# Negibus.net
KiCad netlist of a schematic drawn in EAGLE
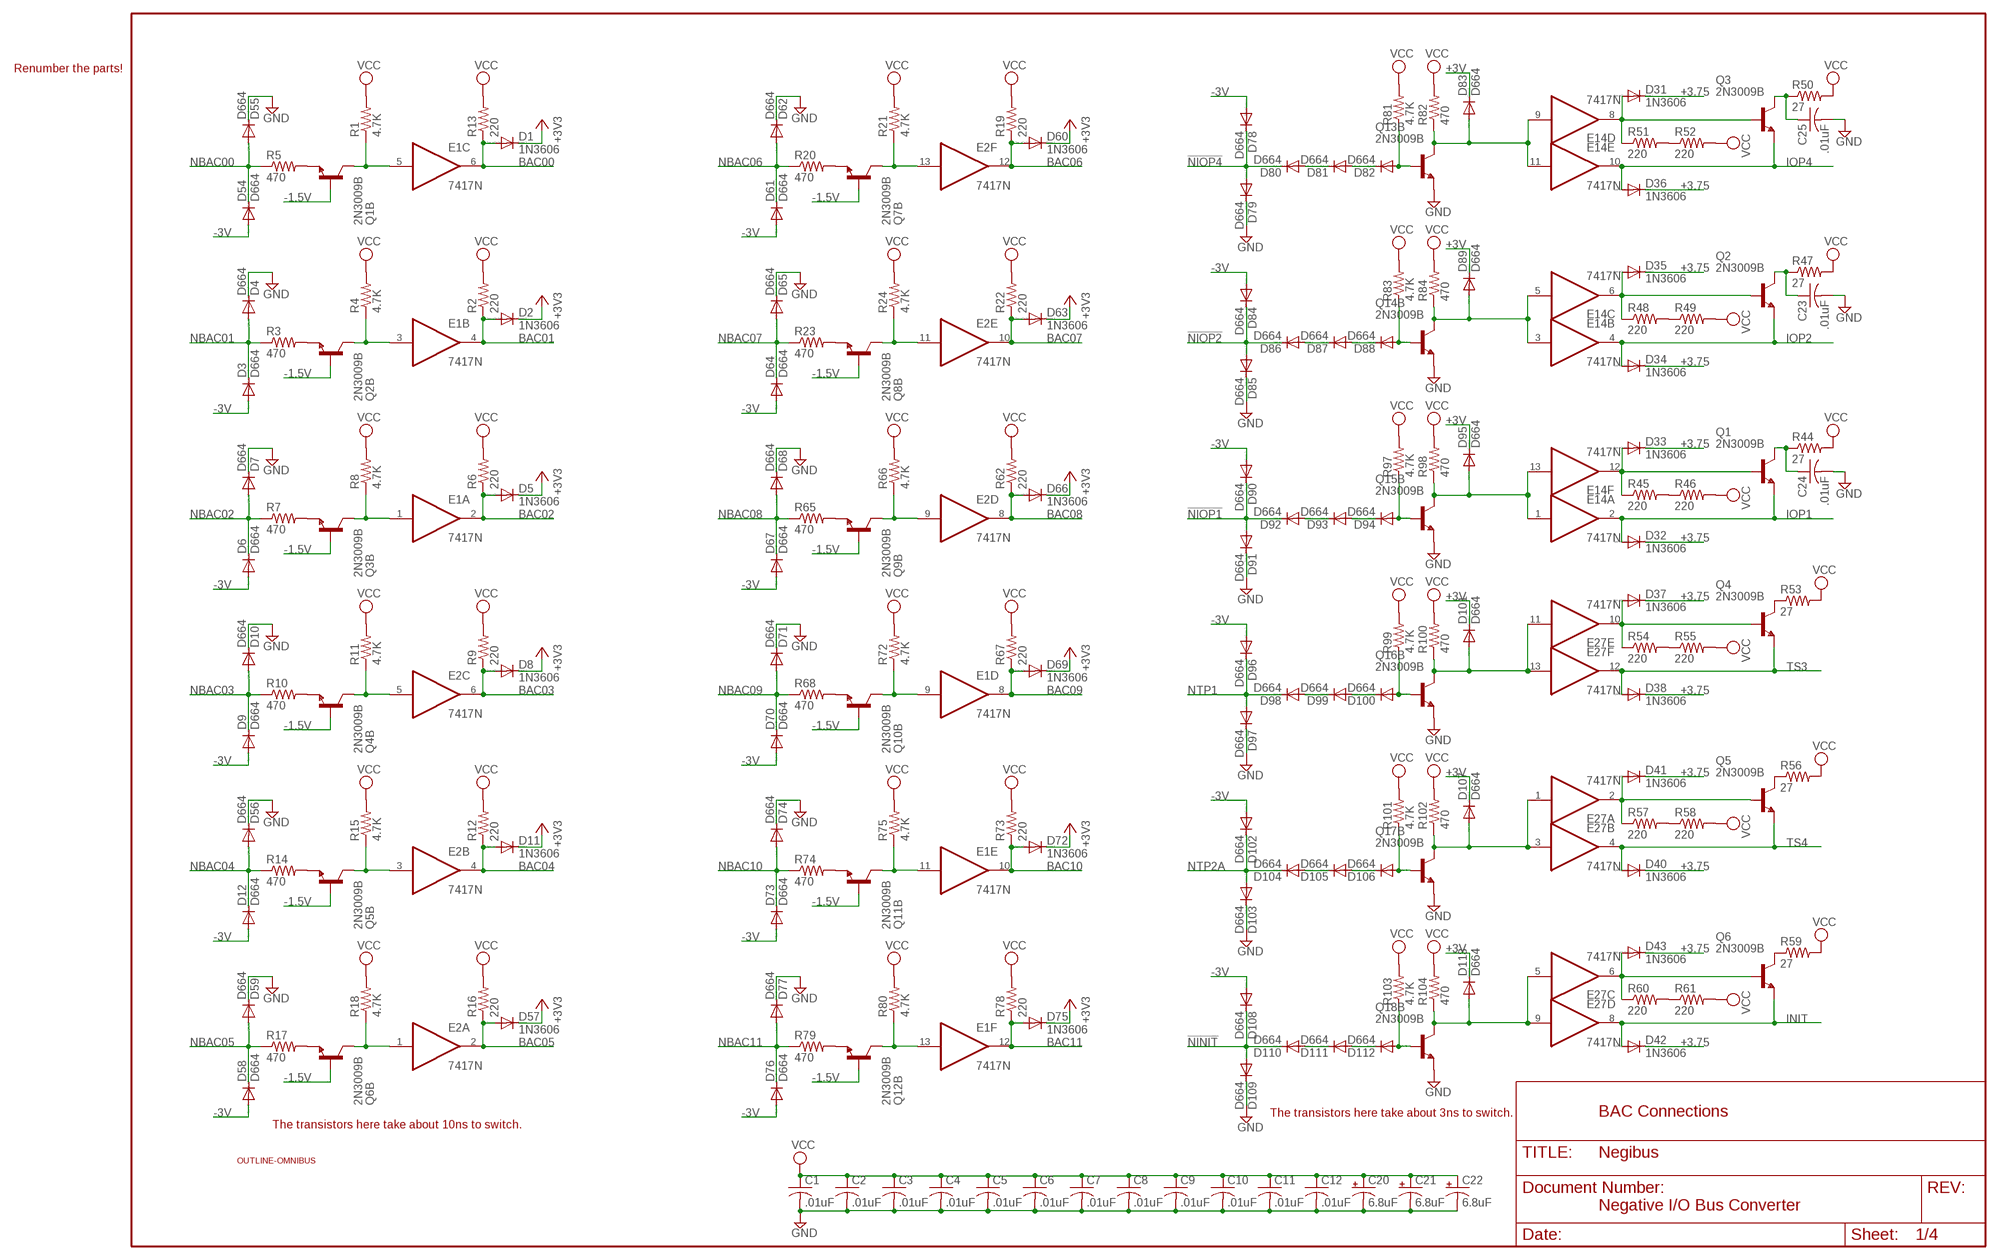
[diagram p0: schematic, sheet 1]
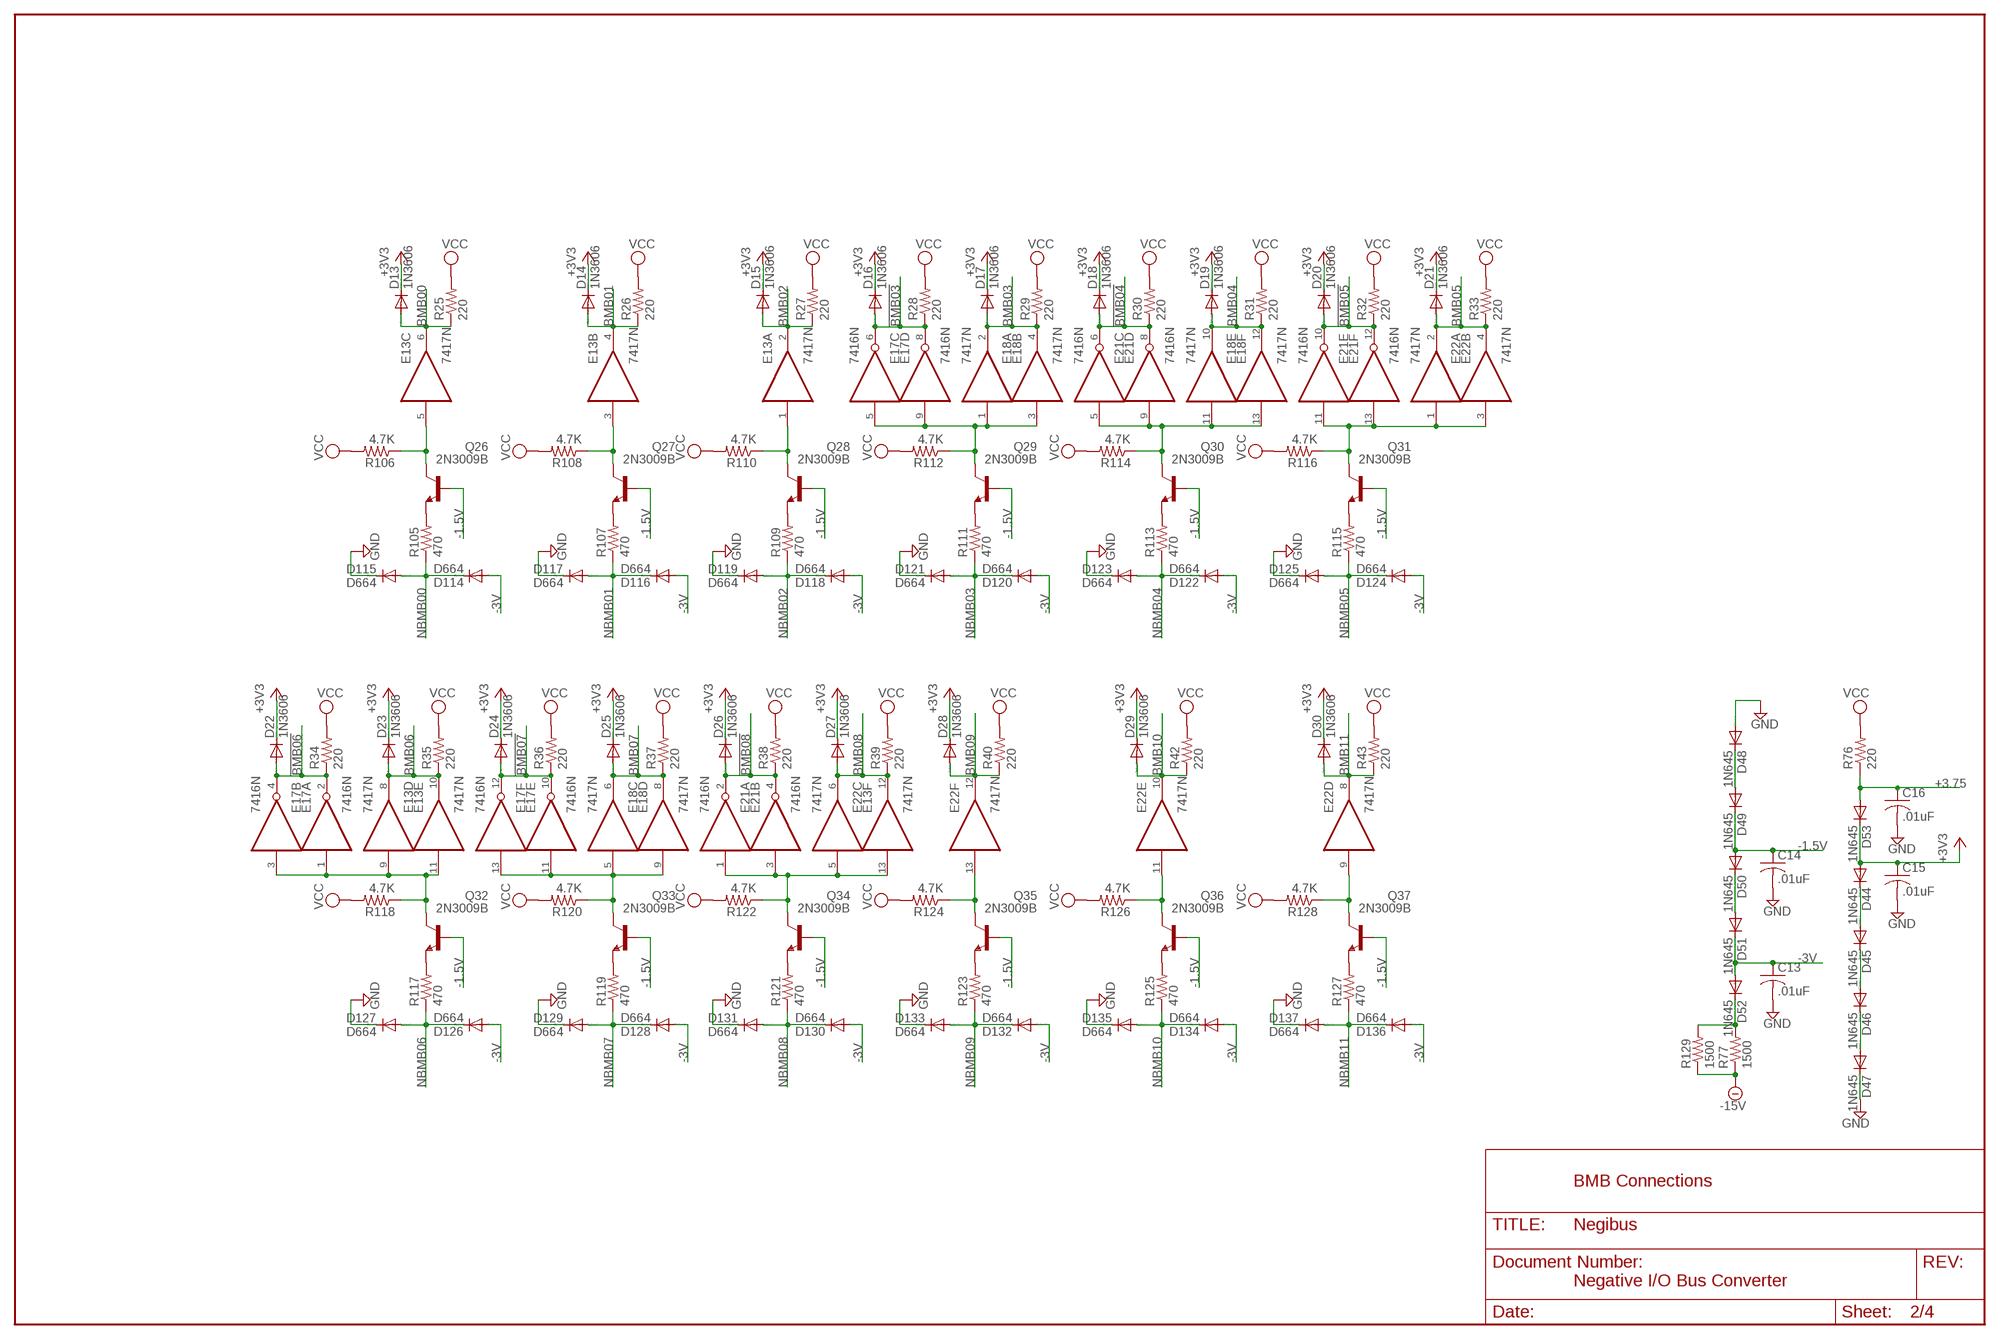
[diagram p1: schematic, sheet 2]
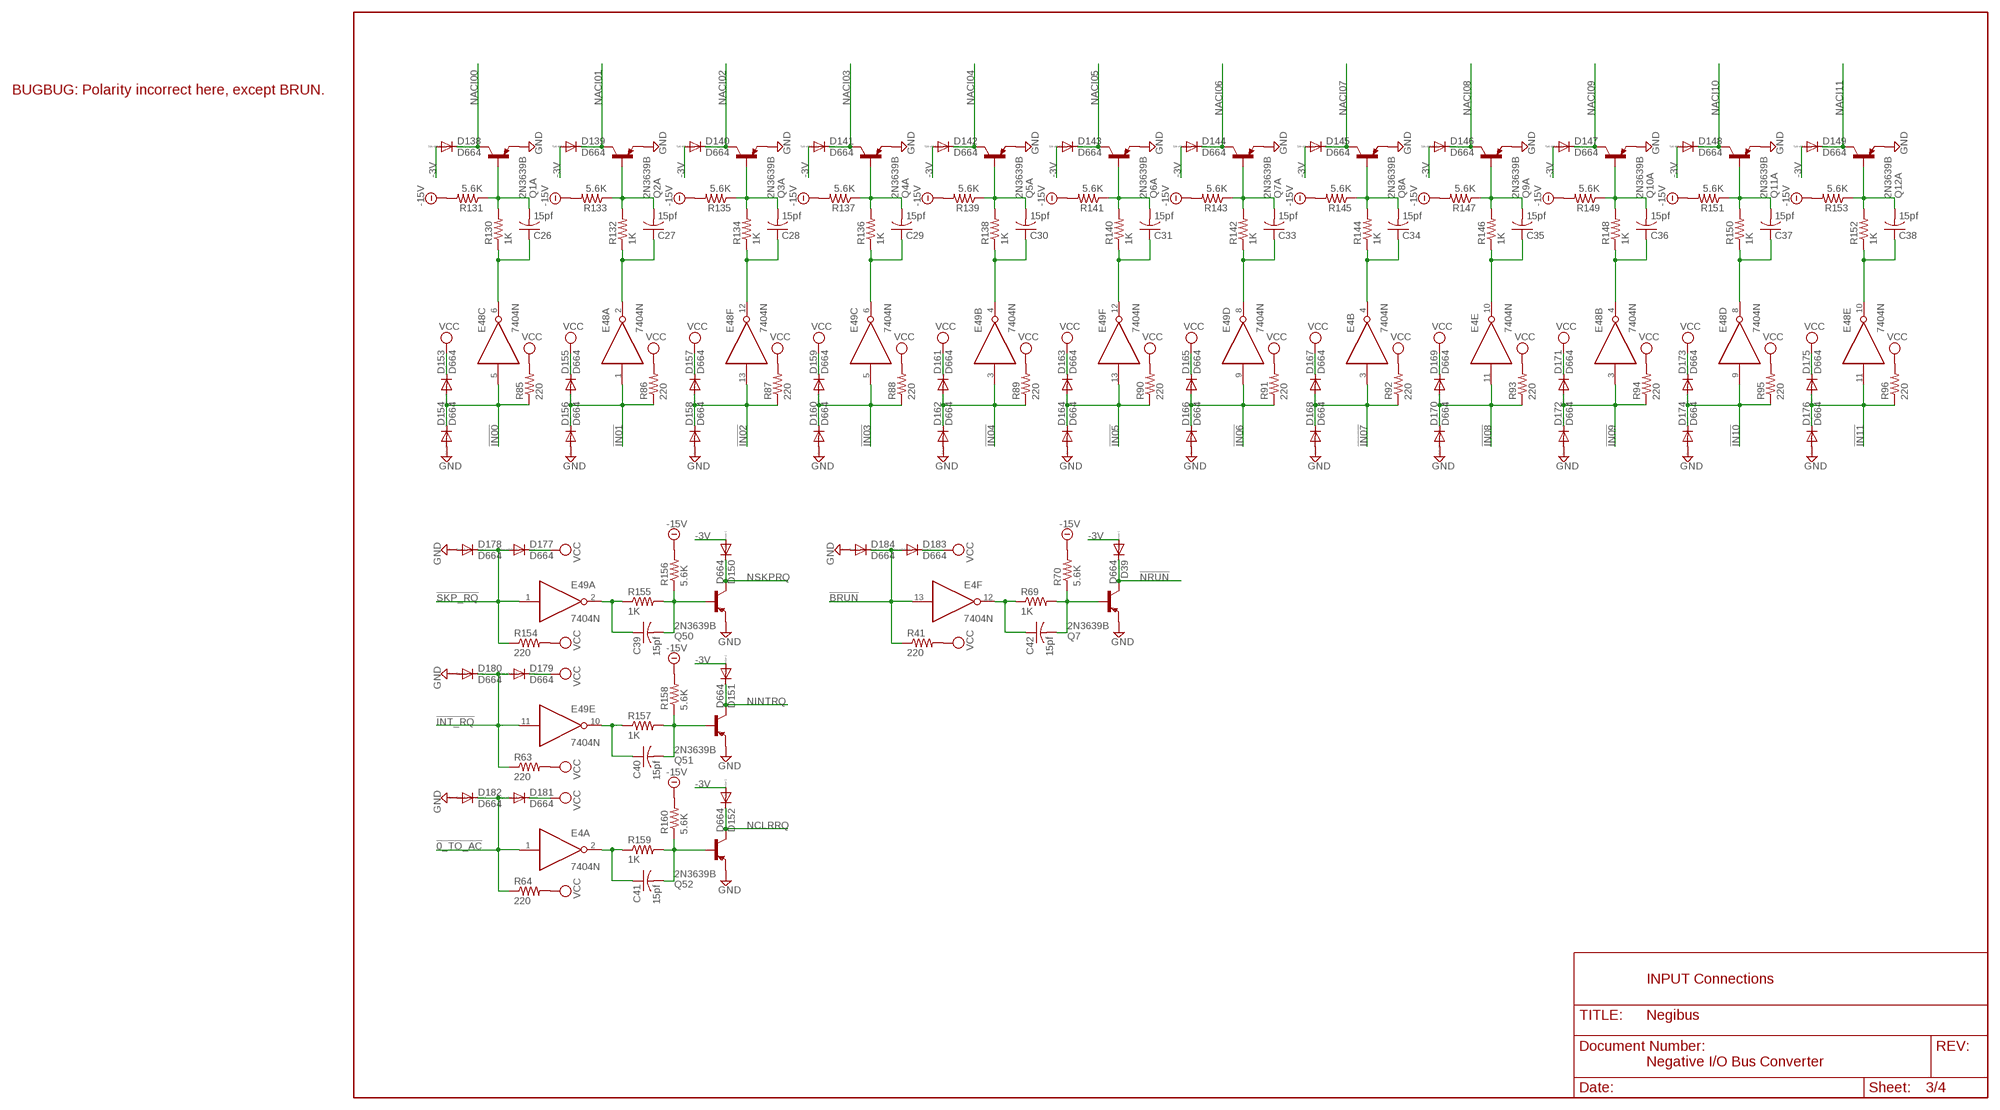
[diagram p2: schematic, sheet 3]
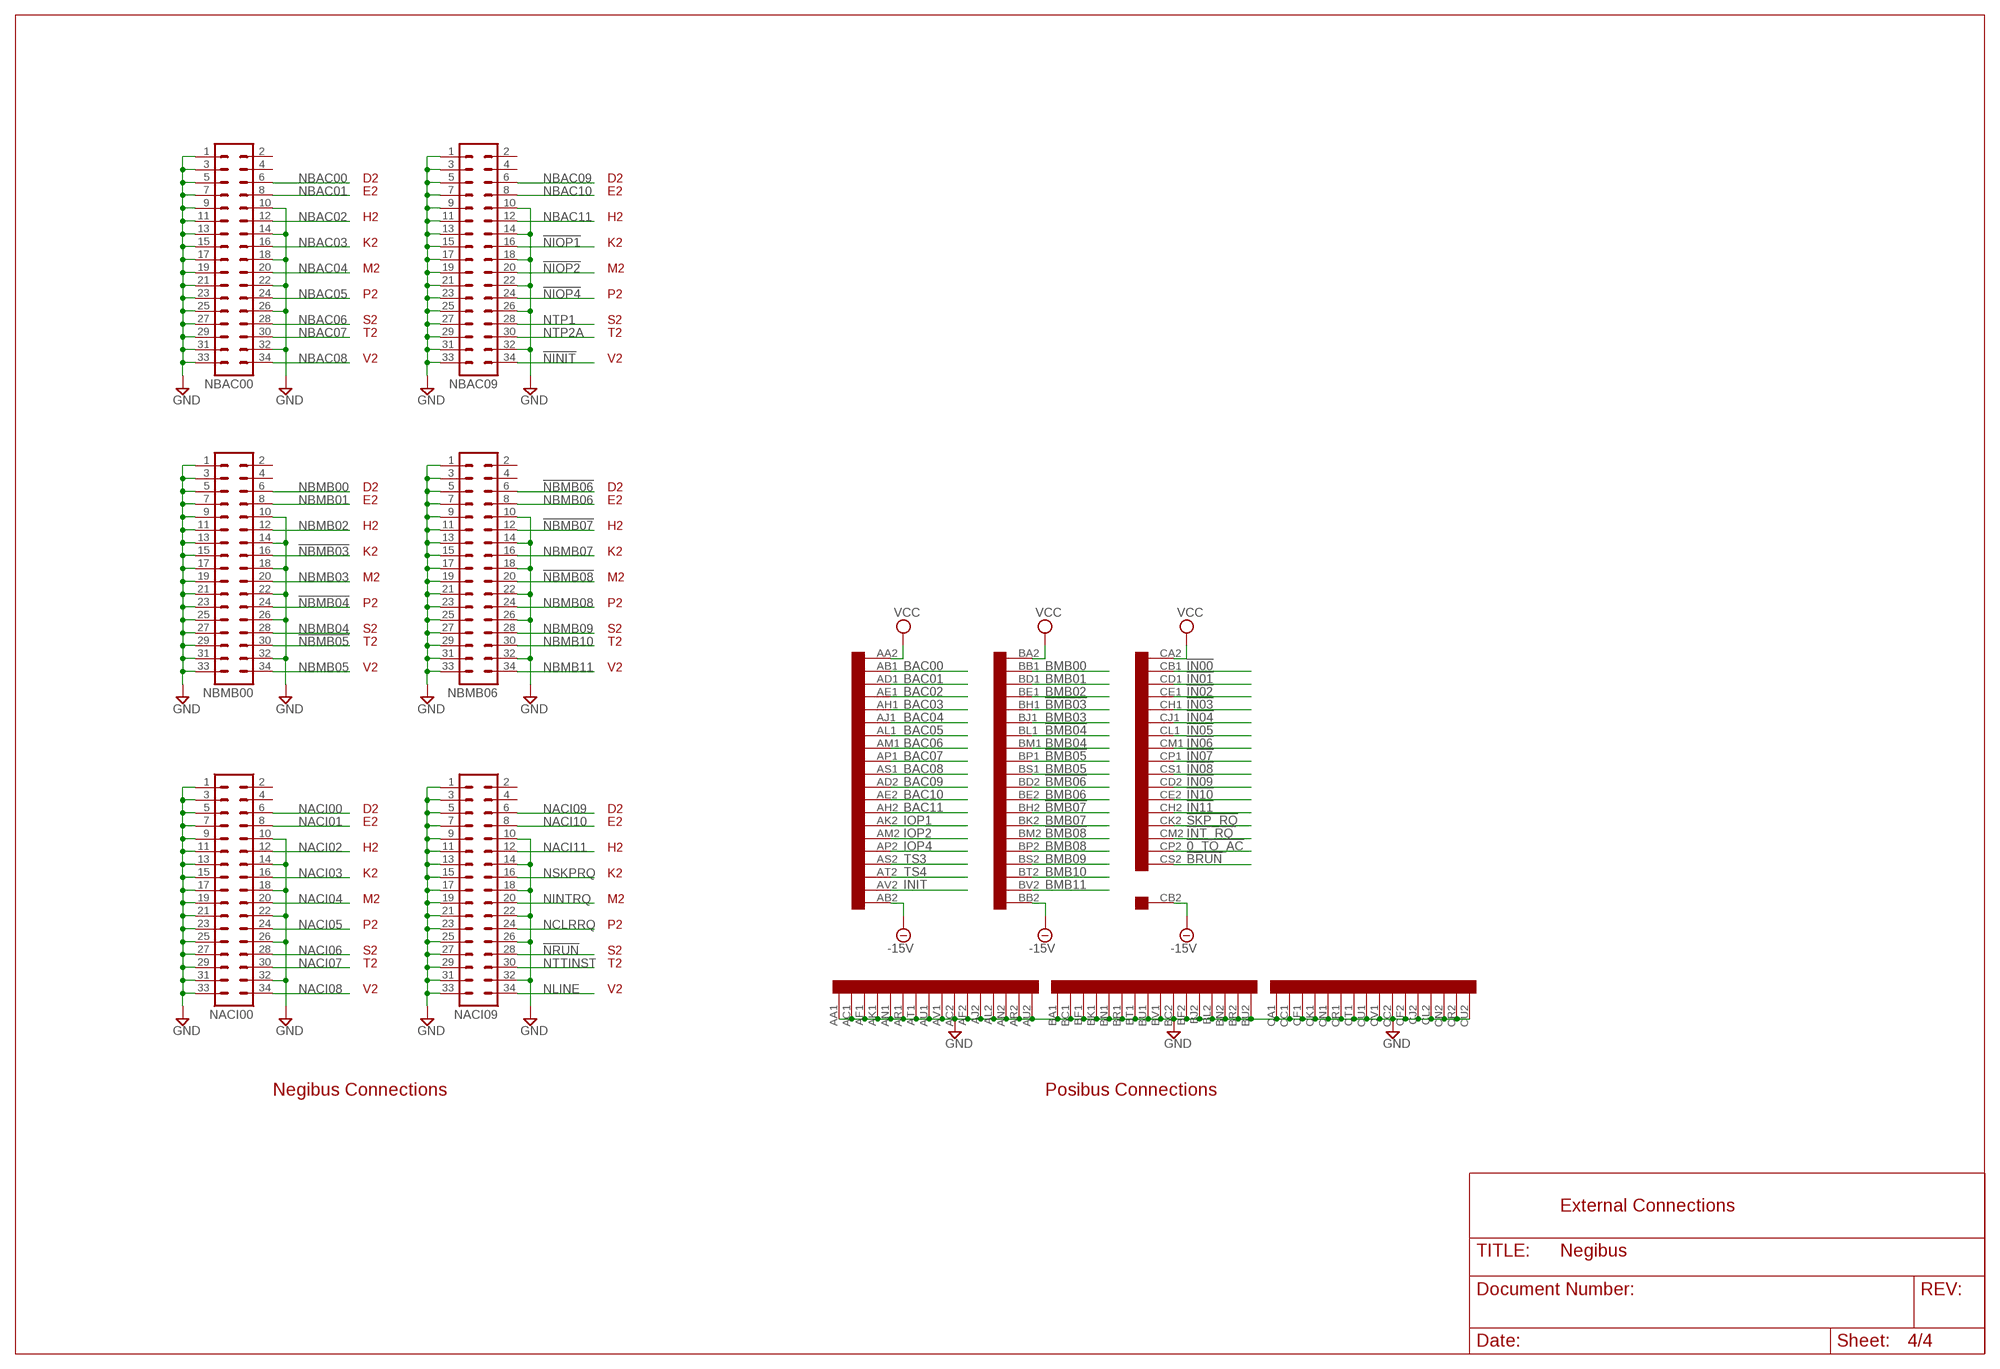
[diagram p3: schematic, sheet 4]

(export (version "E")
  (design (tool "Eeschema 10.0.6"))
  (components
    (comp (ref "C1")
      (value ".01uF")
      (footprint "eagle-import:C050-025X075")
      (libsource (lib "eagle-import") (part "C-US050-025X075"))
    )
    (comp (ref "C2")
      (value ".01uF")
      (footprint "eagle-import:C050-025X075")
      (libsource (lib "eagle-import") (part "C-US050-025X075"))
    )
    (comp (ref "C3")
      (value ".01uF")
      (footprint "eagle-import:C050-025X075")
      (libsource (lib "eagle-import") (part "C-US050-025X075"))
    )
    (comp (ref "C4")
      (value ".01uF")
      (footprint "eagle-import:C050-025X075")
      (libsource (lib "eagle-import") (part "C-US050-025X075"))
    )
    (comp (ref "C5")
      (value ".01uF")
      (footprint "eagle-import:C050-025X075")
      (libsource (lib "eagle-import") (part "C-US050-025X075"))
    )
    (comp (ref "C6")
      (value ".01uF")
      (footprint "eagle-import:C050-025X075")
      (libsource (lib "eagle-import") (part "C-US050-025X075"))
    )
    (comp (ref "C7")
      (value ".01uF")
      (footprint "eagle-import:C050-025X075")
      (libsource (lib "eagle-import") (part "C-US050-025X075"))
    )
    (comp (ref "C8")
      (value ".01uF")
      (footprint "eagle-import:C050-025X075")
      (libsource (lib "eagle-import") (part "C-US050-025X075"))
    )
    (comp (ref "C9")
      (value ".01uF")
      (footprint "eagle-import:C050-025X075")
      (libsource (lib "eagle-import") (part "C-US050-025X075"))
    )
    (comp (ref "C10")
      (value ".01uF")
      (footprint "eagle-import:C050-025X075")
      (libsource (lib "eagle-import") (part "C-US050-025X075"))
    )
    (comp (ref "C11")
      (value ".01uF")
      (footprint "eagle-import:C050-025X075")
      (libsource (lib "eagle-import") (part "C-US050-025X075"))
    )
    (comp (ref "C12")
      (value ".01uF")
      (footprint "eagle-import:C050-025X075")
      (libsource (lib "eagle-import") (part "C-US050-025X075"))
    )
    (comp (ref "C20")
      (value "6.8uF")
      (footprint "eagle-import:E12-8")
      (libsource (lib "eagle-import") (part "CPOL-USE20-8AXIAL"))
    )
    (comp (ref "C21")
      (value "6.8uF")
      (footprint "eagle-import:E12-8")
      (libsource (lib "eagle-import") (part "CPOL-USE20-8AXIAL"))
    )
    (comp (ref "C22")
      (value "6.8uF")
      (footprint "eagle-import:E12-8")
      (libsource (lib "eagle-import") (part "CPOL-USE20-8AXIAL"))
    )
    (comp (ref "C23")
      (value ".01uF")
      (footprint "eagle-import:C050-025X075")
      (libsource (lib "eagle-import") (part "C-US050-025X075"))
    )
    (comp (ref "C24")
      (value ".01uF")
      (footprint "eagle-import:C050-025X075")
      (libsource (lib "eagle-import") (part "C-US050-025X075"))
    )
    (comp (ref "C25")
      (value ".01uF")
      (footprint "eagle-import:C050-025X075")
      (libsource (lib "eagle-import") (part "C-US050-025X075"))
    )
    (comp (ref "D1")
      (value "1N3606")
      (footprint "eagle-import:DO35-10")
      (libsource (lib "eagle-import") (part "DIODE-DO35-10"))
    )
    (comp (ref "D2")
      (value "1N3606")
      (footprint "eagle-import:DO35-10")
      (libsource (lib "eagle-import") (part "DIODE-DO35-10"))
    )
    (comp (ref "D3")
      (value "D664")
      (footprint "eagle-import:DO35-10")
      (libsource (lib "eagle-import") (part "1N4148DO35-10"))
    )
    (comp (ref "D4")
      (value "D664")
      (footprint "eagle-import:DO35-10")
      (libsource (lib "eagle-import") (part "1N4148DO35-10"))
    )
    (comp (ref "D5")
      (value "1N3606")
      (footprint "eagle-import:DO35-10")
      (libsource (lib "eagle-import") (part "DIODE-DO35-10"))
    )
    (comp (ref "D6")
      (value "D664")
      (footprint "eagle-import:DO35-10")
      (libsource (lib "eagle-import") (part "1N4148DO35-10"))
    )
    (comp (ref "D7")
      (value "D664")
      (footprint "eagle-import:DO35-10")
      (libsource (lib "eagle-import") (part "1N4148DO35-10"))
    )
    (comp (ref "D8")
      (value "1N3606")
      (footprint "eagle-import:DO35-10")
      (libsource (lib "eagle-import") (part "DIODE-DO35-10"))
    )
    (comp (ref "D9")
      (value "D664")
      (footprint "eagle-import:DO35-10")
      (libsource (lib "eagle-import") (part "1N4148DO35-10"))
    )
    (comp (ref "D10")
      (value "D664")
      (footprint "eagle-import:DO35-10")
      (libsource (lib "eagle-import") (part "1N4148DO35-10"))
    )
    (comp (ref "D11")
      (value "1N3606")
      (footprint "eagle-import:DO35-10")
      (libsource (lib "eagle-import") (part "DIODE-DO35-10"))
    )
    (comp (ref "D12")
      (value "D664")
      (footprint "eagle-import:DO35-10")
      (libsource (lib "eagle-import") (part "1N4148DO35-10"))
    )
    (comp (ref "D31")
      (value "1N3606")
      (footprint "eagle-import:DO35-10")
      (libsource (lib "eagle-import") (part "DIODE-DO35-10"))
    )
    (comp (ref "D32")
      (value "1N3606")
      (footprint "eagle-import:DO35-10")
      (libsource (lib "eagle-import") (part "DIODE-DO35-10"))
    )
    (comp (ref "D33")
      (value "1N3606")
      (footprint "eagle-import:DO35-10")
      (libsource (lib "eagle-import") (part "DIODE-DO35-10"))
    )
    (comp (ref "D34")
      (value "1N3606")
      (footprint "eagle-import:DO35-10")
      (libsource (lib "eagle-import") (part "DIODE-DO35-10"))
    )
    (comp (ref "D35")
      (value "1N3606")
      (footprint "eagle-import:DO35-10")
      (libsource (lib "eagle-import") (part "DIODE-DO35-10"))
    )
    (comp (ref "D36")
      (value "1N3606")
      (footprint "eagle-import:DO35-10")
      (libsource (lib "eagle-import") (part "DIODE-DO35-10"))
    )
    (comp (ref "D37")
      (value "1N3606")
      (footprint "eagle-import:DO35-10")
      (libsource (lib "eagle-import") (part "DIODE-DO35-10"))
    )
    (comp (ref "D38")
      (value "1N3606")
      (footprint "eagle-import:DO35-10")
      (libsource (lib "eagle-import") (part "DIODE-DO35-10"))
    )
    (comp (ref "D40")
      (value "1N3606")
      (footprint "eagle-import:DO35-10")
      (libsource (lib "eagle-import") (part "DIODE-DO35-10"))
    )
    (comp (ref "D41")
      (value "1N3606")
      (footprint "eagle-import:DO35-10")
      (libsource (lib "eagle-import") (part "DIODE-DO35-10"))
    )
    (comp (ref "D42")
      (value "1N3606")
      (footprint "eagle-import:DO35-10")
      (libsource (lib "eagle-import") (part "DIODE-DO35-10"))
    )
    (comp (ref "D43")
      (value "1N3606")
      (footprint "eagle-import:DO35-10")
      (libsource (lib "eagle-import") (part "DIODE-DO35-10"))
    )
    (comp (ref "D54")
      (value "D664")
      (footprint "eagle-import:DO35-10")
      (libsource (lib "eagle-import") (part "1N4148DO35-10"))
    )
    (comp (ref "D55")
      (value "D664")
      (footprint "eagle-import:DO35-10")
      (libsource (lib "eagle-import") (part "1N4148DO35-10"))
    )
    (comp (ref "D56")
      (value "D664")
      (footprint "eagle-import:DO35-10")
      (libsource (lib "eagle-import") (part "1N4148DO35-10"))
    )
    (comp (ref "D57")
      (value "1N3606")
      (footprint "eagle-import:DO35-10")
      (libsource (lib "eagle-import") (part "DIODE-DO35-10"))
    )
    (comp (ref "D58")
      (value "D664")
      (footprint "eagle-import:DO35-10")
      (libsource (lib "eagle-import") (part "1N4148DO35-10"))
    )
    (comp (ref "D59")
      (value "D664")
      (footprint "eagle-import:DO35-10")
      (libsource (lib "eagle-import") (part "1N4148DO35-10"))
    )
    (comp (ref "D60")
      (value "1N3606")
      (footprint "eagle-import:DO35-10")
      (libsource (lib "eagle-import") (part "DIODE-DO35-10"))
    )
    (comp (ref "D61")
      (value "D664")
      (footprint "eagle-import:DO35-10")
      (libsource (lib "eagle-import") (part "1N4148DO35-10"))
    )
    (comp (ref "D62")
      (value "D664")
      (footprint "eagle-import:DO35-10")
      (libsource (lib "eagle-import") (part "1N4148DO35-10"))
    )
    (comp (ref "D63")
      (value "1N3606")
      (footprint "eagle-import:DO35-10")
      (libsource (lib "eagle-import") (part "DIODE-DO35-10"))
    )
    (comp (ref "D64")
      (value "D664")
      (footprint "eagle-import:DO35-10")
      (libsource (lib "eagle-import") (part "1N4148DO35-10"))
    )
    (comp (ref "D65")
      (value "D664")
      (footprint "eagle-import:DO35-10")
      (libsource (lib "eagle-import") (part "1N4148DO35-10"))
    )
    (comp (ref "D66")
      (value "1N3606")
      (footprint "eagle-import:DO35-10")
      (libsource (lib "eagle-import") (part "DIODE-DO35-10"))
    )
    (comp (ref "D67")
      (value "D664")
      (footprint "eagle-import:DO35-10")
      (libsource (lib "eagle-import") (part "1N4148DO35-10"))
    )
    (comp (ref "D68")
      (value "D664")
      (footprint "eagle-import:DO35-10")
      (libsource (lib "eagle-import") (part "1N4148DO35-10"))
    )
    (comp (ref "D69")
      (value "1N3606")
      (footprint "eagle-import:DO35-10")
      (libsource (lib "eagle-import") (part "DIODE-DO35-10"))
    )
    (comp (ref "D70")
      (value "D664")
      (footprint "eagle-import:DO35-10")
      (libsource (lib "eagle-import") (part "1N4148DO35-10"))
    )
    (comp (ref "D71")
      (value "D664")
      (footprint "eagle-import:DO35-10")
      (libsource (lib "eagle-import") (part "1N4148DO35-10"))
    )
    (comp (ref "D72")
      (value "1N3606")
      (footprint "eagle-import:DO35-10")
      (libsource (lib "eagle-import") (part "DIODE-DO35-10"))
    )
    (comp (ref "D73")
      (value "D664")
      (footprint "eagle-import:DO35-10")
      (libsource (lib "eagle-import") (part "1N4148DO35-10"))
    )
    (comp (ref "D74")
      (value "D664")
      (footprint "eagle-import:DO35-10")
      (libsource (lib "eagle-import") (part "1N4148DO35-10"))
    )
    (comp (ref "D75")
      (value "1N3606")
      (footprint "eagle-import:DO35-10")
      (libsource (lib "eagle-import") (part "DIODE-DO35-10"))
    )
    (comp (ref "D76")
      (value "D664")
      (footprint "eagle-import:DO35-10")
      (libsource (lib "eagle-import") (part "1N4148DO35-10"))
    )
    (comp (ref "D77")
      (value "D664")
      (footprint "eagle-import:DO35-10")
      (libsource (lib "eagle-import") (part "1N4148DO35-10"))
    )
    (comp (ref "D78")
      (value "D664")
      (footprint "eagle-import:DO35-10")
      (libsource (lib "eagle-import") (part "1N4148DO35-10"))
    )
    (comp (ref "D79")
      (value "D664")
      (footprint "eagle-import:DO35-10")
      (libsource (lib "eagle-import") (part "1N4148DO35-10"))
    )
    (comp (ref "D80")
      (value "D664")
      (footprint "eagle-import:DO35-10")
      (libsource (lib "eagle-import") (part "1N4148DO35-10"))
    )
    (comp (ref "D81")
      (value "D664")
      (footprint "eagle-import:DO35-10")
      (libsource (lib "eagle-import") (part "1N4148DO35-10"))
    )
    (comp (ref "D82")
      (value "D664")
      (footprint "eagle-import:DO35-10")
      (libsource (lib "eagle-import") (part "1N4148DO35-10"))
    )
    (comp (ref "D83")
      (value "D664")
      (footprint "eagle-import:DO35-10")
      (libsource (lib "eagle-import") (part "1N4148DO35-10"))
    )
    (comp (ref "D84")
      (value "D664")
      (footprint "eagle-import:DO35-10")
      (libsource (lib "eagle-import") (part "1N4148DO35-10"))
    )
    (comp (ref "D85")
      (value "D664")
      (footprint "eagle-import:DO35-10")
      (libsource (lib "eagle-import") (part "1N4148DO35-10"))
    )
    (comp (ref "D86")
      (value "D664")
      (footprint "eagle-import:DO35-10")
      (libsource (lib "eagle-import") (part "1N4148DO35-10"))
    )
    (comp (ref "D87")
      (value "D664")
      (footprint "eagle-import:DO35-10")
      (libsource (lib "eagle-import") (part "1N4148DO35-10"))
    )
    (comp (ref "D88")
      (value "D664")
      (footprint "eagle-import:DO35-10")
      (libsource (lib "eagle-import") (part "1N4148DO35-10"))
    )
    (comp (ref "D89")
      (value "D664")
      (footprint "eagle-import:DO35-10")
      (libsource (lib "eagle-import") (part "1N4148DO35-10"))
    )
    (comp (ref "D90")
      (value "D664")
      (footprint "eagle-import:DO35-10")
      (libsource (lib "eagle-import") (part "1N4148DO35-10"))
    )
    (comp (ref "D91")
      (value "D664")
      (footprint "eagle-import:DO35-10")
      (libsource (lib "eagle-import") (part "1N4148DO35-10"))
    )
    (comp (ref "D92")
      (value "D664")
      (footprint "eagle-import:DO35-10")
      (libsource (lib "eagle-import") (part "1N4148DO35-10"))
    )
    (comp (ref "D93")
      (value "D664")
      (footprint "eagle-import:DO35-10")
      (libsource (lib "eagle-import") (part "1N4148DO35-10"))
    )
    (comp (ref "D94")
      (value "D664")
      (footprint "eagle-import:DO35-10")
      (libsource (lib "eagle-import") (part "1N4148DO35-10"))
    )
    (comp (ref "D95")
      (value "D664")
      (footprint "eagle-import:DO35-10")
      (libsource (lib "eagle-import") (part "1N4148DO35-10"))
    )
    (comp (ref "D96")
      (value "D664")
      (footprint "eagle-import:DO35-10")
      (libsource (lib "eagle-import") (part "1N4148DO35-10"))
    )
    (comp (ref "D97")
      (value "D664")
      (footprint "eagle-import:DO35-10")
      (libsource (lib "eagle-import") (part "1N4148DO35-10"))
    )
    (comp (ref "D98")
      (value "D664")
      (footprint "eagle-import:DO35-10")
      (libsource (lib "eagle-import") (part "1N4148DO35-10"))
    )
    (comp (ref "D99")
      (value "D664")
      (footprint "eagle-import:DO35-10")
      (libsource (lib "eagle-import") (part "1N4148DO35-10"))
    )
    (comp (ref "D100")
      (value "D664")
      (footprint "eagle-import:DO35-10")
      (libsource (lib "eagle-import") (part "1N4148DO35-10"))
    )
    (comp (ref "D101")
      (value "D664")
      (footprint "eagle-import:DO35-10")
      (libsource (lib "eagle-import") (part "1N4148DO35-10"))
    )
    (comp (ref "D102")
      (value "D664")
      (footprint "eagle-import:DO35-10")
      (libsource (lib "eagle-import") (part "1N4148DO35-10"))
    )
    (comp (ref "D103")
      (value "D664")
      (footprint "eagle-import:DO35-10")
      (libsource (lib "eagle-import") (part "1N4148DO35-10"))
    )
    (comp (ref "D104")
      (value "D664")
      (footprint "eagle-import:DO35-10")
      (libsource (lib "eagle-import") (part "1N4148DO35-10"))
    )
    (comp (ref "D105")
      (value "D664")
      (footprint "eagle-import:DO35-10")
      (libsource (lib "eagle-import") (part "1N4148DO35-10"))
    )
    (comp (ref "D106")
      (value "D664")
      (footprint "eagle-import:DO35-10")
      (libsource (lib "eagle-import") (part "1N4148DO35-10"))
    )
    (comp (ref "D107")
      (value "D664")
      (footprint "eagle-import:DO35-10")
      (libsource (lib "eagle-import") (part "1N4148DO35-10"))
    )
    (comp (ref "D108")
      (value "D664")
      (footprint "eagle-import:DO35-10")
      (libsource (lib "eagle-import") (part "1N4148DO35-10"))
    )
    (comp (ref "D109")
      (value "D664")
      (footprint "eagle-import:DO35-10")
      (libsource (lib "eagle-import") (part "1N4148DO35-10"))
    )
    (comp (ref "D110")
      (value "D664")
      (footprint "eagle-import:DO35-10")
      (libsource (lib "eagle-import") (part "1N4148DO35-10"))
    )
    (comp (ref "D111")
      (value "D664")
      (footprint "eagle-import:DO35-10")
      (libsource (lib "eagle-import") (part "1N4148DO35-10"))
    )
    (comp (ref "D112")
      (value "D664")
      (footprint "eagle-import:DO35-10")
      (libsource (lib "eagle-import") (part "1N4148DO35-10"))
    )
    (comp (ref "D113")
      (value "D664")
      (footprint "eagle-import:DO35-10")
      (libsource (lib "eagle-import") (part "1N4148DO35-10"))
    )
    (comp (ref "E1")
      (value "7417N")
      (footprint "eagle-import:DIL14")
      (libsource (lib "eagle-import") (part "7407N"))
    )
    (comp (ref "E2")
      (value "7417N")
      (footprint "eagle-import:DIL14")
      (libsource (lib "eagle-import") (part "7407N"))
    )
    (comp (ref "E14")
      (value "7417N")
      (footprint "eagle-import:DIL14")
      (libsource (lib "eagle-import") (part "74xx-us_7407N"))
    )
    (comp (ref "E27")
      (value "7417N")
      (footprint "eagle-import:DIL14")
      (libsource (lib "eagle-import") (part "74xx-us_7407N"))
    )
    (comp (ref "Q1")
      (value "2N3009B")
      (footprint "eagle-import:TO5")
      (libsource (lib "eagle-import") (part "-NPN-TO5"))
    )
    (comp (ref "Q1B")
      (value "2N3009B")
      (footprint "eagle-import:TO39")
      (libsource (lib "eagle-import") (part "2N3019"))
    )
    (comp (ref "Q2")
      (value "2N3009B")
      (footprint "eagle-import:TO5")
      (libsource (lib "eagle-import") (part "-NPN-TO5"))
    )
    (comp (ref "Q2B")
      (value "2N3009B")
      (footprint "eagle-import:TO39")
      (libsource (lib "eagle-import") (part "2N3019"))
    )
    (comp (ref "Q3")
      (value "2N3009B")
      (footprint "eagle-import:TO5")
      (libsource (lib "eagle-import") (part "-NPN-TO5"))
    )
    (comp (ref "Q3B")
      (value "2N3009B")
      (footprint "eagle-import:TO39")
      (libsource (lib "eagle-import") (part "2N3019"))
    )
    (comp (ref "Q4")
      (value "2N3009B")
      (footprint "eagle-import:TO5")
      (libsource (lib "eagle-import") (part "-NPN-TO5"))
    )
    (comp (ref "Q4B")
      (value "2N3009B")
      (footprint "eagle-import:TO39")
      (libsource (lib "eagle-import") (part "2N3019"))
    )
    (comp (ref "Q5")
      (value "2N3009B")
      (footprint "eagle-import:TO5")
      (libsource (lib "eagle-import") (part "-NPN-TO5"))
    )
    (comp (ref "Q5B")
      (value "2N3009B")
      (footprint "eagle-import:TO39")
      (libsource (lib "eagle-import") (part "2N3019"))
    )
    (comp (ref "Q6")
      (value "2N3009B")
      (footprint "eagle-import:TO5")
      (libsource (lib "eagle-import") (part "-NPN-TO5"))
    )
    (comp (ref "Q6B")
      (value "2N3009B")
      (footprint "eagle-import:TO39")
      (libsource (lib "eagle-import") (part "2N3019"))
    )
    (comp (ref "Q7B")
      (value "2N3009B")
      (footprint "eagle-import:TO39")
      (libsource (lib "eagle-import") (part "2N3019"))
    )
    (comp (ref "Q8B")
      (value "2N3009B")
      (footprint "eagle-import:TO39")
      (libsource (lib "eagle-import") (part "2N3019"))
    )
    (comp (ref "Q9B")
      (value "2N3009B")
      (footprint "eagle-import:TO39")
      (libsource (lib "eagle-import") (part "2N3019"))
    )
    (comp (ref "Q10B")
      (value "2N3009B")
      (footprint "eagle-import:TO39")
      (libsource (lib "eagle-import") (part "2N3019"))
    )
    (comp (ref "Q11B")
      (value "2N3009B")
      (footprint "eagle-import:TO39")
      (libsource (lib "eagle-import") (part "2N3019"))
    )
    (comp (ref "Q12B")
      (value "2N3009B")
      (footprint "eagle-import:TO39")
      (libsource (lib "eagle-import") (part "2N3019"))
    )
    (comp (ref "Q13B")
      (value "2N3009B")
      (footprint "eagle-import:TO39")
      (libsource (lib "eagle-import") (part "2N3019"))
    )
    (comp (ref "Q14B")
      (value "2N3009B")
      (footprint "eagle-import:TO39")
      (libsource (lib "eagle-import") (part "2N3019"))
    )
    (comp (ref "Q15B")
      (value "2N3009B")
      (footprint "eagle-import:TO39")
      (libsource (lib "eagle-import") (part "2N3019"))
    )
    (comp (ref "Q16B")
      (value "2N3009B")
      (footprint "eagle-import:TO39")
      (libsource (lib "eagle-import") (part "2N3019"))
    )
    (comp (ref "Q17B")
      (value "2N3009B")
      (footprint "eagle-import:TO39")
      (libsource (lib "eagle-import") (part "2N3019"))
    )
    (comp (ref "Q18B")
      (value "2N3009B")
      (footprint "eagle-import:TO39")
      (libsource (lib "eagle-import") (part "2N3019"))
    )
    (comp (ref "R1")
      (value "4.7K")
      (footprint "eagle-import:0207_10")
      (libsource (lib "eagle-import") (part "R-US_0207/10"))
    )
    (comp (ref "R2")
      (value "220")
      (footprint "eagle-import:0207_10")
      (libsource (lib "eagle-import") (part "R-US_0207/10"))
    )
    (comp (ref "R3")
      (value "470")
      (footprint "eagle-import:0207_10")
      (libsource (lib "eagle-import") (part "R-US_0207/10"))
    )
    (comp (ref "R4")
      (value "4.7K")
      (footprint "eagle-import:0207_10")
      (libsource (lib "eagle-import") (part "R-US_0207/10"))
    )
    (comp (ref "R5")
      (value "470")
      (footprint "eagle-import:0207_10")
      (libsource (lib "eagle-import") (part "R-US_0207/10"))
    )
    (comp (ref "R6")
      (value "220")
      (footprint "eagle-import:0207_10")
      (libsource (lib "eagle-import") (part "R-US_0207/10"))
    )
    (comp (ref "R7")
      (value "470")
      (footprint "eagle-import:0207_10")
      (libsource (lib "eagle-import") (part "R-US_0207/10"))
    )
    (comp (ref "R8")
      (value "4.7K")
      (footprint "eagle-import:0207_10")
      (libsource (lib "eagle-import") (part "R-US_0207/10"))
    )
    (comp (ref "R9")
      (value "220")
      (footprint "eagle-import:0207_10")
      (libsource (lib "eagle-import") (part "R-US_0207/10"))
    )
    (comp (ref "R10")
      (value "470")
      (footprint "eagle-import:0207_10")
      (libsource (lib "eagle-import") (part "R-US_0207/10"))
    )
    (comp (ref "R11")
      (value "4.7K")
      (footprint "eagle-import:0207_10")
      (libsource (lib "eagle-import") (part "R-US_0207/10"))
    )
    (comp (ref "R12")
      (value "220")
      (footprint "eagle-import:0207_10")
      (libsource (lib "eagle-import") (part "R-US_0207/10"))
    )
    (comp (ref "R13")
      (value "220")
      (footprint "eagle-import:0207_10")
      (libsource (lib "eagle-import") (part "R-US_0207/10"))
    )
    (comp (ref "R14")
      (value "470")
      (footprint "eagle-import:0207_10")
      (libsource (lib "eagle-import") (part "R-US_0207/10"))
    )
    (comp (ref "R15")
      (value "4.7K")
      (footprint "eagle-import:0207_10")
      (libsource (lib "eagle-import") (part "R-US_0207/10"))
    )
    (comp (ref "R16")
      (value "220")
      (footprint "eagle-import:0207_10")
      (libsource (lib "eagle-import") (part "R-US_0207/10"))
    )
    (comp (ref "R17")
      (value "470")
      (footprint "eagle-import:0207_10")
      (libsource (lib "eagle-import") (part "R-US_0207/10"))
    )
    (comp (ref "R18")
      (value "4.7K")
      (footprint "eagle-import:0207_10")
      (libsource (lib "eagle-import") (part "R-US_0207/10"))
    )
    (comp (ref "R19")
      (value "220")
      (footprint "eagle-import:0207_10")
      (libsource (lib "eagle-import") (part "R-US_0207/10"))
    )
    (comp (ref "R20")
      (value "470")
      (footprint "eagle-import:0207_10")
      (libsource (lib "eagle-import") (part "R-US_0207/10"))
    )
    (comp (ref "R21")
      (value "4.7K")
      (footprint "eagle-import:0207_10")
      (libsource (lib "eagle-import") (part "R-US_0207/10"))
    )
    (comp (ref "R22")
      (value "220")
      (footprint "eagle-import:0207_10")
      (libsource (lib "eagle-import") (part "R-US_0207/10"))
    )
    (comp (ref "R23")
      (value "470")
      (footprint "eagle-import:0207_10")
      (libsource (lib "eagle-import") (part "R-US_0207/10"))
    )
    (comp (ref "R24")
      (value "4.7K")
      (footprint "eagle-import:0207_10")
      (libsource (lib "eagle-import") (part "R-US_0207/10"))
    )
    (comp (ref "R44")
      (value "27")
      (footprint "eagle-import:0411_12")
      (libsource (lib "eagle-import") (part "R-US_0411/12"))
    )
    (comp (ref "R45")
      (value "220")
      (footprint "eagle-import:0207_10")
      (libsource (lib "eagle-import") (part "R-US_0207/10"))
    )
    (comp (ref "R46")
      (value "220")
      (footprint "eagle-import:0207_10")
      (libsource (lib "eagle-import") (part "R-US_0207/10"))
    )
    (comp (ref "R47")
      (value "27")
      (footprint "eagle-import:0411_12")
      (libsource (lib "eagle-import") (part "R-US_0411/12"))
    )
    (comp (ref "R48")
      (value "220")
      (footprint "eagle-import:0207_10")
      (libsource (lib "eagle-import") (part "R-US_0207/10"))
    )
    (comp (ref "R49")
      (value "220")
      (footprint "eagle-import:0207_10")
      (libsource (lib "eagle-import") (part "R-US_0207/10"))
    )
    (comp (ref "R50")
      (value "27")
      (footprint "eagle-import:0411_12")
      (libsource (lib "eagle-import") (part "R-US_0411/12"))
    )
    (comp (ref "R51")
      (value "220")
      (footprint "eagle-import:0207_10")
      (libsource (lib "eagle-import") (part "R-US_0207/10"))
    )
    (comp (ref "R52")
      (value "220")
      (footprint "eagle-import:0207_10")
      (libsource (lib "eagle-import") (part "R-US_0207/10"))
    )
    (comp (ref "R53")
      (value "27")
      (footprint "eagle-import:0411_12")
      (libsource (lib "eagle-import") (part "R-US_0411/12"))
    )
    (comp (ref "R54")
      (value "220")
      (footprint "eagle-import:0207_10")
      (libsource (lib "eagle-import") (part "R-US_0207/10"))
    )
    (comp (ref "R55")
      (value "220")
      (footprint "eagle-import:0207_10")
      (libsource (lib "eagle-import") (part "R-US_0207/10"))
    )
    (comp (ref "R56")
      (value "27")
      (footprint "eagle-import:0411_12")
      (libsource (lib "eagle-import") (part "R-US_0411/12"))
    )
    (comp (ref "R57")
      (value "220")
      (footprint "eagle-import:0207_10")
      (libsource (lib "eagle-import") (part "R-US_0207/10"))
    )
    (comp (ref "R58")
      (value "220")
      (footprint "eagle-import:0207_10")
      (libsource (lib "eagle-import") (part "R-US_0207/10"))
    )
    (comp (ref "R59")
      (value "27")
      (footprint "eagle-import:0411_12")
      (libsource (lib "eagle-import") (part "R-US_0411/12"))
    )
    (comp (ref "R60")
      (value "220")
      (footprint "eagle-import:0207_10")
      (libsource (lib "eagle-import") (part "R-US_0207/10"))
    )
    (comp (ref "R61")
      (value "220")
      (footprint "eagle-import:0207_10")
      (libsource (lib "eagle-import") (part "R-US_0207/10"))
    )
    (comp (ref "R62")
      (value "220")
      (footprint "eagle-import:0207_10")
      (libsource (lib "eagle-import") (part "R-US_0207/10"))
    )
    (comp (ref "R65")
      (value "470")
      (footprint "eagle-import:0207_10")
      (libsource (lib "eagle-import") (part "R-US_0207/10"))
    )
    (comp (ref "R66")
      (value "4.7K")
      (footprint "eagle-import:0207_10")
      (libsource (lib "eagle-import") (part "R-US_0207/10"))
    )
    (comp (ref "R67")
      (value "220")
      (footprint "eagle-import:0207_10")
      (libsource (lib "eagle-import") (part "R-US_0207/10"))
    )
    (comp (ref "R68")
      (value "470")
      (footprint "eagle-import:0207_10")
      (libsource (lib "eagle-import") (part "R-US_0207/10"))
    )
    (comp (ref "R72")
      (value "4.7K")
      (footprint "eagle-import:0207_10")
      (libsource (lib "eagle-import") (part "R-US_0207/10"))
    )
    (comp (ref "R73")
      (value "220")
      (footprint "eagle-import:0207_10")
      (libsource (lib "eagle-import") (part "R-US_0207/10"))
    )
    (comp (ref "R74")
      (value "470")
      (footprint "eagle-import:0207_10")
      (libsource (lib "eagle-import") (part "R-US_0207/10"))
    )
    (comp (ref "R75")
      (value "4.7K")
      (footprint "eagle-import:0207_10")
      (libsource (lib "eagle-import") (part "R-US_0207/10"))
    )
    (comp (ref "R78")
      (value "220")
      (footprint "eagle-import:0207_10")
      (libsource (lib "eagle-import") (part "R-US_0207/10"))
    )
    (comp (ref "R79")
      (value "470")
      (footprint "eagle-import:0207_10")
      (libsource (lib "eagle-import") (part "R-US_0207/10"))
    )
    (comp (ref "R80")
      (value "4.7K")
      (footprint "eagle-import:0207_10")
      (libsource (lib "eagle-import") (part "R-US_0207/10"))
    )
    (comp (ref "R81")
      (value "4.7K")
      (footprint "eagle-import:0207_10")
      (libsource (lib "eagle-import") (part "R-US_0207/10"))
    )
    (comp (ref "R82")
      (value "470")
      (footprint "eagle-import:0207_10")
      (libsource (lib "eagle-import") (part "R-US_0207/10"))
    )
    (comp (ref "R83")
      (value "4.7K")
      (footprint "eagle-import:0207_10")
      (libsource (lib "eagle-import") (part "R-US_0207/10"))
    )
    (comp (ref "R84")
      (value "470")
      (footprint "eagle-import:0207_10")
      (libsource (lib "eagle-import") (part "R-US_0207/10"))
    )
    (comp (ref "R97")
      (value "4.7K")
      (footprint "eagle-import:0207_10")
      (libsource (lib "eagle-import") (part "R-US_0207/10"))
    )
    (comp (ref "R98")
      (value "470")
      (footprint "eagle-import:0207_10")
      (libsource (lib "eagle-import") (part "R-US_0207/10"))
    )
    (comp (ref "R99")
      (value "4.7K")
      (footprint "eagle-import:0207_10")
      (libsource (lib "eagle-import") (part "R-US_0207/10"))
    )
    (comp (ref "R100")
      (value "470")
      (footprint "eagle-import:0207_10")
      (libsource (lib "eagle-import") (part "R-US_0207/10"))
    )
    (comp (ref "R101")
      (value "4.7K")
      (footprint "eagle-import:0207_10")
      (libsource (lib "eagle-import") (part "R-US_0207/10"))
    )
    (comp (ref "R102")
      (value "470")
      (footprint "eagle-import:0207_10")
      (libsource (lib "eagle-import") (part "R-US_0207/10"))
    )
    (comp (ref "R103")
      (value "4.7K")
      (footprint "eagle-import:0207_10")
      (libsource (lib "eagle-import") (part "R-US_0207/10"))
    )
    (comp (ref "R104")
      (value "470")
      (footprint "eagle-import:0207_10")
      (libsource (lib "eagle-import") (part "R-US_0207/10"))
    )
    (comp (ref "U$1")
      (value "OUTLINE-OMNIBUS")
      (footprint "eagle-import:OMNIBUS")
      (libsource (lib "eagle-import") (part "OUTLINE-OMNIBUS"))
    )
    (comp (ref "C26")
      (value "15pf")
      (footprint "eagle-import:C050-025X075")
      (libsource (lib "eagle-import") (part "C-US050-025X075"))
    )
    (comp (ref "C27")
      (value "15pf")
      (footprint "eagle-import:C050-025X075")
      (libsource (lib "eagle-import") (part "C-US050-025X075"))
    )
    (comp (ref "C28")
      (value "15pf")
      (footprint "eagle-import:C050-025X075")
      (libsource (lib "eagle-import") (part "C-US050-025X075"))
    )
    (comp (ref "C29")
      (value "15pf")
      (footprint "eagle-import:C050-025X075")
      (libsource (lib "eagle-import") (part "C-US050-025X075"))
    )
    (comp (ref "C30")
      (value "15pf")
      (footprint "eagle-import:C050-025X075")
      (libsource (lib "eagle-import") (part "C-US050-025X075"))
    )
    (comp (ref "C31")
      (value "15pf")
      (footprint "eagle-import:C050-025X075")
      (libsource (lib "eagle-import") (part "C-US050-025X075"))
    )
    (comp (ref "C33")
      (value "15pf")
      (footprint "eagle-import:C050-025X075")
      (libsource (lib "eagle-import") (part "C-US050-025X075"))
    )
    (comp (ref "C34")
      (value "15pf")
      (footprint "eagle-import:C050-025X075")
      (libsource (lib "eagle-import") (part "C-US050-025X075"))
    )
    (comp (ref "C35")
      (value "15pf")
      (footprint "eagle-import:C050-025X075")
      (libsource (lib "eagle-import") (part "C-US050-025X075"))
    )
    (comp (ref "C36")
      (value "15pf")
      (footprint "eagle-import:C050-025X075")
      (libsource (lib "eagle-import") (part "C-US050-025X075"))
    )
    (comp (ref "C37")
      (value "15pf")
      (footprint "eagle-import:C050-025X075")
      (libsource (lib "eagle-import") (part "C-US050-025X075"))
    )
    (comp (ref "C38")
      (value "15pf")
      (footprint "eagle-import:C050-025X075")
      (libsource (lib "eagle-import") (part "C-US050-025X075"))
    )
    (comp (ref "C39")
      (value "15pf")
      (footprint "eagle-import:C050-025X075")
      (libsource (lib "eagle-import") (part "C-US050-025X075"))
    )
    (comp (ref "C40")
      (value "15pf")
      (footprint "eagle-import:C050-025X075")
      (libsource (lib "eagle-import") (part "C-US050-025X075"))
    )
    (comp (ref "C41")
      (value "15pf")
      (footprint "eagle-import:C050-025X075")
      (libsource (lib "eagle-import") (part "C-US050-025X075"))
    )
    (comp (ref "C42")
      (value "15pf")
      (footprint "eagle-import:C050-025X075")
      (libsource (lib "eagle-import") (part "C-US050-025X075"))
    )
    (comp (ref "D39")
      (value "D664")
      (footprint "eagle-import:DO35-10")
      (libsource (lib "eagle-import") (part "1N4148DO35-10"))
    )
    (comp (ref "D138")
      (value "D664")
      (footprint "eagle-import:DO35-10")
      (libsource (lib "eagle-import") (part "1N4148DO35-10"))
    )
    (comp (ref "D139")
      (value "D664")
      (footprint "eagle-import:DO35-10")
      (libsource (lib "eagle-import") (part "1N4148DO35-10"))
    )
    (comp (ref "D140")
      (value "D664")
      (footprint "eagle-import:DO35-10")
      (libsource (lib "eagle-import") (part "1N4148DO35-10"))
    )
    (comp (ref "D141")
      (value "D664")
      (footprint "eagle-import:DO35-10")
      (libsource (lib "eagle-import") (part "1N4148DO35-10"))
    )
    (comp (ref "D142")
      (value "D664")
      (footprint "eagle-import:DO35-10")
      (libsource (lib "eagle-import") (part "1N4148DO35-10"))
    )
    (comp (ref "D143")
      (value "D664")
      (footprint "eagle-import:DO35-10")
      (libsource (lib "eagle-import") (part "1N4148DO35-10"))
    )
    (comp (ref "D144")
      (value "D664")
      (footprint "eagle-import:DO35-10")
      (libsource (lib "eagle-import") (part "1N4148DO35-10"))
    )
    (comp (ref "D145")
      (value "D664")
      (footprint "eagle-import:DO35-10")
      (libsource (lib "eagle-import") (part "1N4148DO35-10"))
    )
    (comp (ref "D146")
      (value "D664")
      (footprint "eagle-import:DO35-10")
      (libsource (lib "eagle-import") (part "1N4148DO35-10"))
    )
    (comp (ref "D147")
      (value "D664")
      (footprint "eagle-import:DO35-10")
      (libsource (lib "eagle-import") (part "1N4148DO35-10"))
    )
    (comp (ref "D148")
      (value "D664")
      (footprint "eagle-import:DO35-10")
      (libsource (lib "eagle-import") (part "1N4148DO35-10"))
    )
    (comp (ref "D149")
      (value "D664")
      (footprint "eagle-import:DO35-10")
      (libsource (lib "eagle-import") (part "1N4148DO35-10"))
    )
    (comp (ref "D150")
      (value "D664")
      (footprint "eagle-import:DO35-10")
      (libsource (lib "eagle-import") (part "1N4148DO35-10"))
    )
    (comp (ref "D151")
      (value "D664")
      (footprint "eagle-import:DO35-10")
      (libsource (lib "eagle-import") (part "1N4148DO35-10"))
    )
    (comp (ref "D152")
      (value "D664")
      (footprint "eagle-import:DO35-10")
      (libsource (lib "eagle-import") (part "1N4148DO35-10"))
    )
    (comp (ref "D153")
      (value "D664")
      (footprint "eagle-import:DO35-10")
      (libsource (lib "eagle-import") (part "1N4148DO35-10"))
    )
    (comp (ref "D154")
      (value "D664")
      (footprint "eagle-import:DO35-10")
      (libsource (lib "eagle-import") (part "1N4148DO35-10"))
    )
    (comp (ref "D155")
      (value "D664")
      (footprint "eagle-import:DO35-10")
      (libsource (lib "eagle-import") (part "1N4148DO35-10"))
    )
    (comp (ref "D156")
      (value "D664")
      (footprint "eagle-import:DO35-10")
      (libsource (lib "eagle-import") (part "1N4148DO35-10"))
    )
    (comp (ref "D157")
      (value "D664")
      (footprint "eagle-import:DO35-10")
      (libsource (lib "eagle-import") (part "1N4148DO35-10"))
    )
    (comp (ref "D158")
      (value "D664")
      (footprint "eagle-import:DO35-10")
      (libsource (lib "eagle-import") (part "1N4148DO35-10"))
    )
    (comp (ref "D159")
      (value "D664")
      (footprint "eagle-import:DO35-10")
      (libsource (lib "eagle-import") (part "1N4148DO35-10"))
    )
    (comp (ref "D160")
      (value "D664")
      (footprint "eagle-import:DO35-10")
      (libsource (lib "eagle-import") (part "1N4148DO35-10"))
    )
    (comp (ref "D161")
      (value "D664")
      (footprint "eagle-import:DO35-10")
      (libsource (lib "eagle-import") (part "1N4148DO35-10"))
    )
    (comp (ref "D162")
      (value "D664")
      (footprint "eagle-import:DO35-10")
      (libsource (lib "eagle-import") (part "1N4148DO35-10"))
    )
    (comp (ref "D163")
      (value "D664")
      (footprint "eagle-import:DO35-10")
      (libsource (lib "eagle-import") (part "1N4148DO35-10"))
    )
    (comp (ref "D164")
      (value "D664")
      (footprint "eagle-import:DO35-10")
      (libsource (lib "eagle-import") (part "1N4148DO35-10"))
    )
    (comp (ref "D165")
      (value "D664")
      (footprint "eagle-import:DO35-10")
      (libsource (lib "eagle-import") (part "1N4148DO35-10"))
    )
    (comp (ref "D166")
      (value "D664")
      (footprint "eagle-import:DO35-10")
      (libsource (lib "eagle-import") (part "1N4148DO35-10"))
    )
    (comp (ref "D167")
      (value "D664")
      (footprint "eagle-import:DO35-10")
      (libsource (lib "eagle-import") (part "1N4148DO35-10"))
    )
    (comp (ref "D168")
      (value "D664")
      (footprint "eagle-import:DO35-10")
      (libsource (lib "eagle-import") (part "1N4148DO35-10"))
    )
    (comp (ref "D169")
      (value "D664")
      (footprint "eagle-import:DO35-10")
      (libsource (lib "eagle-import") (part "1N4148DO35-10"))
    )
    (comp (ref "D170")
      (value "D664")
      (footprint "eagle-import:DO35-10")
      (libsource (lib "eagle-import") (part "1N4148DO35-10"))
    )
    (comp (ref "D171")
      (value "D664")
      (footprint "eagle-import:DO35-10")
      (libsource (lib "eagle-import") (part "1N4148DO35-10"))
    )
    (comp (ref "D172")
      (value "D664")
      (footprint "eagle-import:DO35-10")
      (libsource (lib "eagle-import") (part "1N4148DO35-10"))
    )
    (comp (ref "D173")
      (value "D664")
      (footprint "eagle-import:DO35-10")
      (libsource (lib "eagle-import") (part "1N4148DO35-10"))
    )
    (comp (ref "D174")
      (value "D664")
      (footprint "eagle-import:DO35-10")
      (libsource (lib "eagle-import") (part "1N4148DO35-10"))
    )
    (comp (ref "D175")
      (value "D664")
      (footprint "eagle-import:DO35-10")
      (libsource (lib "eagle-import") (part "1N4148DO35-10"))
    )
    (comp (ref "D176")
      (value "D664")
      (footprint "eagle-import:DO35-10")
      (libsource (lib "eagle-import") (part "1N4148DO35-10"))
    )
    (comp (ref "D177")
      (value "D664")
      (footprint "eagle-import:DO35-10")
      (libsource (lib "eagle-import") (part "1N4148DO35-10"))
    )
    (comp (ref "D178")
      (value "D664")
      (footprint "eagle-import:DO35-10")
      (libsource (lib "eagle-import") (part "1N4148DO35-10"))
    )
    (comp (ref "D179")
      (value "D664")
      (footprint "eagle-import:DO35-10")
      (libsource (lib "eagle-import") (part "1N4148DO35-10"))
    )
    (comp (ref "D180")
      (value "D664")
      (footprint "eagle-import:DO35-10")
      (libsource (lib "eagle-import") (part "1N4148DO35-10"))
    )
    (comp (ref "D181")
      (value "D664")
      (footprint "eagle-import:DO35-10")
      (libsource (lib "eagle-import") (part "1N4148DO35-10"))
    )
    (comp (ref "D182")
      (value "D664")
      (footprint "eagle-import:DO35-10")
      (libsource (lib "eagle-import") (part "1N4148DO35-10"))
    )
    (comp (ref "D183")
      (value "D664")
      (footprint "eagle-import:DO35-10")
      (libsource (lib "eagle-import") (part "1N4148DO35-10"))
    )
    (comp (ref "D184")
      (value "D664")
      (footprint "eagle-import:DO35-10")
      (libsource (lib "eagle-import") (part "1N4148DO35-10"))
    )
    (comp (ref "E4")
      (value "7404N")
      (footprint "eagle-import:DIL14")
      (libsource (lib "eagle-import") (part "7404N"))
    )
    (comp (ref "E48")
      (value "7404N")
      (footprint "eagle-import:DIL14")
      (libsource (lib "eagle-import") (part "7404N"))
    )
    (comp (ref "E49")
      (value "7404N")
      (footprint "eagle-import:DIL14")
      (libsource (lib "eagle-import") (part "7404N"))
    )
    (comp (ref "Q1A")
      (value "2N3639B")
      (footprint "eagle-import:TO39")
      (libsource (lib "eagle-import") (part "2N3637"))
    )
    (comp (ref "Q2A")
      (value "2N3639B")
      (footprint "eagle-import:TO39")
      (libsource (lib "eagle-import") (part "2N3637"))
    )
    (comp (ref "Q3A")
      (value "2N3639B")
      (footprint "eagle-import:TO39")
      (libsource (lib "eagle-import") (part "2N3637"))
    )
    (comp (ref "Q4A")
      (value "2N3639B")
      (footprint "eagle-import:TO39")
      (libsource (lib "eagle-import") (part "2N3637"))
    )
    (comp (ref "Q5A")
      (value "2N3639B")
      (footprint "eagle-import:TO39")
      (libsource (lib "eagle-import") (part "2N3637"))
    )
    (comp (ref "Q6A")
      (value "2N3639B")
      (footprint "eagle-import:TO39")
      (libsource (lib "eagle-import") (part "2N3637"))
    )
    (comp (ref "Q7")
      (value "2N3639B")
      (footprint "eagle-import:TO39")
      (libsource (lib "eagle-import") (part "2N3637"))
    )
    (comp (ref "Q7A")
      (value "2N3639B")
      (footprint "eagle-import:TO39")
      (libsource (lib "eagle-import") (part "2N3637"))
    )
    (comp (ref "Q8A")
      (value "2N3639B")
      (footprint "eagle-import:TO39")
      (libsource (lib "eagle-import") (part "2N3637"))
    )
    (comp (ref "Q9A")
      (value "2N3639B")
      (footprint "eagle-import:TO39")
      (libsource (lib "eagle-import") (part "2N3637"))
    )
    (comp (ref "Q10A")
      (value "2N3639B")
      (footprint "eagle-import:TO39")
      (libsource (lib "eagle-import") (part "2N3637"))
    )
    (comp (ref "Q11A")
      (value "2N3639B")
      (footprint "eagle-import:TO39")
      (libsource (lib "eagle-import") (part "2N3637"))
    )
    (comp (ref "Q12A")
      (value "2N3639B")
      (footprint "eagle-import:TO39")
      (libsource (lib "eagle-import") (part "2N3637"))
    )
    (comp (ref "Q50")
      (value "2N3639B")
      (footprint "eagle-import:TO39")
      (libsource (lib "eagle-import") (part "2N3637"))
    )
    (comp (ref "Q51")
      (value "2N3639B")
      (footprint "eagle-import:TO39")
      (libsource (lib "eagle-import") (part "2N3637"))
    )
    (comp (ref "Q52")
      (value "2N3639B")
      (footprint "eagle-import:TO39")
      (libsource (lib "eagle-import") (part "2N3637"))
    )
    (comp (ref "R41")
      (value "220")
      (footprint "eagle-import:0207_10")
      (libsource (lib "eagle-import") (part "R-US_0207/10"))
    )
    (comp (ref "R63")
      (value "220")
      (footprint "eagle-import:0207_10")
      (libsource (lib "eagle-import") (part "R-US_0207/10"))
    )
    (comp (ref "R64")
      (value "220")
      (footprint "eagle-import:0207_10")
      (libsource (lib "eagle-import") (part "R-US_0207/10"))
    )
    (comp (ref "R69")
      (value "1K")
      (footprint "eagle-import:0207_10")
      (libsource (lib "eagle-import") (part "R-US_0207/10"))
    )
    (comp (ref "R70")
      (value "5.6K")
      (footprint "eagle-import:0207_10")
      (libsource (lib "eagle-import") (part "R-US_0207/10"))
    )
    (comp (ref "R85")
      (value "220")
      (footprint "eagle-import:0207_10")
      (libsource (lib "eagle-import") (part "R-US_0207/10"))
    )
    (comp (ref "R86")
      (value "220")
      (footprint "eagle-import:0207_10")
      (libsource (lib "eagle-import") (part "R-US_0207/10"))
    )
    (comp (ref "R87")
      (value "220")
      (footprint "eagle-import:0207_10")
      (libsource (lib "eagle-import") (part "R-US_0207/10"))
    )
    (comp (ref "R88")
      (value "220")
      (footprint "eagle-import:0207_10")
      (libsource (lib "eagle-import") (part "R-US_0207/10"))
    )
    (comp (ref "R89")
      (value "220")
      (footprint "eagle-import:0207_10")
      (libsource (lib "eagle-import") (part "R-US_0207/10"))
    )
    (comp (ref "R90")
      (value "220")
      (footprint "eagle-import:0207_10")
      (libsource (lib "eagle-import") (part "R-US_0207/10"))
    )
    (comp (ref "R91")
      (value "220")
      (footprint "eagle-import:0207_10")
      (libsource (lib "eagle-import") (part "R-US_0207/10"))
    )
    (comp (ref "R92")
      (value "220")
      (footprint "eagle-import:0207_10")
      (libsource (lib "eagle-import") (part "R-US_0207/10"))
    )
    (comp (ref "R93")
      (value "220")
      (footprint "eagle-import:0207_10")
      (libsource (lib "eagle-import") (part "R-US_0207/10"))
    )
    (comp (ref "R94")
      (value "220")
      (footprint "eagle-import:0207_10")
      (libsource (lib "eagle-import") (part "R-US_0207/10"))
    )
    (comp (ref "R95")
      (value "220")
      (footprint "eagle-import:0207_10")
      (libsource (lib "eagle-import") (part "R-US_0207/10"))
    )
    (comp (ref "R96")
      (value "220")
      (footprint "eagle-import:0207_10")
      (libsource (lib "eagle-import") (part "R-US_0207/10"))
    )
    (comp (ref "R130")
      (value "1K")
      (footprint "eagle-import:0207_10")
      (libsource (lib "eagle-import") (part "R-US_0207/10"))
    )
    (comp (ref "R131")
      (value "5.6K")
      (footprint "eagle-import:0207_10")
      (libsource (lib "eagle-import") (part "R-US_0207/10"))
    )
    (comp (ref "R132")
      (value "1K")
      (footprint "eagle-import:0207_10")
      (libsource (lib "eagle-import") (part "R-US_0207/10"))
    )
    (comp (ref "R133")
      (value "5.6K")
      (footprint "eagle-import:0207_10")
      (libsource (lib "eagle-import") (part "R-US_0207/10"))
    )
    (comp (ref "R134")
      (value "1K")
      (footprint "eagle-import:0207_10")
      (libsource (lib "eagle-import") (part "R-US_0207/10"))
    )
    (comp (ref "R135")
      (value "5.6K")
      (footprint "eagle-import:0207_10")
      (libsource (lib "eagle-import") (part "R-US_0207/10"))
    )
    (comp (ref "R136")
      (value "1K")
      (footprint "eagle-import:0207_10")
      (libsource (lib "eagle-import") (part "R-US_0207/10"))
    )
    (comp (ref "R137")
      (value "5.6K")
      (footprint "eagle-import:0207_10")
      (libsource (lib "eagle-import") (part "R-US_0207/10"))
    )
    (comp (ref "R138")
      (value "1K")
      (footprint "eagle-import:0207_10")
      (libsource (lib "eagle-import") (part "R-US_0207/10"))
    )
    (comp (ref "R139")
      (value "5.6K")
      (footprint "eagle-import:0207_10")
      (libsource (lib "eagle-import") (part "R-US_0207/10"))
    )
    (comp (ref "R140")
      (value "1K")
      (footprint "eagle-import:0207_10")
      (libsource (lib "eagle-import") (part "R-US_0207/10"))
    )
    (comp (ref "R141")
      (value "5.6K")
      (footprint "eagle-import:0207_10")
      (libsource (lib "eagle-import") (part "R-US_0207/10"))
    )
    (comp (ref "R142")
      (value "1K")
      (footprint "eagle-import:0207_10")
      (libsource (lib "eagle-import") (part "R-US_0207/10"))
    )
    (comp (ref "R143")
      (value "5.6K")
      (footprint "eagle-import:0207_10")
      (libsource (lib "eagle-import") (part "R-US_0207/10"))
    )
    (comp (ref "R144")
      (value "1K")
      (footprint "eagle-import:0207_10")
      (libsource (lib "eagle-import") (part "R-US_0207/10"))
    )
    (comp (ref "R145")
      (value "5.6K")
      (footprint "eagle-import:0207_10")
      (libsource (lib "eagle-import") (part "R-US_0207/10"))
    )
    (comp (ref "R146")
      (value "1K")
      (footprint "eagle-import:0207_10")
      (libsource (lib "eagle-import") (part "R-US_0207/10"))
    )
    (comp (ref "R147")
      (value "5.6K")
      (footprint "eagle-import:0207_10")
      (libsource (lib "eagle-import") (part "R-US_0207/10"))
    )
    (comp (ref "R148")
      (value "1K")
      (footprint "eagle-import:0207_10")
      (libsource (lib "eagle-import") (part "R-US_0207/10"))
    )
    (comp (ref "R149")
      (value "5.6K")
      (footprint "eagle-import:0207_10")
      (libsource (lib "eagle-import") (part "R-US_0207/10"))
    )
    (comp (ref "R150")
      (value "1K")
      (footprint "eagle-import:0207_10")
      (libsource (lib "eagle-import") (part "R-US_0207/10"))
    )
    (comp (ref "R151")
      (value "5.6K")
      (footprint "eagle-import:0207_10")
      (libsource (lib "eagle-import") (part "R-US_0207/10"))
    )
    (comp (ref "R152")
      (value "1K")
      (footprint "eagle-import:0207_10")
      (libsource (lib "eagle-import") (part "R-US_0207/10"))
    )
    (comp (ref "R153")
      (value "5.6K")
      (footprint "eagle-import:0207_10")
      (libsource (lib "eagle-import") (part "R-US_0207/10"))
    )
    (comp (ref "R154")
      (value "220")
      (footprint "eagle-import:0207_10")
      (libsource (lib "eagle-import") (part "R-US_0207/10"))
    )
    (comp (ref "R155")
      (value "1K")
      (footprint "eagle-import:0207_10")
      (libsource (lib "eagle-import") (part "R-US_0207/10"))
    )
    (comp (ref "R156")
      (value "5.6K")
      (footprint "eagle-import:0207_10")
      (libsource (lib "eagle-import") (part "R-US_0207/10"))
    )
    (comp (ref "R157")
      (value "1K")
      (footprint "eagle-import:0207_10")
      (libsource (lib "eagle-import") (part "R-US_0207/10"))
    )
    (comp (ref "R158")
      (value "5.6K")
      (footprint "eagle-import:0207_10")
      (libsource (lib "eagle-import") (part "R-US_0207/10"))
    )
    (comp (ref "R159")
      (value "1K")
      (footprint "eagle-import:0207_10")
      (libsource (lib "eagle-import") (part "R-US_0207/10"))
    )
    (comp (ref "R160")
      (value "5.6K")
      (footprint "eagle-import:0207_10")
      (libsource (lib "eagle-import") (part "R-US_0207/10"))
    )
    (comp (ref "NACI00")
      (value "ML34L")
      (footprint "eagle-import:ML34L")
      (libsource (lib "eagle-import") (part "ML34L"))
    )
    (comp (ref "NACI09")
      (value "ML34L")
      (footprint "eagle-import:ML34L")
      (libsource (lib "eagle-import") (part "ML34L"))
    )
    (comp (ref "NBAC00")
      (value "ML34L")
      (footprint "eagle-import:ML34L")
      (libsource (lib "eagle-import") (part "ML34L"))
    )
    (comp (ref "NBAC09")
      (value "ML34L")
      (footprint "eagle-import:ML34L")
      (libsource (lib "eagle-import") (part "ML34L"))
    )
    (comp (ref "NBMB00")
      (value "ML34L")
      (footprint "eagle-import:ML34L")
      (libsource (lib "eagle-import") (part "ML34L"))
    )
    (comp (ref "NBMB06")
      (value "ML34L")
      (footprint "eagle-import:ML34L")
      (libsource (lib "eagle-import") (part "ML34L"))
    )
    (comp (ref "U$3")
      (value "QUAD")
      (footprint "eagle-import:EDGE-CON8")
      (libsource (lib "eagle-import") (part "QUAD"))
    )
    (comp (ref "C13")
      (value ".01uF")
      (footprint "eagle-import:C050-025X075")
      (libsource (lib "eagle-import") (part "C-US050-025X075"))
    )
    (comp (ref "C14")
      (value ".01uF")
      (footprint "eagle-import:C050-025X075")
      (libsource (lib "eagle-import") (part "C-US050-025X075"))
    )
    (comp (ref "C15")
      (value ".01uF")
      (footprint "eagle-import:C050-025X075")
      (libsource (lib "eagle-import") (part "C-US050-025X075"))
    )
    (comp (ref "C16")
      (value ".01uF")
      (footprint "eagle-import:C050-025X075")
      (libsource (lib "eagle-import") (part "C-US050-025X075"))
    )
    (comp (ref "D13")
      (value "1N3606")
      (footprint "eagle-import:DO35-10")
      (libsource (lib "eagle-import") (part "DIODE-DO35-10"))
    )
    (comp (ref "D14")
      (value "1N3606")
      (footprint "eagle-import:DO35-10")
      (libsource (lib "eagle-import") (part "DIODE-DO35-10"))
    )
    (comp (ref "D15")
      (value "1N3606")
      (footprint "eagle-import:DO35-10")
      (libsource (lib "eagle-import") (part "DIODE-DO35-10"))
    )
    (comp (ref "D16")
      (value "1N3606")
      (footprint "eagle-import:DO35-10")
      (libsource (lib "eagle-import") (part "DIODE-DO35-10"))
    )
    (comp (ref "D17")
      (value "1N3606")
      (footprint "eagle-import:DO35-10")
      (libsource (lib "eagle-import") (part "DIODE-DO35-10"))
    )
    (comp (ref "D18")
      (value "1N3606")
      (footprint "eagle-import:DO35-10")
      (libsource (lib "eagle-import") (part "DIODE-DO35-10"))
    )
    (comp (ref "D19")
      (value "1N3606")
      (footprint "eagle-import:DO35-10")
      (libsource (lib "eagle-import") (part "DIODE-DO35-10"))
    )
    (comp (ref "D20")
      (value "1N3606")
      (footprint "eagle-import:DO35-10")
      (libsource (lib "eagle-import") (part "DIODE-DO35-10"))
    )
    (comp (ref "D21")
      (value "1N3606")
      (footprint "eagle-import:DO35-10")
      (libsource (lib "eagle-import") (part "DIODE-DO35-10"))
    )
    (comp (ref "D22")
      (value "1N3606")
      (footprint "eagle-import:DO35-10")
      (libsource (lib "eagle-import") (part "DIODE-DO35-10"))
    )
    (comp (ref "D23")
      (value "1N3606")
      (footprint "eagle-import:DO35-10")
      (libsource (lib "eagle-import") (part "DIODE-DO35-10"))
    )
    (comp (ref "D24")
      (value "1N3606")
      (footprint "eagle-import:DO35-10")
      (libsource (lib "eagle-import") (part "DIODE-DO35-10"))
    )
    (comp (ref "D25")
      (value "1N3606")
      (footprint "eagle-import:DO35-10")
      (libsource (lib "eagle-import") (part "DIODE-DO35-10"))
    )
    (comp (ref "D26")
      (value "1N3606")
      (footprint "eagle-import:DO35-10")
      (libsource (lib "eagle-import") (part "DIODE-DO35-10"))
    )
    (comp (ref "D27")
      (value "1N3606")
      (footprint "eagle-import:DO35-10")
      (libsource (lib "eagle-import") (part "DIODE-DO35-10"))
    )
    (comp (ref "D28")
      (value "1N3606")
      (footprint "eagle-import:DO35-10")
      (libsource (lib "eagle-import") (part "DIODE-DO35-10"))
    )
    (comp (ref "D29")
      (value "1N3606")
      (footprint "eagle-import:DO35-10")
      (libsource (lib "eagle-import") (part "DIODE-DO35-10"))
    )
    (comp (ref "D30")
      (value "1N3606")
      (footprint "eagle-import:DO35-10")
      (libsource (lib "eagle-import") (part "DIODE-DO35-10"))
    )
    (comp (ref "D44")
      (value "1N645")
      (footprint "eagle-import:DO35-10")
      (libsource (lib "eagle-import") (part "DIODE-DO35-10"))
    )
    (comp (ref "D45")
      (value "1N645")
      (footprint "eagle-import:DO35-10")
      (libsource (lib "eagle-import") (part "DIODE-DO35-10"))
    )
    (comp (ref "D46")
      (value "1N645")
      (footprint "eagle-import:DO35-10")
      (libsource (lib "eagle-import") (part "DIODE-DO35-10"))
    )
    (comp (ref "D47")
      (value "1N645")
      (footprint "eagle-import:DO35-10")
      (libsource (lib "eagle-import") (part "DIODE-DO35-10"))
    )
    (comp (ref "D48")
      (value "1N645")
      (footprint "eagle-import:DO35-10")
      (libsource (lib "eagle-import") (part "DIODE-DO35-10"))
    )
    (comp (ref "D49")
      (value "1N645")
      (footprint "eagle-import:DO35-10")
      (libsource (lib "eagle-import") (part "DIODE-DO35-10"))
    )
    (comp (ref "D50")
      (value "1N645")
      (footprint "eagle-import:DO35-10")
      (libsource (lib "eagle-import") (part "DIODE-DO35-10"))
    )
    (comp (ref "D51")
      (value "1N645")
      (footprint "eagle-import:DO35-10")
      (libsource (lib "eagle-import") (part "DIODE-DO35-10"))
    )
    (comp (ref "D52")
      (value "1N645")
      (footprint "eagle-import:DO35-10")
      (libsource (lib "eagle-import") (part "DIODE-DO35-10"))
    )
    (comp (ref "D53")
      (value "1N645")
      (footprint "eagle-import:DO35-10")
      (libsource (lib "eagle-import") (part "DIODE-DO35-10"))
    )
    (comp (ref "D114")
      (value "D664")
      (footprint "eagle-import:DO35-10")
      (libsource (lib "eagle-import") (part "1N4148DO35-10"))
    )
    (comp (ref "D115")
      (value "D664")
      (footprint "eagle-import:DO35-10")
      (libsource (lib "eagle-import") (part "1N4148DO35-10"))
    )
    (comp (ref "D116")
      (value "D664")
      (footprint "eagle-import:DO35-10")
      (libsource (lib "eagle-import") (part "1N4148DO35-10"))
    )
    (comp (ref "D117")
      (value "D664")
      (footprint "eagle-import:DO35-10")
      (libsource (lib "eagle-import") (part "1N4148DO35-10"))
    )
    (comp (ref "D118")
      (value "D664")
      (footprint "eagle-import:DO35-10")
      (libsource (lib "eagle-import") (part "1N4148DO35-10"))
    )
    (comp (ref "D119")
      (value "D664")
      (footprint "eagle-import:DO35-10")
      (libsource (lib "eagle-import") (part "1N4148DO35-10"))
    )
    (comp (ref "D120")
      (value "D664")
      (footprint "eagle-import:DO35-10")
      (libsource (lib "eagle-import") (part "1N4148DO35-10"))
    )
    (comp (ref "D121")
      (value "D664")
      (footprint "eagle-import:DO35-10")
      (libsource (lib "eagle-import") (part "1N4148DO35-10"))
    )
    (comp (ref "D122")
      (value "D664")
      (footprint "eagle-import:DO35-10")
      (libsource (lib "eagle-import") (part "1N4148DO35-10"))
    )
    (comp (ref "D123")
      (value "D664")
      (footprint "eagle-import:DO35-10")
      (libsource (lib "eagle-import") (part "1N4148DO35-10"))
    )
    (comp (ref "D124")
      (value "D664")
      (footprint "eagle-import:DO35-10")
      (libsource (lib "eagle-import") (part "1N4148DO35-10"))
    )
    (comp (ref "D125")
      (value "D664")
      (footprint "eagle-import:DO35-10")
      (libsource (lib "eagle-import") (part "1N4148DO35-10"))
    )
    (comp (ref "D126")
      (value "D664")
      (footprint "eagle-import:DO35-10")
      (libsource (lib "eagle-import") (part "1N4148DO35-10"))
    )
    (comp (ref "D127")
      (value "D664")
      (footprint "eagle-import:DO35-10")
      (libsource (lib "eagle-import") (part "1N4148DO35-10"))
    )
    (comp (ref "D128")
      (value "D664")
      (footprint "eagle-import:DO35-10")
      (libsource (lib "eagle-import") (part "1N4148DO35-10"))
    )
    (comp (ref "D129")
      (value "D664")
      (footprint "eagle-import:DO35-10")
      (libsource (lib "eagle-import") (part "1N4148DO35-10"))
    )
    (comp (ref "D130")
      (value "D664")
      (footprint "eagle-import:DO35-10")
      (libsource (lib "eagle-import") (part "1N4148DO35-10"))
    )
    (comp (ref "D131")
      (value "D664")
      (footprint "eagle-import:DO35-10")
      (libsource (lib "eagle-import") (part "1N4148DO35-10"))
    )
    (comp (ref "D132")
      (value "D664")
      (footprint "eagle-import:DO35-10")
      (libsource (lib "eagle-import") (part "1N4148DO35-10"))
    )
    (comp (ref "D133")
      (value "D664")
      (footprint "eagle-import:DO35-10")
      (libsource (lib "eagle-import") (part "1N4148DO35-10"))
    )
    (comp (ref "D134")
      (value "D664")
      (footprint "eagle-import:DO35-10")
      (libsource (lib "eagle-import") (part "1N4148DO35-10"))
    )
    (comp (ref "D135")
      (value "D664")
      (footprint "eagle-import:DO35-10")
      (libsource (lib "eagle-import") (part "1N4148DO35-10"))
    )
    (comp (ref "D136")
      (value "D664")
      (footprint "eagle-import:DO35-10")
      (libsource (lib "eagle-import") (part "1N4148DO35-10"))
    )
    (comp (ref "D137")
      (value "D664")
      (footprint "eagle-import:DO35-10")
      (libsource (lib "eagle-import") (part "1N4148DO35-10"))
    )
    (comp (ref "E13")
      (value "7417N")
      (footprint "eagle-import:DIL14")
      (libsource (lib "eagle-import") (part "74xx-us_7407N"))
    )
    (comp (ref "E17")
      (value "7416N")
      (footprint "eagle-import:DIL14")
      (libsource (lib "eagle-import") (part "7416N"))
    )
    (comp (ref "E18")
      (value "7417N")
      (footprint "eagle-import:DIL14")
      (libsource (lib "eagle-import") (part "74xx-us_7407N"))
    )
    (comp (ref "E21")
      (value "7416N")
      (footprint "eagle-import:DIL14")
      (libsource (lib "eagle-import") (part "7416N"))
    )
    (comp (ref "E22")
      (value "7417N")
      (footprint "eagle-import:DIL14")
      (libsource (lib "eagle-import") (part "74xx-us_7407N"))
    )
    (comp (ref "Q26")
      (value "2N3009B")
      (footprint "eagle-import:TO39")
      (libsource (lib "eagle-import") (part "2N3019"))
    )
    (comp (ref "Q27")
      (value "2N3009B")
      (footprint "eagle-import:TO39")
      (libsource (lib "eagle-import") (part "2N3019"))
    )
    (comp (ref "Q28")
      (value "2N3009B")
      (footprint "eagle-import:TO39")
      (libsource (lib "eagle-import") (part "2N3019"))
    )
    (comp (ref "Q29")
      (value "2N3009B")
      (footprint "eagle-import:TO39")
      (libsource (lib "eagle-import") (part "2N3019"))
    )
    (comp (ref "Q30")
      (value "2N3009B")
      (footprint "eagle-import:TO39")
      (libsource (lib "eagle-import") (part "2N3019"))
    )
    (comp (ref "Q31")
      (value "2N3009B")
      (footprint "eagle-import:TO39")
      (libsource (lib "eagle-import") (part "2N3019"))
    )
    (comp (ref "Q32")
      (value "2N3009B")
      (footprint "eagle-import:TO39")
      (libsource (lib "eagle-import") (part "2N3019"))
    )
    (comp (ref "Q33")
      (value "2N3009B")
      (footprint "eagle-import:TO39")
      (libsource (lib "eagle-import") (part "2N3019"))
    )
    (comp (ref "Q34")
      (value "2N3009B")
      (footprint "eagle-import:TO39")
      (libsource (lib "eagle-import") (part "2N3019"))
    )
    (comp (ref "Q35")
      (value "2N3009B")
      (footprint "eagle-import:TO39")
      (libsource (lib "eagle-import") (part "2N3019"))
    )
    (comp (ref "Q36")
      (value "2N3009B")
      (footprint "eagle-import:TO39")
      (libsource (lib "eagle-import") (part "2N3019"))
    )
    (comp (ref "Q37")
      (value "2N3009B")
      (footprint "eagle-import:TO39")
      (libsource (lib "eagle-import") (part "2N3019"))
    )
    (comp (ref "R25")
      (value "220")
      (footprint "eagle-import:0207_10")
      (libsource (lib "eagle-import") (part "R-US_0207/10"))
    )
    (comp (ref "R26")
      (value "220")
      (footprint "eagle-import:0207_10")
      (libsource (lib "eagle-import") (part "R-US_0207/10"))
    )
    (comp (ref "R27")
      (value "220")
      (footprint "eagle-import:0207_10")
      (libsource (lib "eagle-import") (part "R-US_0207/10"))
    )
    (comp (ref "R28")
      (value "220")
      (footprint "eagle-import:0207_10")
      (libsource (lib "eagle-import") (part "R-US_0207/10"))
    )
    (comp (ref "R29")
      (value "220")
      (footprint "eagle-import:0207_10")
      (libsource (lib "eagle-import") (part "R-US_0207/10"))
    )
    (comp (ref "R30")
      (value "220")
      (footprint "eagle-import:0207_10")
      (libsource (lib "eagle-import") (part "R-US_0207/10"))
    )
    (comp (ref "R31")
      (value "220")
      (footprint "eagle-import:0207_10")
      (libsource (lib "eagle-import") (part "R-US_0207/10"))
    )
    (comp (ref "R32")
      (value "220")
      (footprint "eagle-import:0207_10")
      (libsource (lib "eagle-import") (part "R-US_0207/10"))
    )
    (comp (ref "R33")
      (value "220")
      (footprint "eagle-import:0207_10")
      (libsource (lib "eagle-import") (part "R-US_0207/10"))
    )
    (comp (ref "R34")
      (value "220")
      (footprint "eagle-import:0207_10")
      (libsource (lib "eagle-import") (part "R-US_0207/10"))
    )
    (comp (ref "R35")
      (value "220")
      (footprint "eagle-import:0207_10")
      (libsource (lib "eagle-import") (part "R-US_0207/10"))
    )
    (comp (ref "R36")
      (value "220")
      (footprint "eagle-import:0207_10")
      (libsource (lib "eagle-import") (part "R-US_0207/10"))
    )
    (comp (ref "R37")
      (value "220")
      (footprint "eagle-import:0207_10")
      (libsource (lib "eagle-import") (part "R-US_0207/10"))
    )
    (comp (ref "R38")
      (value "220")
      (footprint "eagle-import:0207_10")
      (libsource (lib "eagle-import") (part "R-US_0207/10"))
    )
    (comp (ref "R39")
      (value "220")
      (footprint "eagle-import:0207_10")
      (libsource (lib "eagle-import") (part "R-US_0207/10"))
    )
    (comp (ref "R40")
      (value "220")
      (footprint "eagle-import:0207_10")
      (libsource (lib "eagle-import") (part "R-US_0207/10"))
    )
    (comp (ref "R42")
      (value "220")
      (footprint "eagle-import:0207_10")
      (libsource (lib "eagle-import") (part "R-US_0207/10"))
    )
    (comp (ref "R43")
      (value "220")
      (footprint "eagle-import:0207_10")
      (libsource (lib "eagle-import") (part "R-US_0207/10"))
    )
    (comp (ref "R76")
      (value "220")
      (footprint "eagle-import:0207_10")
      (libsource (lib "eagle-import") (part "R-US_0207/10"))
    )
    (comp (ref "R77")
      (value "1500")
      (footprint "eagle-import:0207_10")
      (libsource (lib "eagle-import") (part "R-US_0207/10"))
    )
    (comp (ref "R105")
      (value "470")
      (footprint "eagle-import:0207_10")
      (libsource (lib "eagle-import") (part "R-US_0207/10"))
    )
    (comp (ref "R106")
      (value "4.7K")
      (footprint "eagle-import:0207_10")
      (libsource (lib "eagle-import") (part "R-US_0207/10"))
    )
    (comp (ref "R107")
      (value "470")
      (footprint "eagle-import:0207_10")
      (libsource (lib "eagle-import") (part "R-US_0207/10"))
    )
    (comp (ref "R108")
      (value "4.7K")
      (footprint "eagle-import:0207_10")
      (libsource (lib "eagle-import") (part "R-US_0207/10"))
    )
    (comp (ref "R109")
      (value "470")
      (footprint "eagle-import:0207_10")
      (libsource (lib "eagle-import") (part "R-US_0207/10"))
    )
    (comp (ref "R110")
      (value "4.7K")
      (footprint "eagle-import:0207_10")
      (libsource (lib "eagle-import") (part "R-US_0207/10"))
    )
    (comp (ref "R111")
      (value "470")
      (footprint "eagle-import:0207_10")
      (libsource (lib "eagle-import") (part "R-US_0207/10"))
    )
    (comp (ref "R112")
      (value "4.7K")
      (footprint "eagle-import:0207_10")
      (libsource (lib "eagle-import") (part "R-US_0207/10"))
    )
    (comp (ref "R113")
      (value "470")
      (footprint "eagle-import:0207_10")
      (libsource (lib "eagle-import") (part "R-US_0207/10"))
    )
    (comp (ref "R114")
      (value "4.7K")
      (footprint "eagle-import:0207_10")
      (libsource (lib "eagle-import") (part "R-US_0207/10"))
    )
    (comp (ref "R115")
      (value "470")
      (footprint "eagle-import:0207_10")
      (libsource (lib "eagle-import") (part "R-US_0207/10"))
    )
    (comp (ref "R116")
      (value "4.7K")
      (footprint "eagle-import:0207_10")
      (libsource (lib "eagle-import") (part "R-US_0207/10"))
    )
    (comp (ref "R117")
      (value "470")
      (footprint "eagle-import:0207_10")
      (libsource (lib "eagle-import") (part "R-US_0207/10"))
    )
    (comp (ref "R118")
      (value "4.7K")
      (footprint "eagle-import:0207_10")
      (libsource (lib "eagle-import") (part "R-US_0207/10"))
    )
    (comp (ref "R119")
      (value "470")
      (footprint "eagle-import:0207_10")
      (libsource (lib "eagle-import") (part "R-US_0207/10"))
    )
    (comp (ref "R120")
      (value "4.7K")
      (footprint "eagle-import:0207_10")
      (libsource (lib "eagle-import") (part "R-US_0207/10"))
    )
    (comp (ref "R121")
      (value "470")
      (footprint "eagle-import:0207_10")
      (libsource (lib "eagle-import") (part "R-US_0207/10"))
    )
    (comp (ref "R122")
      (value "4.7K")
      (footprint "eagle-import:0207_10")
      (libsource (lib "eagle-import") (part "R-US_0207/10"))
    )
    (comp (ref "R123")
      (value "470")
      (footprint "eagle-import:0207_10")
      (libsource (lib "eagle-import") (part "R-US_0207/10"))
    )
    (comp (ref "R124")
      (value "4.7K")
      (footprint "eagle-import:0207_10")
      (libsource (lib "eagle-import") (part "R-US_0207/10"))
    )
    (comp (ref "R125")
      (value "470")
      (footprint "eagle-import:0207_10")
      (libsource (lib "eagle-import") (part "R-US_0207/10"))
    )
    (comp (ref "R126")
      (value "4.7K")
      (footprint "eagle-import:0207_10")
      (libsource (lib "eagle-import") (part "R-US_0207/10"))
    )
    (comp (ref "R127")
      (value "470")
      (footprint "eagle-import:0207_10")
      (libsource (lib "eagle-import") (part "R-US_0207/10"))
    )
    (comp (ref "R128")
      (value "4.7K")
      (footprint "eagle-import:0207_10")
      (libsource (lib "eagle-import") (part "R-US_0207/10"))
    )
    (comp (ref "R129")
      (value "1500")
      (footprint "eagle-import:0207_10")
      (libsource (lib "eagle-import") (part "R-US_0207/10"))
    )
  )
  (nets
    (net (code "1") (name "+3.75") (class "Default")
      (node (ref "C16") (pin "1") (pinfunction "1_1") (pintype "passive"))
      (node (ref "D31") (pin "C") (pinfunction "C_C") (pintype "passive"))
      (node (ref "D32") (pin "C") (pinfunction "C_C") (pintype "passive"))
      (node (ref "D33") (pin "C") (pinfunction "C_C") (pintype "passive"))
      (node (ref "D34") (pin "C") (pinfunction "C_C") (pintype "passive"))
      (node (ref "D35") (pin "C") (pinfunction "C_C") (pintype "passive"))
      (node (ref "D36") (pin "C") (pinfunction "C_C") (pintype "passive"))
      (node (ref "D37") (pin "C") (pinfunction "C_C") (pintype "passive"))
      (node (ref "D38") (pin "C") (pinfunction "C_C") (pintype "passive"))
      (node (ref "D40") (pin "C") (pinfunction "C_C") (pintype "passive"))
      (node (ref "D41") (pin "C") (pinfunction "C_C") (pintype "passive"))
      (node (ref "D42") (pin "C") (pinfunction "C_C") (pintype "passive"))
      (node (ref "D43") (pin "C") (pinfunction "C_C") (pintype "passive"))
      (node (ref "D53") (pin "A") (pinfunction "A_A") (pintype "passive"))
      (node (ref "R76") (pin "1") (pinfunction "1_1") (pintype "passive"))
    )
    (net (code "2") (name "+3V") (class "Default")
      (node (ref "D101") (pin "C") (pinfunction "C_C") (pintype "passive"))
      (node (ref "D107") (pin "C") (pinfunction "C_C") (pintype "passive"))
      (node (ref "D113") (pin "C") (pinfunction "C_C") (pintype "passive"))
      (node (ref "D83") (pin "C") (pinfunction "C_C") (pintype "passive"))
      (node (ref "D89") (pin "C") (pinfunction "C_C") (pintype "passive"))
      (node (ref "D95") (pin "C") (pinfunction "C_C") (pintype "passive"))
    )
    (net (code "3") (name "+3V3") (class "Default")
      (node (ref "C15") (pin "1") (pinfunction "1_1") (pintype "passive"))
      (node (ref "D1") (pin "C") (pinfunction "C_C") (pintype "passive"))
      (node (ref "D11") (pin "C") (pinfunction "C_C") (pintype "passive"))
      (node (ref "D13") (pin "C") (pinfunction "C_C") (pintype "passive"))
      (node (ref "D14") (pin "C") (pinfunction "C_C") (pintype "passive"))
      (node (ref "D15") (pin "C") (pinfunction "C_C") (pintype "passive"))
      (node (ref "D16") (pin "C") (pinfunction "C_C") (pintype "passive"))
      (node (ref "D17") (pin "C") (pinfunction "C_C") (pintype "passive"))
      (node (ref "D18") (pin "C") (pinfunction "C_C") (pintype "passive"))
      (node (ref "D19") (pin "C") (pinfunction "C_C") (pintype "passive"))
      (node (ref "D2") (pin "C") (pinfunction "C_C") (pintype "passive"))
      (node (ref "D20") (pin "C") (pinfunction "C_C") (pintype "passive"))
      (node (ref "D21") (pin "C") (pinfunction "C_C") (pintype "passive"))
      (node (ref "D22") (pin "C") (pinfunction "C_C") (pintype "passive"))
      (node (ref "D23") (pin "C") (pinfunction "C_C") (pintype "passive"))
      (node (ref "D24") (pin "C") (pinfunction "C_C") (pintype "passive"))
      (node (ref "D25") (pin "C") (pinfunction "C_C") (pintype "passive"))
      (node (ref "D26") (pin "C") (pinfunction "C_C") (pintype "passive"))
      (node (ref "D27") (pin "C") (pinfunction "C_C") (pintype "passive"))
      (node (ref "D28") (pin "C") (pinfunction "C_C") (pintype "passive"))
      (node (ref "D29") (pin "C") (pinfunction "C_C") (pintype "passive"))
      (node (ref "D30") (pin "C") (pinfunction "C_C") (pintype "passive"))
      (node (ref "D44") (pin "A") (pinfunction "A_A") (pintype "passive"))
      (node (ref "D5") (pin "C") (pinfunction "C_C") (pintype "passive"))
      (node (ref "D53") (pin "C") (pinfunction "C_C") (pintype "passive"))
      (node (ref "D57") (pin "C") (pinfunction "C_C") (pintype "passive"))
      (node (ref "D60") (pin "C") (pinfunction "C_C") (pintype "passive"))
      (node (ref "D63") (pin "C") (pinfunction "C_C") (pintype "passive"))
      (node (ref "D66") (pin "C") (pinfunction "C_C") (pintype "passive"))
      (node (ref "D69") (pin "C") (pinfunction "C_C") (pintype "passive"))
      (node (ref "D72") (pin "C") (pinfunction "C_C") (pintype "passive"))
      (node (ref "D75") (pin "C") (pinfunction "C_C") (pintype "passive"))
      (node (ref "D8") (pin "C") (pinfunction "C_C") (pintype "passive"))
    )
    (net (code "4") (name "-1.5V") (class "Default")
      (node (ref "C14") (pin "1") (pinfunction "1_1") (pintype "passive"))
      (node (ref "D49") (pin "C") (pinfunction "C_C") (pintype "passive"))
      (node (ref "D50") (pin "A") (pinfunction "A_A") (pintype "passive"))
      (node (ref "Q10B") (pin "2") (pinfunction "B_2") (pintype "passive"))
      (node (ref "Q11B") (pin "2") (pinfunction "B_2") (pintype "passive"))
      (node (ref "Q12B") (pin "2") (pinfunction "B_2") (pintype "passive"))
      (node (ref "Q1B") (pin "2") (pinfunction "B_2") (pintype "passive"))
      (node (ref "Q26") (pin "2") (pinfunction "B_2") (pintype "passive"))
      (node (ref "Q27") (pin "2") (pinfunction "B_2") (pintype "passive"))
      (node (ref "Q28") (pin "2") (pinfunction "B_2") (pintype "passive"))
      (node (ref "Q29") (pin "2") (pinfunction "B_2") (pintype "passive"))
      (node (ref "Q2B") (pin "2") (pinfunction "B_2") (pintype "passive"))
      (node (ref "Q30") (pin "2") (pinfunction "B_2") (pintype "passive"))
      (node (ref "Q31") (pin "2") (pinfunction "B_2") (pintype "passive"))
      (node (ref "Q32") (pin "2") (pinfunction "B_2") (pintype "passive"))
      (node (ref "Q33") (pin "2") (pinfunction "B_2") (pintype "passive"))
      (node (ref "Q34") (pin "2") (pinfunction "B_2") (pintype "passive"))
      (node (ref "Q35") (pin "2") (pinfunction "B_2") (pintype "passive"))
      (node (ref "Q36") (pin "2") (pinfunction "B_2") (pintype "passive"))
      (node (ref "Q37") (pin "2") (pinfunction "B_2") (pintype "passive"))
      (node (ref "Q3B") (pin "2") (pinfunction "B_2") (pintype "passive"))
      (node (ref "Q4B") (pin "2") (pinfunction "B_2") (pintype "passive"))
      (node (ref "Q5B") (pin "2") (pinfunction "B_2") (pintype "passive"))
      (node (ref "Q6B") (pin "2") (pinfunction "B_2") (pintype "passive"))
      (node (ref "Q7B") (pin "2") (pinfunction "B_2") (pintype "passive"))
      (node (ref "Q8B") (pin "2") (pinfunction "B_2") (pintype "passive"))
      (node (ref "Q9B") (pin "2") (pinfunction "B_2") (pintype "passive"))
    )
    (net (code "5") (name "-3V") (class "Default")
      (node (ref "C13") (pin "1") (pinfunction "1_1") (pintype "passive"))
      (node (ref "D102") (pin "A") (pinfunction "A_A") (pintype "passive"))
      (node (ref "D108") (pin "A") (pinfunction "A_A") (pintype "passive"))
      (node (ref "D114") (pin "A") (pinfunction "A_A") (pintype "passive"))
      (node (ref "D116") (pin "A") (pinfunction "A_A") (pintype "passive"))
      (node (ref "D118") (pin "A") (pinfunction "A_A") (pintype "passive"))
      (node (ref "D12") (pin "A") (pinfunction "A_A") (pintype "passive"))
      (node (ref "D120") (pin "A") (pinfunction "A_A") (pintype "passive"))
      (node (ref "D122") (pin "A") (pinfunction "A_A") (pintype "passive"))
      (node (ref "D124") (pin "A") (pinfunction "A_A") (pintype "passive"))
      (node (ref "D126") (pin "A") (pinfunction "A_A") (pintype "passive"))
      (node (ref "D128") (pin "A") (pinfunction "A_A") (pintype "passive"))
      (node (ref "D130") (pin "A") (pinfunction "A_A") (pintype "passive"))
      (node (ref "D132") (pin "A") (pinfunction "A_A") (pintype "passive"))
      (node (ref "D134") (pin "A") (pinfunction "A_A") (pintype "passive"))
      (node (ref "D136") (pin "A") (pinfunction "A_A") (pintype "passive"))
      (node (ref "D138") (pin "A") (pinfunction "A_A") (pintype "passive"))
      (node (ref "D139") (pin "A") (pinfunction "A_A") (pintype "passive"))
      (node (ref "D140") (pin "A") (pinfunction "A_A") (pintype "passive"))
      (node (ref "D141") (pin "A") (pinfunction "A_A") (pintype "passive"))
      (node (ref "D142") (pin "A") (pinfunction "A_A") (pintype "passive"))
      (node (ref "D143") (pin "A") (pinfunction "A_A") (pintype "passive"))
      (node (ref "D144") (pin "A") (pinfunction "A_A") (pintype "passive"))
      (node (ref "D145") (pin "A") (pinfunction "A_A") (pintype "passive"))
      (node (ref "D146") (pin "A") (pinfunction "A_A") (pintype "passive"))
      (node (ref "D147") (pin "A") (pinfunction "A_A") (pintype "passive"))
      (node (ref "D148") (pin "A") (pinfunction "A_A") (pintype "passive"))
      (node (ref "D149") (pin "A") (pinfunction "A_A") (pintype "passive"))
      (node (ref "D150") (pin "A") (pinfunction "A_A") (pintype "passive"))
      (node (ref "D151") (pin "A") (pinfunction "A_A") (pintype "passive"))
      (node (ref "D152") (pin "A") (pinfunction "A_A") (pintype "passive"))
      (node (ref "D3") (pin "A") (pinfunction "A_A") (pintype "passive"))
      (node (ref "D39") (pin "A") (pinfunction "A_A") (pintype "passive"))
      (node (ref "D51") (pin "C") (pinfunction "C_C") (pintype "passive"))
      (node (ref "D52") (pin "A") (pinfunction "A_A") (pintype "passive"))
      (node (ref "D54") (pin "A") (pinfunction "A_A") (pintype "passive"))
      (node (ref "D58") (pin "A") (pinfunction "A_A") (pintype "passive"))
      (node (ref "D6") (pin "A") (pinfunction "A_A") (pintype "passive"))
      (node (ref "D61") (pin "A") (pinfunction "A_A") (pintype "passive"))
      (node (ref "D64") (pin "A") (pinfunction "A_A") (pintype "passive"))
      (node (ref "D67") (pin "A") (pinfunction "A_A") (pintype "passive"))
      (node (ref "D70") (pin "A") (pinfunction "A_A") (pintype "passive"))
      (node (ref "D73") (pin "A") (pinfunction "A_A") (pintype "passive"))
      (node (ref "D76") (pin "A") (pinfunction "A_A") (pintype "passive"))
      (node (ref "D78") (pin "A") (pinfunction "A_A") (pintype "passive"))
      (node (ref "D84") (pin "A") (pinfunction "A_A") (pintype "passive"))
      (node (ref "D9") (pin "A") (pinfunction "A_A") (pintype "passive"))
      (node (ref "D90") (pin "A") (pinfunction "A_A") (pintype "passive"))
      (node (ref "D96") (pin "A") (pinfunction "A_A") (pintype "passive"))
    )
    (net (code "6") (name "-15V") (class "Default")
      (node (ref "R129") (pin "1") (pinfunction "1_1") (pintype "passive"))
      (node (ref "R131") (pin "2") (pinfunction "2_2") (pintype "passive"))
      (node (ref "R133") (pin "2") (pinfunction "2_2") (pintype "passive"))
      (node (ref "R135") (pin "2") (pinfunction "2_2") (pintype "passive"))
      (node (ref "R137") (pin "2") (pinfunction "2_2") (pintype "passive"))
      (node (ref "R139") (pin "2") (pinfunction "2_2") (pintype "passive"))
      (node (ref "R141") (pin "2") (pinfunction "2_2") (pintype "passive"))
      (node (ref "R143") (pin "2") (pinfunction "2_2") (pintype "passive"))
      (node (ref "R145") (pin "2") (pinfunction "2_2") (pintype "passive"))
      (node (ref "R147") (pin "2") (pinfunction "2_2") (pintype "passive"))
      (node (ref "R149") (pin "2") (pinfunction "2_2") (pintype "passive"))
      (node (ref "R151") (pin "2") (pinfunction "2_2") (pintype "passive"))
      (node (ref "R153") (pin "2") (pinfunction "2_2") (pintype "passive"))
      (node (ref "R156") (pin "2") (pinfunction "2_2") (pintype "passive"))
      (node (ref "R158") (pin "2") (pinfunction "2_2") (pintype "passive"))
      (node (ref "R160") (pin "2") (pinfunction "2_2") (pintype "passive"))
      (node (ref "R70") (pin "2") (pinfunction "2_2") (pintype "passive"))
      (node (ref "R77") (pin "1") (pinfunction "1_1") (pintype "passive"))
      (node (ref "U$3") (pin "AB2") (pinfunction "1_AB2") (pintype "bidirectional"))
      (node (ref "U$3") (pin "BB2") (pinfunction "1_BB2") (pintype "bidirectional"))
      (node (ref "U$3") (pin "CB2") (pinfunction "1_CB2") (pintype "bidirectional"))
    )
    (net (code "7") (name "BAC00") (class "Default")
      (node (ref "D1") (pin "A") (pinfunction "A_A") (pintype "passive"))
      (node (ref "E1") (pin "6") (pinfunction "O_6") (pintype "open_collector"))
      (node (ref "R13") (pin "1") (pinfunction "1_1") (pintype "passive"))
      (node (ref "U$3") (pin "AB1") (pinfunction "1_AB1") (pintype "bidirectional"))
    )
    (net (code "8") (name "BAC01") (class "Default")
      (node (ref "D2") (pin "A") (pinfunction "A_A") (pintype "passive"))
      (node (ref "E1") (pin "4") (pinfunction "O_4") (pintype "open_collector"))
      (node (ref "R2") (pin "1") (pinfunction "1_1") (pintype "passive"))
      (node (ref "U$3") (pin "AD1") (pinfunction "1_AD1") (pintype "bidirectional"))
    )
    (net (code "9") (name "BAC02") (class "Default")
      (node (ref "D5") (pin "A") (pinfunction "A_A") (pintype "passive"))
      (node (ref "E1") (pin "2") (pinfunction "O_2") (pintype "open_collector"))
      (node (ref "R6") (pin "1") (pinfunction "1_1") (pintype "passive"))
      (node (ref "U$3") (pin "AE1") (pinfunction "1_AE1") (pintype "bidirectional"))
    )
    (net (code "10") (name "BAC03") (class "Default")
      (node (ref "D8") (pin "A") (pinfunction "A_A") (pintype "passive"))
      (node (ref "E2") (pin "6") (pinfunction "O_6") (pintype "open_collector"))
      (node (ref "R9") (pin "1") (pinfunction "1_1") (pintype "passive"))
      (node (ref "U$3") (pin "AH1") (pinfunction "1_AH1") (pintype "bidirectional"))
    )
    (net (code "11") (name "BAC04") (class "Default")
      (node (ref "D11") (pin "A") (pinfunction "A_A") (pintype "passive"))
      (node (ref "E2") (pin "4") (pinfunction "O_4") (pintype "open_collector"))
      (node (ref "R12") (pin "1") (pinfunction "1_1") (pintype "passive"))
      (node (ref "U$3") (pin "AJ1") (pinfunction "1_AJ1") (pintype "bidirectional"))
    )
    (net (code "12") (name "BAC05") (class "Default")
      (node (ref "D57") (pin "A") (pinfunction "A_A") (pintype "passive"))
      (node (ref "E2") (pin "2") (pinfunction "O_2") (pintype "open_collector"))
      (node (ref "R16") (pin "1") (pinfunction "1_1") (pintype "passive"))
      (node (ref "U$3") (pin "AL1") (pinfunction "1_AL1") (pintype "bidirectional"))
    )
    (net (code "13") (name "BAC06") (class "Default")
      (node (ref "D60") (pin "A") (pinfunction "A_A") (pintype "passive"))
      (node (ref "E2") (pin "12") (pinfunction "O_12") (pintype "open_collector"))
      (node (ref "R19") (pin "1") (pinfunction "1_1") (pintype "passive"))
      (node (ref "U$3") (pin "AM1") (pinfunction "1_AM1") (pintype "bidirectional"))
    )
    (net (code "14") (name "BAC07") (class "Default")
      (node (ref "D63") (pin "A") (pinfunction "A_A") (pintype "passive"))
      (node (ref "E2") (pin "10") (pinfunction "O_10") (pintype "open_collector"))
      (node (ref "R22") (pin "1") (pinfunction "1_1") (pintype "passive"))
      (node (ref "U$3") (pin "AP1") (pinfunction "1_AP1") (pintype "bidirectional"))
    )
    (net (code "15") (name "BAC08") (class "Default")
      (node (ref "D66") (pin "A") (pinfunction "A_A") (pintype "passive"))
      (node (ref "E2") (pin "8") (pinfunction "O_8") (pintype "open_collector"))
      (node (ref "R62") (pin "1") (pinfunction "1_1") (pintype "passive"))
      (node (ref "U$3") (pin "AS1") (pinfunction "1_AS1") (pintype "bidirectional"))
    )
    (net (code "16") (name "BAC09") (class "Default")
      (node (ref "D69") (pin "A") (pinfunction "A_A") (pintype "passive"))
      (node (ref "E1") (pin "8") (pinfunction "O_8") (pintype "open_collector"))
      (node (ref "R67") (pin "1") (pinfunction "1_1") (pintype "passive"))
      (node (ref "U$3") (pin "AD2") (pinfunction "1_AD2") (pintype "bidirectional"))
    )
    (net (code "17") (name "BAC10") (class "Default")
      (node (ref "D72") (pin "A") (pinfunction "A_A") (pintype "passive"))
      (node (ref "E1") (pin "10") (pinfunction "O_10") (pintype "open_collector"))
      (node (ref "R73") (pin "1") (pinfunction "1_1") (pintype "passive"))
      (node (ref "U$3") (pin "AE2") (pinfunction "1_AE2") (pintype "bidirectional"))
    )
    (net (code "18") (name "BAC11") (class "Default")
      (node (ref "D75") (pin "A") (pinfunction "A_A") (pintype "passive"))
      (node (ref "E1") (pin "12") (pinfunction "O_12") (pintype "open_collector"))
      (node (ref "R78") (pin "1") (pinfunction "1_1") (pintype "passive"))
      (node (ref "U$3") (pin "AH2") (pinfunction "1_AH2") (pintype "bidirectional"))
    )
    (net (code "19") (name "BMB00") (class "Default")
      (node (ref "D13") (pin "A") (pinfunction "A_A") (pintype "passive"))
      (node (ref "E13") (pin "6") (pinfunction "O_6") (pintype "open_collector"))
      (node (ref "R25") (pin "1") (pinfunction "1_1") (pintype "passive"))
      (node (ref "U$3") (pin "BB1") (pinfunction "1_BB1") (pintype "bidirectional"))
    )
    (net (code "20") (name "BMB01") (class "Default")
      (node (ref "D14") (pin "A") (pinfunction "A_A") (pintype "passive"))
      (node (ref "E13") (pin "4") (pinfunction "O_4") (pintype "open_collector"))
      (node (ref "R26") (pin "1") (pinfunction "1_1") (pintype "passive"))
      (node (ref "U$3") (pin "BD1") (pinfunction "1_BD1") (pintype "bidirectional"))
    )
    (net (code "21") (name "BMB02") (class "Default")
      (node (ref "D15") (pin "A") (pinfunction "A_A") (pintype "passive"))
      (node (ref "E13") (pin "2") (pinfunction "O_2") (pintype "open_collector"))
      (node (ref "R27") (pin "1") (pinfunction "1_1") (pintype "passive"))
      (node (ref "U$3") (pin "BE1") (pinfunction "1_BE1") (pintype "bidirectional"))
    )
    (net (code "22") (name "BMB03") (class "Default")
      (node (ref "D17") (pin "A") (pinfunction "A_A") (pintype "passive"))
      (node (ref "E18") (pin "2") (pinfunction "O_2") (pintype "open_collector"))
      (node (ref "E18") (pin "4") (pinfunction "O_4") (pintype "open_collector"))
      (node (ref "R29") (pin "1") (pinfunction "1_1") (pintype "passive"))
      (node (ref "U$3") (pin "BJ1") (pinfunction "1_BJ1") (pintype "bidirectional"))
    )
    (net (code "23") (name "BMB04") (class "Default")
      (node (ref "D19") (pin "A") (pinfunction "A_A") (pintype "passive"))
      (node (ref "E18") (pin "10") (pinfunction "O_10") (pintype "open_collector"))
      (node (ref "E18") (pin "12") (pinfunction "O_12") (pintype "open_collector"))
      (node (ref "R31") (pin "1") (pinfunction "1_1") (pintype "passive"))
      (node (ref "U$3") (pin "BM1") (pinfunction "1_BM1") (pintype "bidirectional"))
    )
    (net (code "24") (name "BMB05") (class "Default")
      (node (ref "D21") (pin "A") (pinfunction "A_A") (pintype "passive"))
      (node (ref "E22") (pin "2") (pinfunction "O_2") (pintype "open_collector"))
      (node (ref "E22") (pin "4") (pinfunction "O_4") (pintype "open_collector"))
      (node (ref "R33") (pin "1") (pinfunction "1_1") (pintype "passive"))
      (node (ref "U$3") (pin "BS1") (pinfunction "1_BS1") (pintype "bidirectional"))
    )
    (net (code "25") (name "BMB06") (class "Default")
      (node (ref "D23") (pin "A") (pinfunction "A_A") (pintype "passive"))
      (node (ref "E13") (pin "10") (pinfunction "O_10") (pintype "open_collector"))
      (node (ref "E13") (pin "8") (pinfunction "O_8") (pintype "open_collector"))
      (node (ref "R35") (pin "1") (pinfunction "1_1") (pintype "passive"))
      (node (ref "U$3") (pin "BE2") (pinfunction "1_BE2") (pintype "bidirectional"))
    )
    (net (code "26") (name "BMB07") (class "Default")
      (node (ref "D25") (pin "A") (pinfunction "A_A") (pintype "passive"))
      (node (ref "E18") (pin "6") (pinfunction "O_6") (pintype "open_collector"))
      (node (ref "E18") (pin "8") (pinfunction "O_8") (pintype "open_collector"))
      (node (ref "R37") (pin "1") (pinfunction "1_1") (pintype "passive"))
      (node (ref "U$3") (pin "BK2") (pinfunction "1_BK2") (pintype "bidirectional"))
    )
    (net (code "27") (name "BMB08") (class "Default")
      (node (ref "D27") (pin "A") (pinfunction "A_A") (pintype "passive"))
      (node (ref "E13") (pin "12") (pinfunction "O_12") (pintype "open_collector"))
      (node (ref "E22") (pin "6") (pinfunction "O_6") (pintype "open_collector"))
      (node (ref "R39") (pin "1") (pinfunction "1_1") (pintype "passive"))
      (node (ref "U$3") (pin "BP2") (pinfunction "1_BP2") (pintype "bidirectional"))
    )
    (net (code "28") (name "BMB09") (class "Default")
      (node (ref "D28") (pin "A") (pinfunction "A_A") (pintype "passive"))
      (node (ref "E22") (pin "12") (pinfunction "O_12") (pintype "open_collector"))
      (node (ref "R40") (pin "1") (pinfunction "1_1") (pintype "passive"))
      (node (ref "U$3") (pin "BS2") (pinfunction "1_BS2") (pintype "bidirectional"))
    )
    (net (code "29") (name "BMB10") (class "Default")
      (node (ref "D29") (pin "A") (pinfunction "A_A") (pintype "passive"))
      (node (ref "E22") (pin "10") (pinfunction "O_10") (pintype "open_collector"))
      (node (ref "R42") (pin "1") (pinfunction "1_1") (pintype "passive"))
      (node (ref "U$3") (pin "BT2") (pinfunction "1_BT2") (pintype "bidirectional"))
    )
    (net (code "30") (name "BMB11") (class "Default")
      (node (ref "D30") (pin "A") (pinfunction "A_A") (pintype "passive"))
      (node (ref "E22") (pin "8") (pinfunction "O_8") (pintype "open_collector"))
      (node (ref "R43") (pin "1") (pinfunction "1_1") (pintype "passive"))
      (node (ref "U$3") (pin "BV2") (pinfunction "1_BV2") (pintype "bidirectional"))
    )
    (net (code "31") (name "GND") (class "Default")
      (node (ref "C1") (pin "2") (pinfunction "2_2") (pintype "passive"))
      (node (ref "C10") (pin "2") (pinfunction "2_2") (pintype "passive"))
      (node (ref "C11") (pin "2") (pinfunction "2_2") (pintype "passive"))
      (node (ref "C12") (pin "2") (pinfunction "2_2") (pintype "passive"))
      (node (ref "C13") (pin "2") (pinfunction "2_2") (pintype "passive"))
      (node (ref "C14") (pin "2") (pinfunction "2_2") (pintype "passive"))
      (node (ref "C15") (pin "2") (pinfunction "2_2") (pintype "passive"))
      (node (ref "C16") (pin "2") (pinfunction "2_2") (pintype "passive"))
      (node (ref "C2") (pin "2") (pinfunction "2_2") (pintype "passive"))
      (node (ref "C20") (pin "-") (pinfunction "-_-") (pintype "passive"))
      (node (ref "C21") (pin "-") (pinfunction "-_-") (pintype "passive"))
      (node (ref "C22") (pin "-") (pinfunction "-_-") (pintype "passive"))
      (node (ref "C23") (pin "2") (pinfunction "2_2") (pintype "passive"))
      (node (ref "C24") (pin "2") (pinfunction "2_2") (pintype "passive"))
      (node (ref "C25") (pin "2") (pinfunction "2_2") (pintype "passive"))
      (node (ref "C3") (pin "2") (pinfunction "2_2") (pintype "passive"))
      (node (ref "C4") (pin "2") (pinfunction "2_2") (pintype "passive"))
      (node (ref "C5") (pin "2") (pinfunction "2_2") (pintype "passive"))
      (node (ref "C6") (pin "2") (pinfunction "2_2") (pintype "passive"))
      (node (ref "C7") (pin "2") (pinfunction "2_2") (pintype "passive"))
      (node (ref "C8") (pin "2") (pinfunction "2_2") (pintype "passive"))
      (node (ref "C9") (pin "2") (pinfunction "2_2") (pintype "passive"))
      (node (ref "D10") (pin "C") (pinfunction "C_C") (pintype "passive"))
      (node (ref "D103") (pin "C") (pinfunction "C_C") (pintype "passive"))
      (node (ref "D109") (pin "C") (pinfunction "C_C") (pintype "passive"))
      (node (ref "D115") (pin "C") (pinfunction "C_C") (pintype "passive"))
      (node (ref "D117") (pin "C") (pinfunction "C_C") (pintype "passive"))
      (node (ref "D119") (pin "C") (pinfunction "C_C") (pintype "passive"))
      (node (ref "D121") (pin "C") (pinfunction "C_C") (pintype "passive"))
      (node (ref "D123") (pin "C") (pinfunction "C_C") (pintype "passive"))
      (node (ref "D125") (pin "C") (pinfunction "C_C") (pintype "passive"))
      (node (ref "D127") (pin "C") (pinfunction "C_C") (pintype "passive"))
      (node (ref "D129") (pin "C") (pinfunction "C_C") (pintype "passive"))
      (node (ref "D131") (pin "C") (pinfunction "C_C") (pintype "passive"))
      (node (ref "D133") (pin "C") (pinfunction "C_C") (pintype "passive"))
      (node (ref "D135") (pin "C") (pinfunction "C_C") (pintype "passive"))
      (node (ref "D137") (pin "C") (pinfunction "C_C") (pintype "passive"))
      (node (ref "D154") (pin "A") (pinfunction "A_A") (pintype "passive"))
      (node (ref "D156") (pin "A") (pinfunction "A_A") (pintype "passive"))
      (node (ref "D158") (pin "A") (pinfunction "A_A") (pintype "passive"))
      (node (ref "D160") (pin "A") (pinfunction "A_A") (pintype "passive"))
      (node (ref "D162") (pin "A") (pinfunction "A_A") (pintype "passive"))
      (node (ref "D164") (pin "A") (pinfunction "A_A") (pintype "passive"))
      (node (ref "D166") (pin "A") (pinfunction "A_A") (pintype "passive"))
      (node (ref "D168") (pin "A") (pinfunction "A_A") (pintype "passive"))
      (node (ref "D170") (pin "A") (pinfunction "A_A") (pintype "passive"))
      (node (ref "D172") (pin "A") (pinfunction "A_A") (pintype "passive"))
      (node (ref "D174") (pin "A") (pinfunction "A_A") (pintype "passive"))
      (node (ref "D176") (pin "A") (pinfunction "A_A") (pintype "passive"))
      (node (ref "D178") (pin "A") (pinfunction "A_A") (pintype "passive"))
      (node (ref "D180") (pin "A") (pinfunction "A_A") (pintype "passive"))
      (node (ref "D182") (pin "A") (pinfunction "A_A") (pintype "passive"))
      (node (ref "D184") (pin "A") (pinfunction "A_A") (pintype "passive"))
      (node (ref "D4") (pin "C") (pinfunction "C_C") (pintype "passive"))
      (node (ref "D47") (pin "C") (pinfunction "C_C") (pintype "passive"))
      (node (ref "D48") (pin "A") (pinfunction "A_A") (pintype "passive"))
      (node (ref "D55") (pin "C") (pinfunction "C_C") (pintype "passive"))
      (node (ref "D56") (pin "C") (pinfunction "C_C") (pintype "passive"))
      (node (ref "D59") (pin "C") (pinfunction "C_C") (pintype "passive"))
      (node (ref "D62") (pin "C") (pinfunction "C_C") (pintype "passive"))
      (node (ref "D65") (pin "C") (pinfunction "C_C") (pintype "passive"))
      (node (ref "D68") (pin "C") (pinfunction "C_C") (pintype "passive"))
      (node (ref "D7") (pin "C") (pinfunction "C_C") (pintype "passive"))
      (node (ref "D71") (pin "C") (pinfunction "C_C") (pintype "passive"))
      (node (ref "D74") (pin "C") (pinfunction "C_C") (pintype "passive"))
      (node (ref "D77") (pin "C") (pinfunction "C_C") (pintype "passive"))
      (node (ref "D79") (pin "C") (pinfunction "C_C") (pintype "passive"))
      (node (ref "D85") (pin "C") (pinfunction "C_C") (pintype "passive"))
      (node (ref "D91") (pin "C") (pinfunction "C_C") (pintype "passive"))
      (node (ref "D97") (pin "C") (pinfunction "C_C") (pintype "passive"))
      (node (ref "NACI00") (pin "1") (pinfunction "1_1") (pintype "passive"))
      (node (ref "NACI00") (pin "10") (pinfunction "10_10") (pintype "passive"))
      (node (ref "NACI00") (pin "11") (pinfunction "11_11") (pintype "passive"))
      (node (ref "NACI00") (pin "13") (pinfunction "13_13") (pintype "passive"))
      (node (ref "NACI00") (pin "14") (pinfunction "14_14") (pintype "passive"))
      (node (ref "NACI00") (pin "15") (pinfunction "15_15") (pintype "passive"))
      (node (ref "NACI00") (pin "17") (pinfunction "17_17") (pintype "passive"))
      (node (ref "NACI00") (pin "18") (pinfunction "18_18") (pintype "passive"))
      (node (ref "NACI00") (pin "19") (pinfunction "19_19") (pintype "passive"))
      (node (ref "NACI00") (pin "21") (pinfunction "21_21") (pintype "passive"))
      (node (ref "NACI00") (pin "22") (pinfunction "22_22") (pintype "passive"))
      (node (ref "NACI00") (pin "23") (pinfunction "23_23") (pintype "passive"))
      (node (ref "NACI00") (pin "25") (pinfunction "25_25") (pintype "passive"))
      (node (ref "NACI00") (pin "26") (pinfunction "26_26") (pintype "passive"))
      (node (ref "NACI00") (pin "27") (pinfunction "27_27") (pintype "passive"))
      (node (ref "NACI00") (pin "29") (pinfunction "29_29") (pintype "passive"))
      (node (ref "NACI00") (pin "3") (pinfunction "3_3") (pintype "passive"))
      (node (ref "NACI00") (pin "31") (pinfunction "31_31") (pintype "passive"))
      (node (ref "NACI00") (pin "32") (pinfunction "32_32") (pintype "passive"))
      (node (ref "NACI00") (pin "33") (pinfunction "33_33") (pintype "passive"))
      (node (ref "NACI00") (pin "5") (pinfunction "5_5") (pintype "passive"))
      (node (ref "NACI00") (pin "7") (pinfunction "7_7") (pintype "passive"))
      (node (ref "NACI00") (pin "9") (pinfunction "9_9") (pintype "passive"))
      (node (ref "NACI09") (pin "1") (pinfunction "1_1") (pintype "passive"))
      (node (ref "NACI09") (pin "10") (pinfunction "10_10") (pintype "passive"))
      (node (ref "NACI09") (pin "11") (pinfunction "11_11") (pintype "passive"))
      (node (ref "NACI09") (pin "13") (pinfunction "13_13") (pintype "passive"))
      (node (ref "NACI09") (pin "14") (pinfunction "14_14") (pintype "passive"))
      (node (ref "NACI09") (pin "15") (pinfunction "15_15") (pintype "passive"))
      (node (ref "NACI09") (pin "17") (pinfunction "17_17") (pintype "passive"))
      (node (ref "NACI09") (pin "18") (pinfunction "18_18") (pintype "passive"))
      (node (ref "NACI09") (pin "19") (pinfunction "19_19") (pintype "passive"))
      (node (ref "NACI09") (pin "21") (pinfunction "21_21") (pintype "passive"))
      (node (ref "NACI09") (pin "22") (pinfunction "22_22") (pintype "passive"))
      (node (ref "NACI09") (pin "23") (pinfunction "23_23") (pintype "passive"))
      (node (ref "NACI09") (pin "25") (pinfunction "25_25") (pintype "passive"))
      (node (ref "NACI09") (pin "26") (pinfunction "26_26") (pintype "passive"))
      (node (ref "NACI09") (pin "27") (pinfunction "27_27") (pintype "passive"))
      (node (ref "NACI09") (pin "29") (pinfunction "29_29") (pintype "passive"))
      (node (ref "NACI09") (pin "3") (pinfunction "3_3") (pintype "passive"))
      (node (ref "NACI09") (pin "31") (pinfunction "31_31") (pintype "passive"))
      (node (ref "NACI09") (pin "32") (pinfunction "32_32") (pintype "passive"))
      (node (ref "NACI09") (pin "33") (pinfunction "33_33") (pintype "passive"))
      (node (ref "NACI09") (pin "5") (pinfunction "5_5") (pintype "passive"))
      (node (ref "NACI09") (pin "7") (pinfunction "7_7") (pintype "passive"))
      (node (ref "NACI09") (pin "9") (pinfunction "9_9") (pintype "passive"))
      (node (ref "NBAC00") (pin "1") (pinfunction "1_1") (pintype "passive"))
      (node (ref "NBAC00") (pin "10") (pinfunction "10_10") (pintype "passive"))
      (node (ref "NBAC00") (pin "11") (pinfunction "11_11") (pintype "passive"))
      (node (ref "NBAC00") (pin "13") (pinfunction "13_13") (pintype "passive"))
      (node (ref "NBAC00") (pin "14") (pinfunction "14_14") (pintype "passive"))
      (node (ref "NBAC00") (pin "15") (pinfunction "15_15") (pintype "passive"))
      (node (ref "NBAC00") (pin "17") (pinfunction "17_17") (pintype "passive"))
      (node (ref "NBAC00") (pin "18") (pinfunction "18_18") (pintype "passive"))
      (node (ref "NBAC00") (pin "19") (pinfunction "19_19") (pintype "passive"))
      (node (ref "NBAC00") (pin "21") (pinfunction "21_21") (pintype "passive"))
      (node (ref "NBAC00") (pin "22") (pinfunction "22_22") (pintype "passive"))
      (node (ref "NBAC00") (pin "23") (pinfunction "23_23") (pintype "passive"))
      (node (ref "NBAC00") (pin "25") (pinfunction "25_25") (pintype "passive"))
      (node (ref "NBAC00") (pin "26") (pinfunction "26_26") (pintype "passive"))
      (node (ref "NBAC00") (pin "27") (pinfunction "27_27") (pintype "passive"))
      (node (ref "NBAC00") (pin "29") (pinfunction "29_29") (pintype "passive"))
      (node (ref "NBAC00") (pin "3") (pinfunction "3_3") (pintype "passive"))
      (node (ref "NBAC00") (pin "31") (pinfunction "31_31") (pintype "passive"))
      (node (ref "NBAC00") (pin "32") (pinfunction "32_32") (pintype "passive"))
      (node (ref "NBAC00") (pin "33") (pinfunction "33_33") (pintype "passive"))
      (node (ref "NBAC00") (pin "5") (pinfunction "5_5") (pintype "passive"))
      (node (ref "NBAC00") (pin "7") (pinfunction "7_7") (pintype "passive"))
      (node (ref "NBAC00") (pin "9") (pinfunction "9_9") (pintype "passive"))
      (node (ref "NBAC09") (pin "1") (pinfunction "1_1") (pintype "passive"))
      (node (ref "NBAC09") (pin "10") (pinfunction "10_10") (pintype "passive"))
      (node (ref "NBAC09") (pin "11") (pinfunction "11_11") (pintype "passive"))
      (node (ref "NBAC09") (pin "13") (pinfunction "13_13") (pintype "passive"))
      (node (ref "NBAC09") (pin "14") (pinfunction "14_14") (pintype "passive"))
      (node (ref "NBAC09") (pin "15") (pinfunction "15_15") (pintype "passive"))
      (node (ref "NBAC09") (pin "17") (pinfunction "17_17") (pintype "passive"))
      (node (ref "NBAC09") (pin "18") (pinfunction "18_18") (pintype "passive"))
      (node (ref "NBAC09") (pin "19") (pinfunction "19_19") (pintype "passive"))
      (node (ref "NBAC09") (pin "21") (pinfunction "21_21") (pintype "passive"))
      (node (ref "NBAC09") (pin "22") (pinfunction "22_22") (pintype "passive"))
      (node (ref "NBAC09") (pin "23") (pinfunction "23_23") (pintype "passive"))
      (node (ref "NBAC09") (pin "25") (pinfunction "25_25") (pintype "passive"))
      (node (ref "NBAC09") (pin "26") (pinfunction "26_26") (pintype "passive"))
      (node (ref "NBAC09") (pin "27") (pinfunction "27_27") (pintype "passive"))
      (node (ref "NBAC09") (pin "29") (pinfunction "29_29") (pintype "passive"))
      (node (ref "NBAC09") (pin "3") (pinfunction "3_3") (pintype "passive"))
      (node (ref "NBAC09") (pin "31") (pinfunction "31_31") (pintype "passive"))
      (node (ref "NBAC09") (pin "32") (pinfunction "32_32") (pintype "passive"))
      (node (ref "NBAC09") (pin "33") (pinfunction "33_33") (pintype "passive"))
      (node (ref "NBAC09") (pin "5") (pinfunction "5_5") (pintype "passive"))
      (node (ref "NBAC09") (pin "7") (pinfunction "7_7") (pintype "passive"))
      (node (ref "NBAC09") (pin "9") (pinfunction "9_9") (pintype "passive"))
      (node (ref "NBMB00") (pin "1") (pinfunction "1_1") (pintype "passive"))
      (node (ref "NBMB00") (pin "10") (pinfunction "10_10") (pintype "passive"))
      (node (ref "NBMB00") (pin "11") (pinfunction "11_11") (pintype "passive"))
      (node (ref "NBMB00") (pin "13") (pinfunction "13_13") (pintype "passive"))
      (node (ref "NBMB00") (pin "14") (pinfunction "14_14") (pintype "passive"))
      (node (ref "NBMB00") (pin "15") (pinfunction "15_15") (pintype "passive"))
      (node (ref "NBMB00") (pin "17") (pinfunction "17_17") (pintype "passive"))
      (node (ref "NBMB00") (pin "18") (pinfunction "18_18") (pintype "passive"))
      (node (ref "NBMB00") (pin "19") (pinfunction "19_19") (pintype "passive"))
      (node (ref "NBMB00") (pin "21") (pinfunction "21_21") (pintype "passive"))
      (node (ref "NBMB00") (pin "22") (pinfunction "22_22") (pintype "passive"))
      (node (ref "NBMB00") (pin "23") (pinfunction "23_23") (pintype "passive"))
      (node (ref "NBMB00") (pin "25") (pinfunction "25_25") (pintype "passive"))
      (node (ref "NBMB00") (pin "26") (pinfunction "26_26") (pintype "passive"))
      (node (ref "NBMB00") (pin "27") (pinfunction "27_27") (pintype "passive"))
      (node (ref "NBMB00") (pin "29") (pinfunction "29_29") (pintype "passive"))
      (node (ref "NBMB00") (pin "3") (pinfunction "3_3") (pintype "passive"))
      (node (ref "NBMB00") (pin "31") (pinfunction "31_31") (pintype "passive"))
      (node (ref "NBMB00") (pin "32") (pinfunction "32_32") (pintype "passive"))
      (node (ref "NBMB00") (pin "33") (pinfunction "33_33") (pintype "passive"))
      (node (ref "NBMB00") (pin "5") (pinfunction "5_5") (pintype "passive"))
      (node (ref "NBMB00") (pin "7") (pinfunction "7_7") (pintype "passive"))
      (node (ref "NBMB00") (pin "9") (pinfunction "9_9") (pintype "passive"))
      (node (ref "NBMB06") (pin "1") (pinfunction "1_1") (pintype "passive"))
      (node (ref "NBMB06") (pin "10") (pinfunction "10_10") (pintype "passive"))
      (node (ref "NBMB06") (pin "11") (pinfunction "11_11") (pintype "passive"))
      (node (ref "NBMB06") (pin "13") (pinfunction "13_13") (pintype "passive"))
      (node (ref "NBMB06") (pin "14") (pinfunction "14_14") (pintype "passive"))
      (node (ref "NBMB06") (pin "15") (pinfunction "15_15") (pintype "passive"))
      (node (ref "NBMB06") (pin "17") (pinfunction "17_17") (pintype "passive"))
      (node (ref "NBMB06") (pin "18") (pinfunction "18_18") (pintype "passive"))
      (node (ref "NBMB06") (pin "19") (pinfunction "19_19") (pintype "passive"))
      (node (ref "NBMB06") (pin "21") (pinfunction "21_21") (pintype "passive"))
      (node (ref "NBMB06") (pin "22") (pinfunction "22_22") (pintype "passive"))
      (node (ref "NBMB06") (pin "23") (pinfunction "23_23") (pintype "passive"))
      (node (ref "NBMB06") (pin "25") (pinfunction "25_25") (pintype "passive"))
      (node (ref "NBMB06") (pin "26") (pinfunction "26_26") (pintype "passive"))
      (node (ref "NBMB06") (pin "27") (pinfunction "27_27") (pintype "passive"))
      (node (ref "NBMB06") (pin "29") (pinfunction "29_29") (pintype "passive"))
      (node (ref "NBMB06") (pin "3") (pinfunction "3_3") (pintype "passive"))
      (node (ref "NBMB06") (pin "31") (pinfunction "31_31") (pintype "passive"))
      (node (ref "NBMB06") (pin "32") (pinfunction "32_32") (pintype "passive"))
      (node (ref "NBMB06") (pin "33") (pinfunction "33_33") (pintype "passive"))
      (node (ref "NBMB06") (pin "5") (pinfunction "5_5") (pintype "passive"))
      (node (ref "NBMB06") (pin "7") (pinfunction "7_7") (pintype "passive"))
      (node (ref "NBMB06") (pin "9") (pinfunction "9_9") (pintype "passive"))
      (node (ref "Q10A") (pin "1") (pinfunction "E_1") (pintype "passive"))
      (node (ref "Q11A") (pin "1") (pinfunction "E_1") (pintype "passive"))
      (node (ref "Q12A") (pin "1") (pinfunction "E_1") (pintype "passive"))
      (node (ref "Q13B") (pin "1") (pinfunction "E_1") (pintype "passive"))
      (node (ref "Q14B") (pin "1") (pinfunction "E_1") (pintype "passive"))
      (node (ref "Q15B") (pin "1") (pinfunction "E_1") (pintype "passive"))
      (node (ref "Q16B") (pin "1") (pinfunction "E_1") (pintype "passive"))
      (node (ref "Q17B") (pin "1") (pinfunction "E_1") (pintype "passive"))
      (node (ref "Q18B") (pin "1") (pinfunction "E_1") (pintype "passive"))
      (node (ref "Q1A") (pin "1") (pinfunction "E_1") (pintype "passive"))
      (node (ref "Q2A") (pin "1") (pinfunction "E_1") (pintype "passive"))
      (node (ref "Q3A") (pin "1") (pinfunction "E_1") (pintype "passive"))
      (node (ref "Q4A") (pin "1") (pinfunction "E_1") (pintype "passive"))
      (node (ref "Q50") (pin "1") (pinfunction "E_1") (pintype "passive"))
      (node (ref "Q51") (pin "1") (pinfunction "E_1") (pintype "passive"))
      (node (ref "Q52") (pin "1") (pinfunction "E_1") (pintype "passive"))
      (node (ref "Q5A") (pin "1") (pinfunction "E_1") (pintype "passive"))
      (node (ref "Q6A") (pin "1") (pinfunction "E_1") (pintype "passive"))
      (node (ref "Q7") (pin "1") (pinfunction "E_1") (pintype "passive"))
      (node (ref "Q7A") (pin "1") (pinfunction "E_1") (pintype "passive"))
      (node (ref "Q8A") (pin "1") (pinfunction "E_1") (pintype "passive"))
      (node (ref "Q9A") (pin "1") (pinfunction "E_1") (pintype "passive"))
      (node (ref "U$3") (pin "AA1") (pinfunction "1_AA1") (pintype "bidirectional"))
      (node (ref "U$3") (pin "AC1") (pinfunction "1_AC1") (pintype "bidirectional"))
      (node (ref "U$3") (pin "AC2") (pinfunction "1_AC2") (pintype "bidirectional"))
      (node (ref "U$3") (pin "AF1") (pinfunction "1_AF1") (pintype "bidirectional"))
      (node (ref "U$3") (pin "AF2") (pinfunction "1_AF2") (pintype "bidirectional"))
      (node (ref "U$3") (pin "AJ2") (pinfunction "1_AJ2") (pintype "bidirectional"))
      (node (ref "U$3") (pin "AK1") (pinfunction "1_AK1") (pintype "bidirectional"))
      (node (ref "U$3") (pin "AL2") (pinfunction "1_AL2") (pintype "bidirectional"))
      (node (ref "U$3") (pin "AN1") (pinfunction "1_AN1") (pintype "bidirectional"))
      (node (ref "U$3") (pin "AN2") (pinfunction "1_AN2") (pintype "bidirectional"))
      (node (ref "U$3") (pin "AR1") (pinfunction "1_AR1") (pintype "bidirectional"))
      (node (ref "U$3") (pin "AR2") (pinfunction "1_AR2") (pintype "bidirectional"))
      (node (ref "U$3") (pin "AT1") (pinfunction "1_AT1") (pintype "bidirectional"))
      (node (ref "U$3") (pin "AU1") (pinfunction "1_AU1") (pintype "bidirectional"))
      (node (ref "U$3") (pin "AU2") (pinfunction "1_AU2") (pintype "bidirectional"))
      (node (ref "U$3") (pin "AV1") (pinfunction "1_AV1") (pintype "bidirectional"))
      (node (ref "U$3") (pin "BA1") (pinfunction "1_BA1") (pintype "bidirectional"))
      (node (ref "U$3") (pin "BC1") (pinfunction "1_BC1") (pintype "bidirectional"))
      (node (ref "U$3") (pin "BC2") (pinfunction "1_BC2") (pintype "bidirectional"))
      (node (ref "U$3") (pin "BF1") (pinfunction "1_BF1") (pintype "bidirectional"))
      (node (ref "U$3") (pin "BF2") (pinfunction "1_BF2") (pintype "bidirectional"))
      (node (ref "U$3") (pin "BJ2") (pinfunction "1_BJ2") (pintype "bidirectional"))
      (node (ref "U$3") (pin "BK1") (pinfunction "1_BK1") (pintype "bidirectional"))
      (node (ref "U$3") (pin "BL2") (pinfunction "1_BL2") (pintype "bidirectional"))
      (node (ref "U$3") (pin "BN1") (pinfunction "1_BN1") (pintype "bidirectional"))
      (node (ref "U$3") (pin "BN2") (pinfunction "1_BN2") (pintype "bidirectional"))
      (node (ref "U$3") (pin "BR1") (pinfunction "1_BR1") (pintype "bidirectional"))
      (node (ref "U$3") (pin "BR2") (pinfunction "1_BR2") (pintype "bidirectional"))
      (node (ref "U$3") (pin "BT1") (pinfunction "1_BT1") (pintype "bidirectional"))
      (node (ref "U$3") (pin "BU1") (pinfunction "1_BU1") (pintype "bidirectional"))
      (node (ref "U$3") (pin "BU2") (pinfunction "1_BU2") (pintype "bidirectional"))
      (node (ref "U$3") (pin "BV1") (pinfunction "1_BV1") (pintype "bidirectional"))
      (node (ref "U$3") (pin "CA1") (pinfunction "1_CA1") (pintype "bidirectional"))
      (node (ref "U$3") (pin "CC1") (pinfunction "1_CC1") (pintype "bidirectional"))
      (node (ref "U$3") (pin "CC2") (pinfunction "1_CC2") (pintype "bidirectional"))
      (node (ref "U$3") (pin "CF1") (pinfunction "1_CF1") (pintype "bidirectional"))
      (node (ref "U$3") (pin "CF2") (pinfunction "1_CF2") (pintype "bidirectional"))
      (node (ref "U$3") (pin "CJ2") (pinfunction "1_CJ2") (pintype "bidirectional"))
      (node (ref "U$3") (pin "CK1") (pinfunction "1_CK1") (pintype "bidirectional"))
      (node (ref "U$3") (pin "CL2") (pinfunction "1_CL2") (pintype "bidirectional"))
      (node (ref "U$3") (pin "CN1") (pinfunction "1_CN1") (pintype "bidirectional"))
      (node (ref "U$3") (pin "CN2") (pinfunction "1_CN2") (pintype "bidirectional"))
      (node (ref "U$3") (pin "CR1") (pinfunction "1_CR1") (pintype "bidirectional"))
      (node (ref "U$3") (pin "CR2") (pinfunction "1_CR2") (pintype "bidirectional"))
      (node (ref "U$3") (pin "CT1") (pinfunction "1_CT1") (pintype "bidirectional"))
      (node (ref "U$3") (pin "CU1") (pinfunction "1_CU1") (pintype "bidirectional"))
      (node (ref "U$3") (pin "CU2") (pinfunction "1_CU2") (pintype "bidirectional"))
      (node (ref "U$3") (pin "CV1") (pinfunction "1_CV1") (pintype "bidirectional"))
    )
    (net (code "32") (name "INIT") (class "Default")
      (node (ref "D42") (pin "A") (pinfunction "A_A") (pintype "passive"))
      (node (ref "E27") (pin "8") (pinfunction "O_8") (pintype "open_collector"))
      (node (ref "Q6") (pin "1") (pinfunction "E_1") (pintype "passive"))
      (node (ref "U$3") (pin "AV2") (pinfunction "1_AV2") (pintype "bidirectional"))
    )
    (net (code "33") (name "IOP1") (class "Default")
      (node (ref "D32") (pin "A") (pinfunction "A_A") (pintype "passive"))
      (node (ref "E14") (pin "2") (pinfunction "O_2") (pintype "open_collector"))
      (node (ref "Q1") (pin "1") (pinfunction "E_1") (pintype "passive"))
      (node (ref "U$3") (pin "AK2") (pinfunction "1_AK2") (pintype "bidirectional"))
    )
    (net (code "34") (name "IOP2") (class "Default")
      (node (ref "D34") (pin "A") (pinfunction "A_A") (pintype "passive"))
      (node (ref "E14") (pin "4") (pinfunction "O_4") (pintype "open_collector"))
      (node (ref "Q2") (pin "1") (pinfunction "E_1") (pintype "passive"))
      (node (ref "U$3") (pin "AM2") (pinfunction "1_AM2") (pintype "bidirectional"))
    )
    (net (code "35") (name "IOP4") (class "Default")
      (node (ref "D36") (pin "A") (pinfunction "A_A") (pintype "passive"))
      (node (ref "E14") (pin "10") (pinfunction "O_10") (pintype "open_collector"))
      (node (ref "Q3") (pin "1") (pinfunction "E_1") (pintype "passive"))
      (node (ref "U$3") (pin "AP2") (pinfunction "1_AP2") (pintype "bidirectional"))
    )
    (net (code "36") (name "NACI00") (class "Default")
      (node (ref "D138") (pin "C") (pinfunction "C_C") (pintype "passive"))
      (node (ref "NACI00") (pin "6") (pinfunction "6_6") (pintype "passive"))
      (node (ref "Q1A") (pin "3") (pinfunction "C_3") (pintype "passive"))
    )
    (net (code "37") (name "NACI01") (class "Default")
      (node (ref "D139") (pin "C") (pinfunction "C_C") (pintype "passive"))
      (node (ref "NACI00") (pin "8") (pinfunction "8_8") (pintype "passive"))
      (node (ref "Q2A") (pin "3") (pinfunction "C_3") (pintype "passive"))
    )
    (net (code "38") (name "NACI02") (class "Default")
      (node (ref "D140") (pin "C") (pinfunction "C_C") (pintype "passive"))
      (node (ref "NACI00") (pin "12") (pinfunction "12_12") (pintype "passive"))
      (node (ref "Q3A") (pin "3") (pinfunction "C_3") (pintype "passive"))
    )
    (net (code "39") (name "NACI03") (class "Default")
      (node (ref "D141") (pin "C") (pinfunction "C_C") (pintype "passive"))
      (node (ref "NACI00") (pin "16") (pinfunction "16_16") (pintype "passive"))
      (node (ref "Q4A") (pin "3") (pinfunction "C_3") (pintype "passive"))
    )
    (net (code "40") (name "NACI04") (class "Default")
      (node (ref "D142") (pin "C") (pinfunction "C_C") (pintype "passive"))
      (node (ref "NACI00") (pin "20") (pinfunction "20_20") (pintype "passive"))
      (node (ref "Q5A") (pin "3") (pinfunction "C_3") (pintype "passive"))
    )
    (net (code "41") (name "NACI05") (class "Default")
      (node (ref "D143") (pin "C") (pinfunction "C_C") (pintype "passive"))
      (node (ref "NACI00") (pin "24") (pinfunction "24_24") (pintype "passive"))
      (node (ref "Q6A") (pin "3") (pinfunction "C_3") (pintype "passive"))
    )
    (net (code "42") (name "NACI06") (class "Default")
      (node (ref "D144") (pin "C") (pinfunction "C_C") (pintype "passive"))
      (node (ref "NACI00") (pin "28") (pinfunction "28_28") (pintype "passive"))
      (node (ref "Q7A") (pin "3") (pinfunction "C_3") (pintype "passive"))
    )
    (net (code "43") (name "NACI07") (class "Default")
      (node (ref "D145") (pin "C") (pinfunction "C_C") (pintype "passive"))
      (node (ref "NACI00") (pin "30") (pinfunction "30_30") (pintype "passive"))
      (node (ref "Q8A") (pin "3") (pinfunction "C_3") (pintype "passive"))
    )
    (net (code "44") (name "NACI08") (class "Default")
      (node (ref "D146") (pin "C") (pinfunction "C_C") (pintype "passive"))
      (node (ref "NACI00") (pin "34") (pinfunction "34_34") (pintype "passive"))
      (node (ref "Q9A") (pin "3") (pinfunction "C_3") (pintype "passive"))
    )
    (net (code "45") (name "NACI09") (class "Default")
      (node (ref "D147") (pin "C") (pinfunction "C_C") (pintype "passive"))
      (node (ref "NACI09") (pin "6") (pinfunction "6_6") (pintype "passive"))
      (node (ref "Q10A") (pin "3") (pinfunction "C_3") (pintype "passive"))
    )
    (net (code "46") (name "NACI10") (class "Default")
      (node (ref "D148") (pin "C") (pinfunction "C_C") (pintype "passive"))
      (node (ref "NACI09") (pin "8") (pinfunction "8_8") (pintype "passive"))
      (node (ref "Q11A") (pin "3") (pinfunction "C_3") (pintype "passive"))
    )
    (net (code "47") (name "NACI11") (class "Default")
      (node (ref "D149") (pin "C") (pinfunction "C_C") (pintype "passive"))
      (node (ref "NACI09") (pin "12") (pinfunction "12_12") (pintype "passive"))
      (node (ref "Q12A") (pin "3") (pinfunction "C_3") (pintype "passive"))
    )
    (net (code "48") (name "NBAC00") (class "Default")
      (node (ref "D54") (pin "C") (pinfunction "C_C") (pintype "passive"))
      (node (ref "D55") (pin "A") (pinfunction "A_A") (pintype "passive"))
      (node (ref "NBAC00") (pin "6") (pinfunction "6_6") (pintype "passive"))
      (node (ref "R5") (pin "1") (pinfunction "1_1") (pintype "passive"))
    )
    (net (code "49") (name "NBAC01") (class "Default")
      (node (ref "D3") (pin "C") (pinfunction "C_C") (pintype "passive"))
      (node (ref "D4") (pin "A") (pinfunction "A_A") (pintype "passive"))
      (node (ref "NBAC00") (pin "8") (pinfunction "8_8") (pintype "passive"))
      (node (ref "R3") (pin "1") (pinfunction "1_1") (pintype "passive"))
    )
    (net (code "50") (name "NBAC02") (class "Default")
      (node (ref "D6") (pin "C") (pinfunction "C_C") (pintype "passive"))
      (node (ref "D7") (pin "A") (pinfunction "A_A") (pintype "passive"))
      (node (ref "NBAC00") (pin "12") (pinfunction "12_12") (pintype "passive"))
      (node (ref "R7") (pin "1") (pinfunction "1_1") (pintype "passive"))
    )
    (net (code "51") (name "NBAC03") (class "Default")
      (node (ref "D10") (pin "A") (pinfunction "A_A") (pintype "passive"))
      (node (ref "D9") (pin "C") (pinfunction "C_C") (pintype "passive"))
      (node (ref "NBAC00") (pin "16") (pinfunction "16_16") (pintype "passive"))
      (node (ref "R10") (pin "1") (pinfunction "1_1") (pintype "passive"))
    )
    (net (code "52") (name "NBAC04") (class "Default")
      (node (ref "D12") (pin "C") (pinfunction "C_C") (pintype "passive"))
      (node (ref "D56") (pin "A") (pinfunction "A_A") (pintype "passive"))
      (node (ref "NBAC00") (pin "20") (pinfunction "20_20") (pintype "passive"))
      (node (ref "R14") (pin "1") (pinfunction "1_1") (pintype "passive"))
    )
    (net (code "53") (name "NBAC05") (class "Default")
      (node (ref "D58") (pin "C") (pinfunction "C_C") (pintype "passive"))
      (node (ref "D59") (pin "A") (pinfunction "A_A") (pintype "passive"))
      (node (ref "NBAC00") (pin "24") (pinfunction "24_24") (pintype "passive"))
      (node (ref "R17") (pin "1") (pinfunction "1_1") (pintype "passive"))
    )
    (net (code "54") (name "NBAC06") (class "Default")
      (node (ref "D61") (pin "C") (pinfunction "C_C") (pintype "passive"))
      (node (ref "D62") (pin "A") (pinfunction "A_A") (pintype "passive"))
      (node (ref "NBAC00") (pin "28") (pinfunction "28_28") (pintype "passive"))
      (node (ref "R20") (pin "1") (pinfunction "1_1") (pintype "passive"))
    )
    (net (code "55") (name "NBAC07") (class "Default")
      (node (ref "D64") (pin "C") (pinfunction "C_C") (pintype "passive"))
      (node (ref "D65") (pin "A") (pinfunction "A_A") (pintype "passive"))
      (node (ref "NBAC00") (pin "30") (pinfunction "30_30") (pintype "passive"))
      (node (ref "R23") (pin "1") (pinfunction "1_1") (pintype "passive"))
    )
    (net (code "56") (name "NBAC08") (class "Default")
      (node (ref "D67") (pin "C") (pinfunction "C_C") (pintype "passive"))
      (node (ref "D68") (pin "A") (pinfunction "A_A") (pintype "passive"))
      (node (ref "NBAC00") (pin "34") (pinfunction "34_34") (pintype "passive"))
      (node (ref "R65") (pin "1") (pinfunction "1_1") (pintype "passive"))
    )
    (net (code "57") (name "NBAC09") (class "Default")
      (node (ref "D70") (pin "C") (pinfunction "C_C") (pintype "passive"))
      (node (ref "D71") (pin "A") (pinfunction "A_A") (pintype "passive"))
      (node (ref "NBAC09") (pin "6") (pinfunction "6_6") (pintype "passive"))
      (node (ref "R68") (pin "1") (pinfunction "1_1") (pintype "passive"))
    )
    (net (code "58") (name "NBAC10") (class "Default")
      (node (ref "D73") (pin "C") (pinfunction "C_C") (pintype "passive"))
      (node (ref "D74") (pin "A") (pinfunction "A_A") (pintype "passive"))
      (node (ref "NBAC09") (pin "8") (pinfunction "8_8") (pintype "passive"))
      (node (ref "R74") (pin "1") (pinfunction "1_1") (pintype "passive"))
    )
    (net (code "59") (name "NBAC11") (class "Default")
      (node (ref "D76") (pin "C") (pinfunction "C_C") (pintype "passive"))
      (node (ref "D77") (pin "A") (pinfunction "A_A") (pintype "passive"))
      (node (ref "NBAC09") (pin "12") (pinfunction "12_12") (pintype "passive"))
      (node (ref "R79") (pin "1") (pinfunction "1_1") (pintype "passive"))
    )
    (net (code "60") (name "NBMB00") (class "Default")
      (node (ref "D114") (pin "C") (pinfunction "C_C") (pintype "passive"))
      (node (ref "D115") (pin "A") (pinfunction "A_A") (pintype "passive"))
      (node (ref "NBMB00") (pin "6") (pinfunction "6_6") (pintype "passive"))
      (node (ref "R105") (pin "1") (pinfunction "1_1") (pintype "passive"))
    )
    (net (code "61") (name "NBMB01") (class "Default")
      (node (ref "D116") (pin "C") (pinfunction "C_C") (pintype "passive"))
      (node (ref "D117") (pin "A") (pinfunction "A_A") (pintype "passive"))
      (node (ref "NBMB00") (pin "8") (pinfunction "8_8") (pintype "passive"))
      (node (ref "R107") (pin "1") (pinfunction "1_1") (pintype "passive"))
    )
    (net (code "62") (name "NBMB02") (class "Default")
      (node (ref "D118") (pin "C") (pinfunction "C_C") (pintype "passive"))
      (node (ref "D119") (pin "A") (pinfunction "A_A") (pintype "passive"))
      (node (ref "NBMB00") (pin "12") (pinfunction "12_12") (pintype "passive"))
      (node (ref "R109") (pin "1") (pinfunction "1_1") (pintype "passive"))
    )
    (net (code "63") (name "NBMB03") (class "Default")
      (node (ref "D120") (pin "C") (pinfunction "C_C") (pintype "passive"))
      (node (ref "D121") (pin "A") (pinfunction "A_A") (pintype "passive"))
      (node (ref "NBMB00") (pin "20") (pinfunction "20_20") (pintype "passive"))
      (node (ref "R111") (pin "1") (pinfunction "1_1") (pintype "passive"))
    )
    (net (code "64") (name "NBMB04") (class "Default")
      (node (ref "D122") (pin "C") (pinfunction "C_C") (pintype "passive"))
      (node (ref "D123") (pin "A") (pinfunction "A_A") (pintype "passive"))
      (node (ref "NBMB00") (pin "28") (pinfunction "28_28") (pintype "passive"))
      (node (ref "R113") (pin "1") (pinfunction "1_1") (pintype "passive"))
    )
    (net (code "65") (name "NBMB05") (class "Default")
      (node (ref "D124") (pin "C") (pinfunction "C_C") (pintype "passive"))
      (node (ref "D125") (pin "A") (pinfunction "A_A") (pintype "passive"))
      (node (ref "NBMB00") (pin "34") (pinfunction "34_34") (pintype "passive"))
      (node (ref "R115") (pin "1") (pinfunction "1_1") (pintype "passive"))
    )
    (net (code "66") (name "NBMB06") (class "Default")
      (node (ref "D126") (pin "C") (pinfunction "C_C") (pintype "passive"))
      (node (ref "D127") (pin "A") (pinfunction "A_A") (pintype "passive"))
      (node (ref "NBMB06") (pin "8") (pinfunction "8_8") (pintype "passive"))
      (node (ref "R117") (pin "1") (pinfunction "1_1") (pintype "passive"))
    )
    (net (code "67") (name "NBMB07") (class "Default")
      (node (ref "D128") (pin "C") (pinfunction "C_C") (pintype "passive"))
      (node (ref "D129") (pin "A") (pinfunction "A_A") (pintype "passive"))
      (node (ref "NBMB06") (pin "16") (pinfunction "16_16") (pintype "passive"))
      (node (ref "R119") (pin "1") (pinfunction "1_1") (pintype "passive"))
    )
    (net (code "68") (name "NBMB08") (class "Default")
      (node (ref "D130") (pin "C") (pinfunction "C_C") (pintype "passive"))
      (node (ref "D131") (pin "A") (pinfunction "A_A") (pintype "passive"))
      (node (ref "NBMB06") (pin "24") (pinfunction "24_24") (pintype "passive"))
      (node (ref "R121") (pin "1") (pinfunction "1_1") (pintype "passive"))
    )
    (net (code "69") (name "NBMB09") (class "Default")
      (node (ref "D132") (pin "C") (pinfunction "C_C") (pintype "passive"))
      (node (ref "D133") (pin "A") (pinfunction "A_A") (pintype "passive"))
      (node (ref "NBMB06") (pin "28") (pinfunction "28_28") (pintype "passive"))
      (node (ref "R123") (pin "1") (pinfunction "1_1") (pintype "passive"))
    )
    (net (code "70") (name "NBMB10") (class "Default")
      (node (ref "D134") (pin "C") (pinfunction "C_C") (pintype "passive"))
      (node (ref "D135") (pin "A") (pinfunction "A_A") (pintype "passive"))
      (node (ref "NBMB06") (pin "30") (pinfunction "30_30") (pintype "passive"))
      (node (ref "R125") (pin "1") (pinfunction "1_1") (pintype "passive"))
    )
    (net (code "71") (name "NBMB11") (class "Default")
      (node (ref "D136") (pin "C") (pinfunction "C_C") (pintype "passive"))
      (node (ref "D137") (pin "A") (pinfunction "A_A") (pintype "passive"))
      (node (ref "NBMB06") (pin "34") (pinfunction "34_34") (pintype "passive"))
      (node (ref "R127") (pin "1") (pinfunction "1_1") (pintype "passive"))
    )
    (net (code "72") (name "NCLRRQ") (class "Default")
      (node (ref "D152") (pin "C") (pinfunction "C_C") (pintype "passive"))
      (node (ref "NACI09") (pin "24") (pinfunction "24_24") (pintype "passive"))
      (node (ref "Q52") (pin "3") (pinfunction "C_3") (pintype "passive"))
    )
    (net (code "73") (name "NINTRQ") (class "Default")
      (node (ref "D151") (pin "C") (pinfunction "C_C") (pintype "passive"))
      (node (ref "NACI09") (pin "20") (pinfunction "20_20") (pintype "passive"))
      (node (ref "Q51") (pin "3") (pinfunction "C_3") (pintype "passive"))
    )
    (net (code "74") (name "NLINE") (class "Default")
      (node (ref "NACI09") (pin "34") (pinfunction "34_34") (pintype "passive"))
    )
    (net (code "75") (name "NSKPRQ") (class "Default")
      (node (ref "D150") (pin "C") (pinfunction "C_C") (pintype "passive"))
      (node (ref "NACI09") (pin "16") (pinfunction "16_16") (pintype "passive"))
      (node (ref "Q50") (pin "3") (pinfunction "C_3") (pintype "passive"))
    )
    (net (code "76") (name "NTP1") (class "Default")
      (node (ref "D96") (pin "C") (pinfunction "C_C") (pintype "passive"))
      (node (ref "D97") (pin "A") (pinfunction "A_A") (pintype "passive"))
      (node (ref "D98") (pin "C") (pinfunction "C_C") (pintype "passive"))
      (node (ref "NBAC09") (pin "28") (pinfunction "28_28") (pintype "passive"))
    )
    (net (code "77") (name "NTP2A") (class "Default")
      (node (ref "D102") (pin "C") (pinfunction "C_C") (pintype "passive"))
      (node (ref "D103") (pin "A") (pinfunction "A_A") (pintype "passive"))
      (node (ref "D104") (pin "C") (pinfunction "C_C") (pintype "passive"))
      (node (ref "NBAC09") (pin "30") (pinfunction "30_30") (pintype "passive"))
    )
    (net (code "78") (name "NTTINST") (class "Default")
      (node (ref "NACI09") (pin "30") (pinfunction "30_30") (pintype "passive"))
    )
    (net (code "79") (name "Net-(D44-PadC)") (class "Default")
      (node (ref "D44") (pin "C") (pinfunction "C_C") (pintype "passive"))
      (node (ref "D45") (pin "A") (pinfunction "A_A") (pintype "passive"))
    )
    (net (code "80") (name "Net-(D45-PadC)") (class "Default")
      (node (ref "D45") (pin "C") (pinfunction "C_C") (pintype "passive"))
      (node (ref "D46") (pin "A") (pinfunction "A_A") (pintype "passive"))
    )
    (net (code "81") (name "Net-(D46-PadC)") (class "Default")
      (node (ref "D46") (pin "C") (pinfunction "C_C") (pintype "passive"))
      (node (ref "D47") (pin "A") (pinfunction "A_A") (pintype "passive"))
    )
    (net (code "82") (name "Net-(D48-PadC)") (class "Default")
      (node (ref "D48") (pin "C") (pinfunction "C_C") (pintype "passive"))
      (node (ref "D49") (pin "A") (pinfunction "A_A") (pintype "passive"))
    )
    (net (code "83") (name "Net-(D50-PadC)") (class "Default")
      (node (ref "D50") (pin "C") (pinfunction "C_C") (pintype "passive"))
      (node (ref "D51") (pin "A") (pinfunction "A_A") (pintype "passive"))
    )
    (net (code "84") (name "Net-(D52-PadC)") (class "Default")
      (node (ref "D52") (pin "C") (pinfunction "C_C") (pintype "passive"))
      (node (ref "R129") (pin "2") (pinfunction "2_2") (pintype "passive"))
      (node (ref "R77") (pin "2") (pinfunction "2_2") (pintype "passive"))
    )
    (net (code "85") (name "Net-(D80-PadA)") (class "Default")
      (node (ref "D80") (pin "A") (pinfunction "A_A") (pintype "passive"))
      (node (ref "D81") (pin "C") (pinfunction "C_C") (pintype "passive"))
    )
    (net (code "86") (name "Net-(D81-PadA)") (class "Default")
      (node (ref "D81") (pin "A") (pinfunction "A_A") (pintype "passive"))
      (node (ref "D82") (pin "C") (pinfunction "C_C") (pintype "passive"))
    )
    (net (code "87") (name "Net-(D86-PadA)") (class "Default")
      (node (ref "D86") (pin "A") (pinfunction "A_A") (pintype "passive"))
      (node (ref "D87") (pin "C") (pinfunction "C_C") (pintype "passive"))
    )
    (net (code "88") (name "Net-(D87-PadA)") (class "Default")
      (node (ref "D87") (pin "A") (pinfunction "A_A") (pintype "passive"))
      (node (ref "D88") (pin "C") (pinfunction "C_C") (pintype "passive"))
    )
    (net (code "89") (name "Net-(D92-PadA)") (class "Default")
      (node (ref "D92") (pin "A") (pinfunction "A_A") (pintype "passive"))
      (node (ref "D93") (pin "C") (pinfunction "C_C") (pintype "passive"))
    )
    (net (code "90") (name "Net-(D93-PadA)") (class "Default")
      (node (ref "D93") (pin "A") (pinfunction "A_A") (pintype "passive"))
      (node (ref "D94") (pin "C") (pinfunction "C_C") (pintype "passive"))
    )
    (net (code "91") (name "Net-(D98-PadA)") (class "Default")
      (node (ref "D98") (pin "A") (pinfunction "A_A") (pintype "passive"))
      (node (ref "D99") (pin "C") (pinfunction "C_C") (pintype "passive"))
    )
    (net (code "92") (name "Net-(D100-PadC)") (class "Default")
      (node (ref "D100") (pin "C") (pinfunction "C_C") (pintype "passive"))
      (node (ref "D99") (pin "A") (pinfunction "A_A") (pintype "passive"))
    )
    (net (code "93") (name "Net-(D104-PadA)") (class "Default")
      (node (ref "D104") (pin "A") (pinfunction "A_A") (pintype "passive"))
      (node (ref "D105") (pin "C") (pinfunction "C_C") (pintype "passive"))
    )
    (net (code "94") (name "Net-(D105-PadA)") (class "Default")
      (node (ref "D105") (pin "A") (pinfunction "A_A") (pintype "passive"))
      (node (ref "D106") (pin "C") (pinfunction "C_C") (pintype "passive"))
    )
    (net (code "95") (name "Net-(D110-PadA)") (class "Default")
      (node (ref "D110") (pin "A") (pinfunction "A_A") (pintype "passive"))
      (node (ref "D111") (pin "C") (pinfunction "C_C") (pintype "passive"))
    )
    (net (code "96") (name "Net-(D111-PadA)") (class "Default")
      (node (ref "D111") (pin "A") (pinfunction "A_A") (pintype "passive"))
      (node (ref "D112") (pin "C") (pinfunction "C_C") (pintype "passive"))
    )
    (net (code "97") (name "Net-(E1A-I)") (class "Default")
      (node (ref "E1") (pin "1") (pinfunction "I_1") (pintype "input"))
      (node (ref "Q3B") (pin "3") (pinfunction "C_3") (pintype "passive"))
      (node (ref "R8") (pin "1") (pinfunction "1_1") (pintype "passive"))
    )
    (net (code "98") (name "Net-(E1B-I)") (class "Default")
      (node (ref "E1") (pin "3") (pinfunction "I_3") (pintype "input"))
      (node (ref "Q2B") (pin "3") (pinfunction "C_3") (pintype "passive"))
      (node (ref "R4") (pin "1") (pinfunction "1_1") (pintype "passive"))
    )
    (net (code "99") (name "Net-(E1C-I)") (class "Default")
      (node (ref "E1") (pin "5") (pinfunction "I_5") (pintype "input"))
      (node (ref "Q1B") (pin "3") (pinfunction "C_3") (pintype "passive"))
      (node (ref "R1") (pin "1") (pinfunction "1_1") (pintype "passive"))
    )
    (net (code "100") (name "Net-(E1D-I)") (class "Default")
      (node (ref "E1") (pin "9") (pinfunction "I_9") (pintype "input"))
      (node (ref "Q10B") (pin "3") (pinfunction "C_3") (pintype "passive"))
      (node (ref "R72") (pin "1") (pinfunction "1_1") (pintype "passive"))
    )
    (net (code "101") (name "Net-(E1E-I)") (class "Default")
      (node (ref "E1") (pin "11") (pinfunction "I_11") (pintype "input"))
      (node (ref "Q11B") (pin "3") (pinfunction "C_3") (pintype "passive"))
      (node (ref "R75") (pin "1") (pinfunction "1_1") (pintype "passive"))
    )
    (net (code "102") (name "Net-(E1F-I)") (class "Default")
      (node (ref "E1") (pin "13") (pinfunction "I_13") (pintype "input"))
      (node (ref "Q12B") (pin "3") (pinfunction "C_3") (pintype "passive"))
      (node (ref "R80") (pin "1") (pinfunction "1_1") (pintype "passive"))
    )
    (net (code "103") (name "Net-(E2A-I)") (class "Default")
      (node (ref "E2") (pin "1") (pinfunction "I_1") (pintype "input"))
      (node (ref "Q6B") (pin "3") (pinfunction "C_3") (pintype "passive"))
      (node (ref "R18") (pin "1") (pinfunction "1_1") (pintype "passive"))
    )
    (net (code "104") (name "Net-(E2B-I)") (class "Default")
      (node (ref "E2") (pin "3") (pinfunction "I_3") (pintype "input"))
      (node (ref "Q5B") (pin "3") (pinfunction "C_3") (pintype "passive"))
      (node (ref "R15") (pin "1") (pinfunction "1_1") (pintype "passive"))
    )
    (net (code "105") (name "Net-(E2C-I)") (class "Default")
      (node (ref "E2") (pin "5") (pinfunction "I_5") (pintype "input"))
      (node (ref "Q4B") (pin "3") (pinfunction "C_3") (pintype "passive"))
      (node (ref "R11") (pin "1") (pinfunction "1_1") (pintype "passive"))
    )
    (net (code "106") (name "Net-(E2D-I)") (class "Default")
      (node (ref "E2") (pin "9") (pinfunction "I_9") (pintype "input"))
      (node (ref "Q9B") (pin "3") (pinfunction "C_3") (pintype "passive"))
      (node (ref "R66") (pin "1") (pinfunction "1_1") (pintype "passive"))
    )
    (net (code "107") (name "Net-(E2E-I)") (class "Default")
      (node (ref "E2") (pin "11") (pinfunction "I_11") (pintype "input"))
      (node (ref "Q8B") (pin "3") (pinfunction "C_3") (pintype "passive"))
      (node (ref "R24") (pin "1") (pinfunction "1_1") (pintype "passive"))
    )
    (net (code "108") (name "Net-(E2F-I)") (class "Default")
      (node (ref "E2") (pin "13") (pinfunction "I_13") (pintype "input"))
      (node (ref "Q7B") (pin "3") (pinfunction "C_3") (pintype "passive"))
      (node (ref "R21") (pin "1") (pinfunction "1_1") (pintype "passive"))
    )
    (net (code "109") (name "Net-(E4A-O)") (class "Default")
      (node (ref "C41") (pin "1") (pinfunction "1_1") (pintype "passive"))
      (node (ref "E4") (pin "2") (pinfunction "O_2") (pintype "output"))
      (node (ref "R159") (pin "1") (pinfunction "1_1") (pintype "passive"))
    )
    (net (code "110") (name "Net-(E4B-O)") (class "Default")
      (node (ref "C34") (pin "1") (pinfunction "1_1") (pintype "passive"))
      (node (ref "E4") (pin "4") (pinfunction "O_4") (pintype "output"))
      (node (ref "R144") (pin "1") (pinfunction "1_1") (pintype "passive"))
    )
    (net (code "111") (name "Net-(E4E-O)") (class "Default")
      (node (ref "C35") (pin "1") (pinfunction "1_1") (pintype "passive"))
      (node (ref "E4") (pin "10") (pinfunction "O_10") (pintype "output"))
      (node (ref "R146") (pin "1") (pinfunction "1_1") (pintype "passive"))
    )
    (net (code "112") (name "Net-(E4F-O)") (class "Default")
      (node (ref "C42") (pin "1") (pinfunction "1_1") (pintype "passive"))
      (node (ref "E4") (pin "12") (pinfunction "O_12") (pintype "output"))
      (node (ref "R69") (pin "1") (pinfunction "1_1") (pintype "passive"))
    )
    (net (code "113") (name "Net-(E13A-I)") (class "Default")
      (node (ref "E13") (pin "1") (pinfunction "I_1") (pintype "input"))
      (node (ref "Q28") (pin "3") (pinfunction "C_3") (pintype "passive"))
      (node (ref "R110") (pin "1") (pinfunction "1_1") (pintype "passive"))
    )
    (net (code "114") (name "Net-(E13B-I)") (class "Default")
      (node (ref "E13") (pin "3") (pinfunction "I_3") (pintype "input"))
      (node (ref "Q27") (pin "3") (pinfunction "C_3") (pintype "passive"))
      (node (ref "R108") (pin "1") (pinfunction "1_1") (pintype "passive"))
    )
    (net (code "115") (name "Net-(E13C-I)") (class "Default")
      (node (ref "E13") (pin "5") (pinfunction "I_5") (pintype "input"))
      (node (ref "Q26") (pin "3") (pinfunction "C_3") (pintype "passive"))
      (node (ref "R106") (pin "1") (pinfunction "1_1") (pintype "passive"))
    )
    (net (code "116") (name "Net-(E13D-I)") (class "Default")
      (node (ref "E13") (pin "11") (pinfunction "I_11") (pintype "input"))
      (node (ref "E13") (pin "9") (pinfunction "I_9") (pintype "input"))
      (node (ref "E17") (pin "1") (pinfunction "I_1") (pintype "input"))
      (node (ref "E17") (pin "3") (pinfunction "I_3") (pintype "input"))
      (node (ref "Q32") (pin "3") (pinfunction "C_3") (pintype "passive"))
      (node (ref "R118") (pin "1") (pinfunction "1_1") (pintype "passive"))
    )
    (net (code "117") (name "Net-(E13F-I)") (class "Default")
      (node (ref "E13") (pin "13") (pinfunction "I_13") (pintype "input"))
      (node (ref "E21") (pin "1") (pinfunction "I_1") (pintype "input"))
      (node (ref "E21") (pin "3") (pinfunction "I_3") (pintype "input"))
      (node (ref "E22") (pin "5") (pinfunction "I_5") (pintype "input"))
      (node (ref "Q34") (pin "3") (pinfunction "C_3") (pintype "passive"))
      (node (ref "R122") (pin "1") (pinfunction "1_1") (pintype "passive"))
    )
    (net (code "118") (name "Net-(E14A-I)") (class "Default")
      (node (ref "D95") (pin "A") (pinfunction "A_A") (pintype "passive"))
      (node (ref "E14") (pin "1") (pinfunction "I_1") (pintype "input"))
      (node (ref "E14") (pin "13") (pinfunction "I_13") (pintype "input"))
      (node (ref "Q15B") (pin "3") (pinfunction "C_3") (pintype "passive"))
      (node (ref "R98") (pin "1") (pinfunction "1_1") (pintype "passive"))
    )
    (net (code "119") (name "Net-(E14B-I)") (class "Default")
      (node (ref "D89") (pin "A") (pinfunction "A_A") (pintype "passive"))
      (node (ref "E14") (pin "3") (pinfunction "I_3") (pintype "input"))
      (node (ref "E14") (pin "5") (pinfunction "I_5") (pintype "input"))
      (node (ref "Q14B") (pin "3") (pinfunction "C_3") (pintype "passive"))
      (node (ref "R84") (pin "1") (pinfunction "1_1") (pintype "passive"))
    )
    (net (code "120") (name "Net-(E14C-O)") (class "Default")
      (node (ref "D35") (pin "A") (pinfunction "A_A") (pintype "passive"))
      (node (ref "E14") (pin "6") (pinfunction "O_6") (pintype "open_collector"))
      (node (ref "Q2") (pin "2") (pinfunction "B_2") (pintype "passive"))
      (node (ref "R48") (pin "1") (pinfunction "1_1") (pintype "passive"))
    )
    (net (code "121") (name "Net-(E14D-I)") (class "Default")
      (node (ref "D83") (pin "A") (pinfunction "A_A") (pintype "passive"))
      (node (ref "E14") (pin "11") (pinfunction "I_11") (pintype "input"))
      (node (ref "E14") (pin "9") (pinfunction "I_9") (pintype "input"))
      (node (ref "Q13B") (pin "3") (pinfunction "C_3") (pintype "passive"))
      (node (ref "R82") (pin "1") (pinfunction "1_1") (pintype "passive"))
    )
    (net (code "122") (name "Net-(E14D-O)") (class "Default")
      (node (ref "D31") (pin "A") (pinfunction "A_A") (pintype "passive"))
      (node (ref "E14") (pin "8") (pinfunction "O_8") (pintype "open_collector"))
      (node (ref "Q3") (pin "2") (pinfunction "B_2") (pintype "passive"))
      (node (ref "R51") (pin "1") (pinfunction "1_1") (pintype "passive"))
    )
    (net (code "123") (name "Net-(E14F-O)") (class "Default")
      (node (ref "D33") (pin "A") (pinfunction "A_A") (pintype "passive"))
      (node (ref "E14") (pin "12") (pinfunction "O_12") (pintype "open_collector"))
      (node (ref "Q1") (pin "2") (pinfunction "B_2") (pintype "passive"))
      (node (ref "R45") (pin "1") (pinfunction "1_1") (pintype "passive"))
    )
    (net (code "124") (name "Net-(E17C-I)") (class "Default")
      (node (ref "E17") (pin "5") (pinfunction "I_5") (pintype "input"))
      (node (ref "E17") (pin "9") (pinfunction "I_9") (pintype "input"))
      (node (ref "E18") (pin "1") (pinfunction "I_1") (pintype "input"))
      (node (ref "E18") (pin "3") (pinfunction "I_3") (pintype "input"))
      (node (ref "Q29") (pin "3") (pinfunction "C_3") (pintype "passive"))
      (node (ref "R112") (pin "1") (pinfunction "1_1") (pintype "passive"))
    )
    (net (code "125") (name "Net-(E17E-I)") (class "Default")
      (node (ref "E17") (pin "11") (pinfunction "I_11") (pintype "input"))
      (node (ref "E17") (pin "13") (pinfunction "I_13") (pintype "input"))
      (node (ref "E18") (pin "5") (pinfunction "I_5") (pintype "input"))
      (node (ref "E18") (pin "9") (pinfunction "I_9") (pintype "input"))
      (node (ref "Q33") (pin "3") (pinfunction "C_3") (pintype "passive"))
      (node (ref "R120") (pin "1") (pinfunction "1_1") (pintype "passive"))
    )
    (net (code "126") (name "Net-(E18E-I)") (class "Default")
      (node (ref "E18") (pin "11") (pinfunction "I_11") (pintype "input"))
      (node (ref "E18") (pin "13") (pinfunction "I_13") (pintype "input"))
      (node (ref "E21") (pin "5") (pinfunction "I_5") (pintype "input"))
      (node (ref "E21") (pin "9") (pinfunction "I_9") (pintype "input"))
      (node (ref "Q30") (pin "3") (pinfunction "C_3") (pintype "passive"))
      (node (ref "R114") (pin "1") (pinfunction "1_1") (pintype "passive"))
    )
    (net (code "127") (name "Net-(E21E-I)") (class "Default")
      (node (ref "E21") (pin "11") (pinfunction "I_11") (pintype "input"))
      (node (ref "E21") (pin "13") (pinfunction "I_13") (pintype "input"))
      (node (ref "E22") (pin "1") (pinfunction "I_1") (pintype "input"))
      (node (ref "E22") (pin "3") (pinfunction "I_3") (pintype "input"))
      (node (ref "Q31") (pin "3") (pinfunction "C_3") (pintype "passive"))
      (node (ref "R116") (pin "1") (pinfunction "1_1") (pintype "passive"))
    )
    (net (code "128") (name "Net-(E22D-I)") (class "Default")
      (node (ref "E22") (pin "9") (pinfunction "I_9") (pintype "input"))
      (node (ref "Q37") (pin "3") (pinfunction "C_3") (pintype "passive"))
      (node (ref "R128") (pin "1") (pinfunction "1_1") (pintype "passive"))
    )
    (net (code "129") (name "Net-(E22E-I)") (class "Default")
      (node (ref "E22") (pin "11") (pinfunction "I_11") (pintype "input"))
      (node (ref "Q36") (pin "3") (pinfunction "C_3") (pintype "passive"))
      (node (ref "R126") (pin "1") (pinfunction "1_1") (pintype "passive"))
    )
    (net (code "130") (name "Net-(E22F-I)") (class "Default")
      (node (ref "E22") (pin "13") (pinfunction "I_13") (pintype "input"))
      (node (ref "Q35") (pin "3") (pinfunction "C_3") (pintype "passive"))
      (node (ref "R124") (pin "1") (pinfunction "1_1") (pintype "passive"))
    )
    (net (code "131") (name "Net-(E27A-I)") (class "Default")
      (node (ref "D107") (pin "A") (pinfunction "A_A") (pintype "passive"))
      (node (ref "E27") (pin "1") (pinfunction "I_1") (pintype "input"))
      (node (ref "E27") (pin "3") (pinfunction "I_3") (pintype "input"))
      (node (ref "Q17B") (pin "3") (pinfunction "C_3") (pintype "passive"))
      (node (ref "R102") (pin "1") (pinfunction "1_1") (pintype "passive"))
    )
    (net (code "132") (name "Net-(E27A-O)") (class "Default")
      (node (ref "D41") (pin "A") (pinfunction "A_A") (pintype "passive"))
      (node (ref "E27") (pin "2") (pinfunction "O_2") (pintype "open_collector"))
      (node (ref "Q5") (pin "2") (pinfunction "B_2") (pintype "passive"))
      (node (ref "R57") (pin "1") (pinfunction "1_1") (pintype "passive"))
    )
    (net (code "133") (name "Net-(E27C-I)") (class "Default")
      (node (ref "D113") (pin "A") (pinfunction "A_A") (pintype "passive"))
      (node (ref "E27") (pin "5") (pinfunction "I_5") (pintype "input"))
      (node (ref "E27") (pin "9") (pinfunction "I_9") (pintype "input"))
      (node (ref "Q18B") (pin "3") (pinfunction "C_3") (pintype "passive"))
      (node (ref "R104") (pin "1") (pinfunction "1_1") (pintype "passive"))
    )
    (net (code "134") (name "Net-(E27C-O)") (class "Default")
      (node (ref "D43") (pin "A") (pinfunction "A_A") (pintype "passive"))
      (node (ref "E27") (pin "6") (pinfunction "O_6") (pintype "open_collector"))
      (node (ref "Q6") (pin "2") (pinfunction "B_2") (pintype "passive"))
      (node (ref "R60") (pin "1") (pinfunction "1_1") (pintype "passive"))
    )
    (net (code "135") (name "Net-(E27E-I)") (class "Default")
      (node (ref "D101") (pin "A") (pinfunction "A_A") (pintype "passive"))
      (node (ref "E27") (pin "11") (pinfunction "I_11") (pintype "input"))
      (node (ref "E27") (pin "13") (pinfunction "I_13") (pintype "input"))
      (node (ref "Q16B") (pin "3") (pinfunction "C_3") (pintype "passive"))
      (node (ref "R100") (pin "1") (pinfunction "1_1") (pintype "passive"))
    )
    (net (code "136") (name "Net-(E27E-O)") (class "Default")
      (node (ref "D37") (pin "A") (pinfunction "A_A") (pintype "passive"))
      (node (ref "E27") (pin "10") (pinfunction "O_10") (pintype "open_collector"))
      (node (ref "Q4") (pin "2") (pinfunction "B_2") (pintype "passive"))
      (node (ref "R54") (pin "1") (pinfunction "1_1") (pintype "passive"))
    )
    (net (code "137") (name "Net-(E48A-O)") (class "Default")
      (node (ref "C27") (pin "1") (pinfunction "1_1") (pintype "passive"))
      (node (ref "E48") (pin "2") (pinfunction "O_2") (pintype "output"))
      (node (ref "R132") (pin "1") (pinfunction "1_1") (pintype "passive"))
    )
    (net (code "138") (name "Net-(E48B-O)") (class "Default")
      (node (ref "C36") (pin "1") (pinfunction "1_1") (pintype "passive"))
      (node (ref "E48") (pin "4") (pinfunction "O_4") (pintype "output"))
      (node (ref "R148") (pin "1") (pinfunction "1_1") (pintype "passive"))
    )
    (net (code "139") (name "Net-(E48C-O)") (class "Default")
      (node (ref "C26") (pin "1") (pinfunction "1_1") (pintype "passive"))
      (node (ref "E48") (pin "6") (pinfunction "O_6") (pintype "output"))
      (node (ref "R130") (pin "1") (pinfunction "1_1") (pintype "passive"))
    )
    (net (code "140") (name "Net-(E48D-O)") (class "Default")
      (node (ref "C37") (pin "1") (pinfunction "1_1") (pintype "passive"))
      (node (ref "E48") (pin "8") (pinfunction "O_8") (pintype "output"))
      (node (ref "R150") (pin "1") (pinfunction "1_1") (pintype "passive"))
    )
    (net (code "141") (name "Net-(E48E-O)") (class "Default")
      (node (ref "C38") (pin "1") (pinfunction "1_1") (pintype "passive"))
      (node (ref "E48") (pin "10") (pinfunction "O_10") (pintype "output"))
      (node (ref "R152") (pin "1") (pinfunction "1_1") (pintype "passive"))
    )
    (net (code "142") (name "Net-(E48F-O)") (class "Default")
      (node (ref "C28") (pin "1") (pinfunction "1_1") (pintype "passive"))
      (node (ref "E48") (pin "12") (pinfunction "O_12") (pintype "output"))
      (node (ref "R134") (pin "1") (pinfunction "1_1") (pintype "passive"))
    )
    (net (code "143") (name "Net-(E49A-O)") (class "Default")
      (node (ref "C39") (pin "1") (pinfunction "1_1") (pintype "passive"))
      (node (ref "E49") (pin "2") (pinfunction "O_2") (pintype "output"))
      (node (ref "R155") (pin "1") (pinfunction "1_1") (pintype "passive"))
    )
    (net (code "144") (name "Net-(E49B-O)") (class "Default")
      (node (ref "C30") (pin "1") (pinfunction "1_1") (pintype "passive"))
      (node (ref "E49") (pin "4") (pinfunction "O_4") (pintype "output"))
      (node (ref "R138") (pin "1") (pinfunction "1_1") (pintype "passive"))
    )
    (net (code "145") (name "Net-(E49C-O)") (class "Default")
      (node (ref "C29") (pin "1") (pinfunction "1_1") (pintype "passive"))
      (node (ref "E49") (pin "6") (pinfunction "O_6") (pintype "output"))
      (node (ref "R136") (pin "1") (pinfunction "1_1") (pintype "passive"))
    )
    (net (code "146") (name "Net-(E49D-O)") (class "Default")
      (node (ref "C33") (pin "1") (pinfunction "1_1") (pintype "passive"))
      (node (ref "E49") (pin "8") (pinfunction "O_8") (pintype "output"))
      (node (ref "R142") (pin "1") (pinfunction "1_1") (pintype "passive"))
    )
    (net (code "147") (name "Net-(E49E-O)") (class "Default")
      (node (ref "C40") (pin "1") (pinfunction "1_1") (pintype "passive"))
      (node (ref "E49") (pin "10") (pinfunction "O_10") (pintype "output"))
      (node (ref "R157") (pin "1") (pinfunction "1_1") (pintype "passive"))
    )
    (net (code "148") (name "Net-(E49F-O)") (class "Default")
      (node (ref "C31") (pin "1") (pinfunction "1_1") (pintype "passive"))
      (node (ref "E49") (pin "12") (pinfunction "O_12") (pintype "output"))
      (node (ref "R140") (pin "1") (pinfunction "1_1") (pintype "passive"))
    )
    (net (code "149") (name "Net-(Q1-C)") (class "Default")
      (node (ref "C24") (pin "1") (pinfunction "1_1") (pintype "passive"))
      (node (ref "Q1") (pin "3") (pinfunction "C_3") (pintype "passive"))
      (node (ref "R44") (pin "1") (pinfunction "1_1") (pintype "passive"))
    )
    (net (code "150") (name "Net-(Q1A-B)") (class "Default")
      (node (ref "C26") (pin "2") (pinfunction "2_2") (pintype "passive"))
      (node (ref "Q1A") (pin "2") (pinfunction "B_2") (pintype "passive"))
      (node (ref "R130") (pin "2") (pinfunction "2_2") (pintype "passive"))
      (node (ref "R131") (pin "1") (pinfunction "1_1") (pintype "passive"))
    )
    (net (code "151") (name "Net-(Q1B-E)") (class "Default")
      (node (ref "Q1B") (pin "1") (pinfunction "E_1") (pintype "passive"))
      (node (ref "R5") (pin "2") (pinfunction "2_2") (pintype "passive"))
    )
    (net (code "152") (name "Net-(Q2-C)") (class "Default")
      (node (ref "C23") (pin "1") (pinfunction "1_1") (pintype "passive"))
      (node (ref "Q2") (pin "3") (pinfunction "C_3") (pintype "passive"))
      (node (ref "R47") (pin "1") (pinfunction "1_1") (pintype "passive"))
    )
    (net (code "153") (name "Net-(Q2A-B)") (class "Default")
      (node (ref "C27") (pin "2") (pinfunction "2_2") (pintype "passive"))
      (node (ref "Q2A") (pin "2") (pinfunction "B_2") (pintype "passive"))
      (node (ref "R132") (pin "2") (pinfunction "2_2") (pintype "passive"))
      (node (ref "R133") (pin "1") (pinfunction "1_1") (pintype "passive"))
    )
    (net (code "154") (name "Net-(Q2B-E)") (class "Default")
      (node (ref "Q2B") (pin "1") (pinfunction "E_1") (pintype "passive"))
      (node (ref "R3") (pin "2") (pinfunction "2_2") (pintype "passive"))
    )
    (net (code "155") (name "Net-(Q3-C)") (class "Default")
      (node (ref "C25") (pin "1") (pinfunction "1_1") (pintype "passive"))
      (node (ref "Q3") (pin "3") (pinfunction "C_3") (pintype "passive"))
      (node (ref "R50") (pin "1") (pinfunction "1_1") (pintype "passive"))
    )
    (net (code "156") (name "Net-(Q3A-B)") (class "Default")
      (node (ref "C28") (pin "2") (pinfunction "2_2") (pintype "passive"))
      (node (ref "Q3A") (pin "2") (pinfunction "B_2") (pintype "passive"))
      (node (ref "R134") (pin "2") (pinfunction "2_2") (pintype "passive"))
      (node (ref "R135") (pin "1") (pinfunction "1_1") (pintype "passive"))
    )
    (net (code "157") (name "Net-(Q3B-E)") (class "Default")
      (node (ref "Q3B") (pin "1") (pinfunction "E_1") (pintype "passive"))
      (node (ref "R7") (pin "2") (pinfunction "2_2") (pintype "passive"))
    )
    (net (code "158") (name "Net-(Q4-C)") (class "Default")
      (node (ref "Q4") (pin "3") (pinfunction "C_3") (pintype "passive"))
      (node (ref "R53") (pin "1") (pinfunction "1_1") (pintype "passive"))
    )
    (net (code "159") (name "Net-(Q4A-B)") (class "Default")
      (node (ref "C29") (pin "2") (pinfunction "2_2") (pintype "passive"))
      (node (ref "Q4A") (pin "2") (pinfunction "B_2") (pintype "passive"))
      (node (ref "R136") (pin "2") (pinfunction "2_2") (pintype "passive"))
      (node (ref "R137") (pin "1") (pinfunction "1_1") (pintype "passive"))
    )
    (net (code "160") (name "Net-(Q4B-E)") (class "Default")
      (node (ref "Q4B") (pin "1") (pinfunction "E_1") (pintype "passive"))
      (node (ref "R10") (pin "2") (pinfunction "2_2") (pintype "passive"))
    )
    (net (code "161") (name "Net-(Q5-C)") (class "Default")
      (node (ref "Q5") (pin "3") (pinfunction "C_3") (pintype "passive"))
      (node (ref "R56") (pin "1") (pinfunction "1_1") (pintype "passive"))
    )
    (net (code "162") (name "Net-(Q5A-B)") (class "Default")
      (node (ref "C30") (pin "2") (pinfunction "2_2") (pintype "passive"))
      (node (ref "Q5A") (pin "2") (pinfunction "B_2") (pintype "passive"))
      (node (ref "R138") (pin "2") (pinfunction "2_2") (pintype "passive"))
      (node (ref "R139") (pin "1") (pinfunction "1_1") (pintype "passive"))
    )
    (net (code "163") (name "Net-(Q5B-E)") (class "Default")
      (node (ref "Q5B") (pin "1") (pinfunction "E_1") (pintype "passive"))
      (node (ref "R14") (pin "2") (pinfunction "2_2") (pintype "passive"))
    )
    (net (code "164") (name "Net-(Q6-C)") (class "Default")
      (node (ref "Q6") (pin "3") (pinfunction "C_3") (pintype "passive"))
      (node (ref "R59") (pin "1") (pinfunction "1_1") (pintype "passive"))
    )
    (net (code "165") (name "Net-(Q6A-B)") (class "Default")
      (node (ref "C31") (pin "2") (pinfunction "2_2") (pintype "passive"))
      (node (ref "Q6A") (pin "2") (pinfunction "B_2") (pintype "passive"))
      (node (ref "R140") (pin "2") (pinfunction "2_2") (pintype "passive"))
      (node (ref "R141") (pin "1") (pinfunction "1_1") (pintype "passive"))
    )
    (net (code "166") (name "Net-(Q6B-E)") (class "Default")
      (node (ref "Q6B") (pin "1") (pinfunction "E_1") (pintype "passive"))
      (node (ref "R17") (pin "2") (pinfunction "2_2") (pintype "passive"))
    )
    (net (code "167") (name "Net-(Q7-B)") (class "Default")
      (node (ref "C42") (pin "2") (pinfunction "2_2") (pintype "passive"))
      (node (ref "Q7") (pin "2") (pinfunction "B_2") (pintype "passive"))
      (node (ref "R69") (pin "2") (pinfunction "2_2") (pintype "passive"))
      (node (ref "R70") (pin "1") (pinfunction "1_1") (pintype "passive"))
    )
    (net (code "168") (name "Net-(Q7A-B)") (class "Default")
      (node (ref "C33") (pin "2") (pinfunction "2_2") (pintype "passive"))
      (node (ref "Q7A") (pin "2") (pinfunction "B_2") (pintype "passive"))
      (node (ref "R142") (pin "2") (pinfunction "2_2") (pintype "passive"))
      (node (ref "R143") (pin "1") (pinfunction "1_1") (pintype "passive"))
    )
    (net (code "169") (name "Net-(Q7B-E)") (class "Default")
      (node (ref "Q7B") (pin "1") (pinfunction "E_1") (pintype "passive"))
      (node (ref "R20") (pin "2") (pinfunction "2_2") (pintype "passive"))
    )
    (net (code "170") (name "Net-(Q8A-B)") (class "Default")
      (node (ref "C34") (pin "2") (pinfunction "2_2") (pintype "passive"))
      (node (ref "Q8A") (pin "2") (pinfunction "B_2") (pintype "passive"))
      (node (ref "R144") (pin "2") (pinfunction "2_2") (pintype "passive"))
      (node (ref "R145") (pin "1") (pinfunction "1_1") (pintype "passive"))
    )
    (net (code "171") (name "Net-(Q8B-E)") (class "Default")
      (node (ref "Q8B") (pin "1") (pinfunction "E_1") (pintype "passive"))
      (node (ref "R23") (pin "2") (pinfunction "2_2") (pintype "passive"))
    )
    (net (code "172") (name "Net-(Q9A-B)") (class "Default")
      (node (ref "C35") (pin "2") (pinfunction "2_2") (pintype "passive"))
      (node (ref "Q9A") (pin "2") (pinfunction "B_2") (pintype "passive"))
      (node (ref "R146") (pin "2") (pinfunction "2_2") (pintype "passive"))
      (node (ref "R147") (pin "1") (pinfunction "1_1") (pintype "passive"))
    )
    (net (code "173") (name "Net-(Q9B-E)") (class "Default")
      (node (ref "Q9B") (pin "1") (pinfunction "E_1") (pintype "passive"))
      (node (ref "R65") (pin "2") (pinfunction "2_2") (pintype "passive"))
    )
    (net (code "174") (name "Net-(Q10A-B)") (class "Default")
      (node (ref "C36") (pin "2") (pinfunction "2_2") (pintype "passive"))
      (node (ref "Q10A") (pin "2") (pinfunction "B_2") (pintype "passive"))
      (node (ref "R148") (pin "2") (pinfunction "2_2") (pintype "passive"))
      (node (ref "R149") (pin "1") (pinfunction "1_1") (pintype "passive"))
    )
    (net (code "175") (name "Net-(Q10B-E)") (class "Default")
      (node (ref "Q10B") (pin "1") (pinfunction "E_1") (pintype "passive"))
      (node (ref "R68") (pin "2") (pinfunction "2_2") (pintype "passive"))
    )
    (net (code "176") (name "Net-(Q11A-B)") (class "Default")
      (node (ref "C37") (pin "2") (pinfunction "2_2") (pintype "passive"))
      (node (ref "Q11A") (pin "2") (pinfunction "B_2") (pintype "passive"))
      (node (ref "R150") (pin "2") (pinfunction "2_2") (pintype "passive"))
      (node (ref "R151") (pin "1") (pinfunction "1_1") (pintype "passive"))
    )
    (net (code "177") (name "Net-(Q11B-E)") (class "Default")
      (node (ref "Q11B") (pin "1") (pinfunction "E_1") (pintype "passive"))
      (node (ref "R74") (pin "2") (pinfunction "2_2") (pintype "passive"))
    )
    (net (code "178") (name "Net-(Q12A-B)") (class "Default")
      (node (ref "C38") (pin "2") (pinfunction "2_2") (pintype "passive"))
      (node (ref "Q12A") (pin "2") (pinfunction "B_2") (pintype "passive"))
      (node (ref "R152") (pin "2") (pinfunction "2_2") (pintype "passive"))
      (node (ref "R153") (pin "1") (pinfunction "1_1") (pintype "passive"))
    )
    (net (code "179") (name "Net-(Q12B-E)") (class "Default")
      (node (ref "Q12B") (pin "1") (pinfunction "E_1") (pintype "passive"))
      (node (ref "R79") (pin "2") (pinfunction "2_2") (pintype "passive"))
    )
    (net (code "180") (name "Net-(Q13B-B)") (class "Default")
      (node (ref "D82") (pin "A") (pinfunction "A_A") (pintype "passive"))
      (node (ref "Q13B") (pin "2") (pinfunction "B_2") (pintype "passive"))
      (node (ref "R81") (pin "1") (pinfunction "1_1") (pintype "passive"))
    )
    (net (code "181") (name "Net-(Q14B-B)") (class "Default")
      (node (ref "D88") (pin "A") (pinfunction "A_A") (pintype "passive"))
      (node (ref "Q14B") (pin "2") (pinfunction "B_2") (pintype "passive"))
      (node (ref "R83") (pin "1") (pinfunction "1_1") (pintype "passive"))
    )
    (net (code "182") (name "Net-(Q15B-B)") (class "Default")
      (node (ref "D94") (pin "A") (pinfunction "A_A") (pintype "passive"))
      (node (ref "Q15B") (pin "2") (pinfunction "B_2") (pintype "passive"))
      (node (ref "R97") (pin "1") (pinfunction "1_1") (pintype "passive"))
    )
    (net (code "183") (name "Net-(Q16B-B)") (class "Default")
      (node (ref "D100") (pin "A") (pinfunction "A_A") (pintype "passive"))
      (node (ref "Q16B") (pin "2") (pinfunction "B_2") (pintype "passive"))
      (node (ref "R99") (pin "1") (pinfunction "1_1") (pintype "passive"))
    )
    (net (code "184") (name "Net-(Q17B-B)") (class "Default")
      (node (ref "D106") (pin "A") (pinfunction "A_A") (pintype "passive"))
      (node (ref "Q17B") (pin "2") (pinfunction "B_2") (pintype "passive"))
      (node (ref "R101") (pin "1") (pinfunction "1_1") (pintype "passive"))
    )
    (net (code "185") (name "Net-(Q18B-B)") (class "Default")
      (node (ref "D112") (pin "A") (pinfunction "A_A") (pintype "passive"))
      (node (ref "Q18B") (pin "2") (pinfunction "B_2") (pintype "passive"))
      (node (ref "R103") (pin "1") (pinfunction "1_1") (pintype "passive"))
    )
    (net (code "186") (name "Net-(Q26-E)") (class "Default")
      (node (ref "Q26") (pin "1") (pinfunction "E_1") (pintype "passive"))
      (node (ref "R105") (pin "2") (pinfunction "2_2") (pintype "passive"))
    )
    (net (code "187") (name "Net-(Q27-E)") (class "Default")
      (node (ref "Q27") (pin "1") (pinfunction "E_1") (pintype "passive"))
      (node (ref "R107") (pin "2") (pinfunction "2_2") (pintype "passive"))
    )
    (net (code "188") (name "Net-(Q28-E)") (class "Default")
      (node (ref "Q28") (pin "1") (pinfunction "E_1") (pintype "passive"))
      (node (ref "R109") (pin "2") (pinfunction "2_2") (pintype "passive"))
    )
    (net (code "189") (name "Net-(Q29-E)") (class "Default")
      (node (ref "Q29") (pin "1") (pinfunction "E_1") (pintype "passive"))
      (node (ref "R111") (pin "2") (pinfunction "2_2") (pintype "passive"))
    )
    (net (code "190") (name "Net-(Q30-E)") (class "Default")
      (node (ref "Q30") (pin "1") (pinfunction "E_1") (pintype "passive"))
      (node (ref "R113") (pin "2") (pinfunction "2_2") (pintype "passive"))
    )
    (net (code "191") (name "Net-(Q31-E)") (class "Default")
      (node (ref "Q31") (pin "1") (pinfunction "E_1") (pintype "passive"))
      (node (ref "R115") (pin "2") (pinfunction "2_2") (pintype "passive"))
    )
    (net (code "192") (name "Net-(Q32-E)") (class "Default")
      (node (ref "Q32") (pin "1") (pinfunction "E_1") (pintype "passive"))
      (node (ref "R117") (pin "2") (pinfunction "2_2") (pintype "passive"))
    )
    (net (code "193") (name "Net-(Q33-E)") (class "Default")
      (node (ref "Q33") (pin "1") (pinfunction "E_1") (pintype "passive"))
      (node (ref "R119") (pin "2") (pinfunction "2_2") (pintype "passive"))
    )
    (net (code "194") (name "Net-(Q34-E)") (class "Default")
      (node (ref "Q34") (pin "1") (pinfunction "E_1") (pintype "passive"))
      (node (ref "R121") (pin "2") (pinfunction "2_2") (pintype "passive"))
    )
    (net (code "195") (name "Net-(Q35-E)") (class "Default")
      (node (ref "Q35") (pin "1") (pinfunction "E_1") (pintype "passive"))
      (node (ref "R123") (pin "2") (pinfunction "2_2") (pintype "passive"))
    )
    (net (code "196") (name "Net-(Q36-E)") (class "Default")
      (node (ref "Q36") (pin "1") (pinfunction "E_1") (pintype "passive"))
      (node (ref "R125") (pin "2") (pinfunction "2_2") (pintype "passive"))
    )
    (net (code "197") (name "Net-(Q37-E)") (class "Default")
      (node (ref "Q37") (pin "1") (pinfunction "E_1") (pintype "passive"))
      (node (ref "R127") (pin "2") (pinfunction "2_2") (pintype "passive"))
    )
    (net (code "198") (name "Net-(Q50-B)") (class "Default")
      (node (ref "C39") (pin "2") (pinfunction "2_2") (pintype "passive"))
      (node (ref "Q50") (pin "2") (pinfunction "B_2") (pintype "passive"))
      (node (ref "R155") (pin "2") (pinfunction "2_2") (pintype "passive"))
      (node (ref "R156") (pin "1") (pinfunction "1_1") (pintype "passive"))
    )
    (net (code "199") (name "Net-(Q51-B)") (class "Default")
      (node (ref "C40") (pin "2") (pinfunction "2_2") (pintype "passive"))
      (node (ref "Q51") (pin "2") (pinfunction "B_2") (pintype "passive"))
      (node (ref "R157") (pin "2") (pinfunction "2_2") (pintype "passive"))
      (node (ref "R158") (pin "1") (pinfunction "1_1") (pintype "passive"))
    )
    (net (code "200") (name "Net-(Q52-B)") (class "Default")
      (node (ref "C41") (pin "2") (pinfunction "2_2") (pintype "passive"))
      (node (ref "Q52") (pin "2") (pinfunction "B_2") (pintype "passive"))
      (node (ref "R159") (pin "2") (pinfunction "2_2") (pintype "passive"))
      (node (ref "R160") (pin "1") (pinfunction "1_1") (pintype "passive"))
    )
    (net (code "201") (name "Net-(R45-Pad2)") (class "Default")
      (node (ref "R45") (pin "2") (pinfunction "2_2") (pintype "passive"))
      (node (ref "R46") (pin "1") (pinfunction "1_1") (pintype "passive"))
    )
    (net (code "202") (name "Net-(R48-Pad2)") (class "Default")
      (node (ref "R48") (pin "2") (pinfunction "2_2") (pintype "passive"))
      (node (ref "R49") (pin "1") (pinfunction "1_1") (pintype "passive"))
    )
    (net (code "203") (name "Net-(R51-Pad2)") (class "Default")
      (node (ref "R51") (pin "2") (pinfunction "2_2") (pintype "passive"))
      (node (ref "R52") (pin "1") (pinfunction "1_1") (pintype "passive"))
    )
    (net (code "204") (name "Net-(R54-Pad2)") (class "Default")
      (node (ref "R54") (pin "2") (pinfunction "2_2") (pintype "passive"))
      (node (ref "R55") (pin "1") (pinfunction "1_1") (pintype "passive"))
    )
    (net (code "205") (name "Net-(R57-Pad2)") (class "Default")
      (node (ref "R57") (pin "2") (pinfunction "2_2") (pintype "passive"))
      (node (ref "R58") (pin "1") (pinfunction "1_1") (pintype "passive"))
    )
    (net (code "206") (name "Net-(R60-Pad2)") (class "Default")
      (node (ref "R60") (pin "2") (pinfunction "2_2") (pintype "passive"))
      (node (ref "R61") (pin "1") (pinfunction "1_1") (pintype "passive"))
    )
    (net (code "207") (name "TS3") (class "Default")
      (node (ref "D38") (pin "A") (pinfunction "A_A") (pintype "passive"))
      (node (ref "E27") (pin "12") (pinfunction "O_12") (pintype "open_collector"))
      (node (ref "Q4") (pin "1") (pinfunction "E_1") (pintype "passive"))
      (node (ref "U$3") (pin "AS2") (pinfunction "1_AS2") (pintype "bidirectional"))
    )
    (net (code "208") (name "TS4") (class "Default")
      (node (ref "D40") (pin "A") (pinfunction "A_A") (pintype "passive"))
      (node (ref "E27") (pin "4") (pinfunction "O_4") (pintype "open_collector"))
      (node (ref "Q5") (pin "1") (pinfunction "E_1") (pintype "passive"))
      (node (ref "U$3") (pin "AT2") (pinfunction "1_AT2") (pintype "bidirectional"))
    )
    (net (code "209") (name "VCC") (class "Default")
      (node (ref "C1") (pin "1") (pinfunction "1_1") (pintype "passive"))
      (node (ref "C10") (pin "1") (pinfunction "1_1") (pintype "passive"))
      (node (ref "C11") (pin "1") (pinfunction "1_1") (pintype "passive"))
      (node (ref "C12") (pin "1") (pinfunction "1_1") (pintype "passive"))
      (node (ref "C2") (pin "1") (pinfunction "1_1") (pintype "passive"))
      (node (ref "C20") (pin "+") (pinfunction "+_+") (pintype "passive"))
      (node (ref "C21") (pin "+") (pinfunction "+_+") (pintype "passive"))
      (node (ref "C22") (pin "+") (pinfunction "+_+") (pintype "passive"))
      (node (ref "C3") (pin "1") (pinfunction "1_1") (pintype "passive"))
      (node (ref "C4") (pin "1") (pinfunction "1_1") (pintype "passive"))
      (node (ref "C5") (pin "1") (pinfunction "1_1") (pintype "passive"))
      (node (ref "C6") (pin "1") (pinfunction "1_1") (pintype "passive"))
      (node (ref "C7") (pin "1") (pinfunction "1_1") (pintype "passive"))
      (node (ref "C8") (pin "1") (pinfunction "1_1") (pintype "passive"))
      (node (ref "C9") (pin "1") (pinfunction "1_1") (pintype "passive"))
      (node (ref "D153") (pin "C") (pinfunction "C_C") (pintype "passive"))
      (node (ref "D155") (pin "C") (pinfunction "C_C") (pintype "passive"))
      (node (ref "D157") (pin "C") (pinfunction "C_C") (pintype "passive"))
      (node (ref "D159") (pin "C") (pinfunction "C_C") (pintype "passive"))
      (node (ref "D161") (pin "C") (pinfunction "C_C") (pintype "passive"))
      (node (ref "D163") (pin "C") (pinfunction "C_C") (pintype "passive"))
      (node (ref "D165") (pin "C") (pinfunction "C_C") (pintype "passive"))
      (node (ref "D167") (pin "C") (pinfunction "C_C") (pintype "passive"))
      (node (ref "D169") (pin "C") (pinfunction "C_C") (pintype "passive"))
      (node (ref "D171") (pin "C") (pinfunction "C_C") (pintype "passive"))
      (node (ref "D173") (pin "C") (pinfunction "C_C") (pintype "passive"))
      (node (ref "D175") (pin "C") (pinfunction "C_C") (pintype "passive"))
      (node (ref "D177") (pin "C") (pinfunction "C_C") (pintype "passive"))
      (node (ref "D179") (pin "C") (pinfunction "C_C") (pintype "passive"))
      (node (ref "D181") (pin "C") (pinfunction "C_C") (pintype "passive"))
      (node (ref "D183") (pin "C") (pinfunction "C_C") (pintype "passive"))
      (node (ref "R1") (pin "2") (pinfunction "2_2") (pintype "passive"))
      (node (ref "R100") (pin "2") (pinfunction "2_2") (pintype "passive"))
      (node (ref "R101") (pin "2") (pinfunction "2_2") (pintype "passive"))
      (node (ref "R102") (pin "2") (pinfunction "2_2") (pintype "passive"))
      (node (ref "R103") (pin "2") (pinfunction "2_2") (pintype "passive"))
      (node (ref "R104") (pin "2") (pinfunction "2_2") (pintype "passive"))
      (node (ref "R106") (pin "2") (pinfunction "2_2") (pintype "passive"))
      (node (ref "R108") (pin "2") (pinfunction "2_2") (pintype "passive"))
      (node (ref "R11") (pin "2") (pinfunction "2_2") (pintype "passive"))
      (node (ref "R110") (pin "2") (pinfunction "2_2") (pintype "passive"))
      (node (ref "R112") (pin "2") (pinfunction "2_2") (pintype "passive"))
      (node (ref "R114") (pin "2") (pinfunction "2_2") (pintype "passive"))
      (node (ref "R116") (pin "2") (pinfunction "2_2") (pintype "passive"))
      (node (ref "R118") (pin "2") (pinfunction "2_2") (pintype "passive"))
      (node (ref "R12") (pin "2") (pinfunction "2_2") (pintype "passive"))
      (node (ref "R120") (pin "2") (pinfunction "2_2") (pintype "passive"))
      (node (ref "R122") (pin "2") (pinfunction "2_2") (pintype "passive"))
      (node (ref "R124") (pin "2") (pinfunction "2_2") (pintype "passive"))
      (node (ref "R126") (pin "2") (pinfunction "2_2") (pintype "passive"))
      (node (ref "R128") (pin "2") (pinfunction "2_2") (pintype "passive"))
      (node (ref "R13") (pin "2") (pinfunction "2_2") (pintype "passive"))
      (node (ref "R15") (pin "2") (pinfunction "2_2") (pintype "passive"))
      (node (ref "R154") (pin "2") (pinfunction "2_2") (pintype "passive"))
      (node (ref "R16") (pin "2") (pinfunction "2_2") (pintype "passive"))
      (node (ref "R18") (pin "2") (pinfunction "2_2") (pintype "passive"))
      (node (ref "R19") (pin "2") (pinfunction "2_2") (pintype "passive"))
      (node (ref "R2") (pin "2") (pinfunction "2_2") (pintype "passive"))
      (node (ref "R21") (pin "2") (pinfunction "2_2") (pintype "passive"))
      (node (ref "R22") (pin "2") (pinfunction "2_2") (pintype "passive"))
      (node (ref "R24") (pin "2") (pinfunction "2_2") (pintype "passive"))
      (node (ref "R25") (pin "2") (pinfunction "2_2") (pintype "passive"))
      (node (ref "R26") (pin "2") (pinfunction "2_2") (pintype "passive"))
      (node (ref "R27") (pin "2") (pinfunction "2_2") (pintype "passive"))
      (node (ref "R28") (pin "2") (pinfunction "2_2") (pintype "passive"))
      (node (ref "R29") (pin "2") (pinfunction "2_2") (pintype "passive"))
      (node (ref "R30") (pin "2") (pinfunction "2_2") (pintype "passive"))
      (node (ref "R31") (pin "2") (pinfunction "2_2") (pintype "passive"))
      (node (ref "R32") (pin "2") (pinfunction "2_2") (pintype "passive"))
      (node (ref "R33") (pin "2") (pinfunction "2_2") (pintype "passive"))
      (node (ref "R34") (pin "2") (pinfunction "2_2") (pintype "passive"))
      (node (ref "R35") (pin "2") (pinfunction "2_2") (pintype "passive"))
      (node (ref "R36") (pin "2") (pinfunction "2_2") (pintype "passive"))
      (node (ref "R37") (pin "2") (pinfunction "2_2") (pintype "passive"))
      (node (ref "R38") (pin "2") (pinfunction "2_2") (pintype "passive"))
      (node (ref "R39") (pin "2") (pinfunction "2_2") (pintype "passive"))
      (node (ref "R4") (pin "2") (pinfunction "2_2") (pintype "passive"))
      (node (ref "R40") (pin "2") (pinfunction "2_2") (pintype "passive"))
      (node (ref "R41") (pin "2") (pinfunction "2_2") (pintype "passive"))
      (node (ref "R42") (pin "2") (pinfunction "2_2") (pintype "passive"))
      (node (ref "R43") (pin "2") (pinfunction "2_2") (pintype "passive"))
      (node (ref "R44") (pin "2") (pinfunction "2_2") (pintype "passive"))
      (node (ref "R46") (pin "2") (pinfunction "2_2") (pintype "passive"))
      (node (ref "R47") (pin "2") (pinfunction "2_2") (pintype "passive"))
      (node (ref "R49") (pin "2") (pinfunction "2_2") (pintype "passive"))
      (node (ref "R50") (pin "2") (pinfunction "2_2") (pintype "passive"))
      (node (ref "R52") (pin "2") (pinfunction "2_2") (pintype "passive"))
      (node (ref "R53") (pin "2") (pinfunction "2_2") (pintype "passive"))
      (node (ref "R55") (pin "2") (pinfunction "2_2") (pintype "passive"))
      (node (ref "R56") (pin "2") (pinfunction "2_2") (pintype "passive"))
      (node (ref "R58") (pin "2") (pinfunction "2_2") (pintype "passive"))
      (node (ref "R59") (pin "2") (pinfunction "2_2") (pintype "passive"))
      (node (ref "R6") (pin "2") (pinfunction "2_2") (pintype "passive"))
      (node (ref "R61") (pin "2") (pinfunction "2_2") (pintype "passive"))
      (node (ref "R62") (pin "2") (pinfunction "2_2") (pintype "passive"))
      (node (ref "R63") (pin "2") (pinfunction "2_2") (pintype "passive"))
      (node (ref "R64") (pin "2") (pinfunction "2_2") (pintype "passive"))
      (node (ref "R66") (pin "2") (pinfunction "2_2") (pintype "passive"))
      (node (ref "R67") (pin "2") (pinfunction "2_2") (pintype "passive"))
      (node (ref "R72") (pin "2") (pinfunction "2_2") (pintype "passive"))
      (node (ref "R73") (pin "2") (pinfunction "2_2") (pintype "passive"))
      (node (ref "R75") (pin "2") (pinfunction "2_2") (pintype "passive"))
      (node (ref "R76") (pin "2") (pinfunction "2_2") (pintype "passive"))
      (node (ref "R78") (pin "2") (pinfunction "2_2") (pintype "passive"))
      (node (ref "R8") (pin "2") (pinfunction "2_2") (pintype "passive"))
      (node (ref "R80") (pin "2") (pinfunction "2_2") (pintype "passive"))
      (node (ref "R81") (pin "2") (pinfunction "2_2") (pintype "passive"))
      (node (ref "R82") (pin "2") (pinfunction "2_2") (pintype "passive"))
      (node (ref "R83") (pin "2") (pinfunction "2_2") (pintype "passive"))
      (node (ref "R84") (pin "2") (pinfunction "2_2") (pintype "passive"))
      (node (ref "R85") (pin "2") (pinfunction "2_2") (pintype "passive"))
      (node (ref "R86") (pin "2") (pinfunction "2_2") (pintype "passive"))
      (node (ref "R87") (pin "2") (pinfunction "2_2") (pintype "passive"))
      (node (ref "R88") (pin "2") (pinfunction "2_2") (pintype "passive"))
      (node (ref "R89") (pin "2") (pinfunction "2_2") (pintype "passive"))
      (node (ref "R9") (pin "2") (pinfunction "2_2") (pintype "passive"))
      (node (ref "R90") (pin "2") (pinfunction "2_2") (pintype "passive"))
      (node (ref "R91") (pin "2") (pinfunction "2_2") (pintype "passive"))
      (node (ref "R92") (pin "2") (pinfunction "2_2") (pintype "passive"))
      (node (ref "R93") (pin "2") (pinfunction "2_2") (pintype "passive"))
      (node (ref "R94") (pin "2") (pinfunction "2_2") (pintype "passive"))
      (node (ref "R95") (pin "2") (pinfunction "2_2") (pintype "passive"))
      (node (ref "R96") (pin "2") (pinfunction "2_2") (pintype "passive"))
      (node (ref "R97") (pin "2") (pinfunction "2_2") (pintype "passive"))
      (node (ref "R98") (pin "2") (pinfunction "2_2") (pintype "passive"))
      (node (ref "R99") (pin "2") (pinfunction "2_2") (pintype "passive"))
      (node (ref "U$3") (pin "AA2") (pinfunction "1_AA2") (pintype "bidirectional"))
      (node (ref "U$3") (pin "BA2") (pinfunction "1_BA2") (pintype "bidirectional"))
      (node (ref "U$3") (pin "CA2") (pinfunction "1_CA2") (pintype "bidirectional"))
    )
    (net (code "210") (name "unconnected-(NACI00-Pad2)") (class "Default")
      (node (ref "NACI00") (pin "2") (pinfunction "2_2") (pintype "passive"))
    )
    (net (code "211") (name "unconnected-(NACI00-Pad4)") (class "Default")
      (node (ref "NACI00") (pin "4") (pinfunction "4_4") (pintype "passive"))
    )
    (net (code "212") (name "unconnected-(NACI09-Pad2)") (class "Default")
      (node (ref "NACI09") (pin "2") (pinfunction "2_2") (pintype "passive"))
    )
    (net (code "213") (name "unconnected-(NACI09-Pad4)") (class "Default")
      (node (ref "NACI09") (pin "4") (pinfunction "4_4") (pintype "passive"))
    )
    (net (code "214") (name "unconnected-(NBAC00-Pad2)") (class "Default")
      (node (ref "NBAC00") (pin "2") (pinfunction "2_2") (pintype "passive"))
    )
    (net (code "215") (name "unconnected-(NBAC00-Pad4)") (class "Default")
      (node (ref "NBAC00") (pin "4") (pinfunction "4_4") (pintype "passive"))
    )
    (net (code "216") (name "unconnected-(NBAC09-Pad2)") (class "Default")
      (node (ref "NBAC09") (pin "2") (pinfunction "2_2") (pintype "passive"))
    )
    (net (code "217") (name "unconnected-(NBAC09-Pad4)") (class "Default")
      (node (ref "NBAC09") (pin "4") (pinfunction "4_4") (pintype "passive"))
    )
    (net (code "218") (name "unconnected-(NBMB00-Pad2)") (class "Default")
      (node (ref "NBMB00") (pin "2") (pinfunction "2_2") (pintype "passive"))
    )
    (net (code "219") (name "unconnected-(NBMB00-Pad4)") (class "Default")
      (node (ref "NBMB00") (pin "4") (pinfunction "4_4") (pintype "passive"))
    )
    (net (code "220") (name "unconnected-(NBMB06-Pad2)") (class "Default")
      (node (ref "NBMB06") (pin "2") (pinfunction "2_2") (pintype "passive"))
    )
    (net (code "221") (name "unconnected-(NBMB06-Pad4)") (class "Default")
      (node (ref "NBMB06") (pin "4") (pinfunction "4_4") (pintype "passive"))
    )
    (net (code "222") (name "~{0_TO_AC}") (class "Default")
      (node (ref "D181") (pin "A") (pinfunction "A_A") (pintype "passive"))
      (node (ref "D182") (pin "C") (pinfunction "C_C") (pintype "passive"))
      (node (ref "E4") (pin "1") (pinfunction "I_1") (pintype "input"))
      (node (ref "R64") (pin "1") (pinfunction "1_1") (pintype "passive"))
      (node (ref "U$3") (pin "CP2") (pinfunction "1_CP2") (pintype "bidirectional"))
    )
    (net (code "223") (name "~{BMB03}") (class "Default")
      (node (ref "D16") (pin "A") (pinfunction "A_A") (pintype "passive"))
      (node (ref "E17") (pin "6") (pinfunction "O_6") (pintype "open_collector"))
      (node (ref "E17") (pin "8") (pinfunction "O_8") (pintype "open_collector"))
      (node (ref "R28") (pin "1") (pinfunction "1_1") (pintype "passive"))
      (node (ref "U$3") (pin "BH1") (pinfunction "1_BH1") (pintype "bidirectional"))
    )
    (net (code "224") (name "~{BMB04}") (class "Default")
      (node (ref "D18") (pin "A") (pinfunction "A_A") (pintype "passive"))
      (node (ref "E21") (pin "6") (pinfunction "O_6") (pintype "open_collector"))
      (node (ref "E21") (pin "8") (pinfunction "O_8") (pintype "open_collector"))
      (node (ref "R30") (pin "1") (pinfunction "1_1") (pintype "passive"))
      (node (ref "U$3") (pin "BL1") (pinfunction "1_BL1") (pintype "bidirectional"))
    )
    (net (code "225") (name "~{BMB05}") (class "Default")
      (node (ref "D20") (pin "A") (pinfunction "A_A") (pintype "passive"))
      (node (ref "E21") (pin "10") (pinfunction "O_10") (pintype "open_collector"))
      (node (ref "E21") (pin "12") (pinfunction "O_12") (pintype "open_collector"))
      (node (ref "R32") (pin "1") (pinfunction "1_1") (pintype "passive"))
      (node (ref "U$3") (pin "BP1") (pinfunction "1_BP1") (pintype "bidirectional"))
    )
    (net (code "226") (name "~{BMB06}") (class "Default")
      (node (ref "D22") (pin "A") (pinfunction "A_A") (pintype "passive"))
      (node (ref "E17") (pin "2") (pinfunction "O_2") (pintype "open_collector"))
      (node (ref "E17") (pin "4") (pinfunction "O_4") (pintype "open_collector"))
      (node (ref "R34") (pin "1") (pinfunction "1_1") (pintype "passive"))
      (node (ref "U$3") (pin "BD2") (pinfunction "1_BD2") (pintype "bidirectional"))
    )
    (net (code "227") (name "~{BMB07}") (class "Default")
      (node (ref "D24") (pin "A") (pinfunction "A_A") (pintype "passive"))
      (node (ref "E17") (pin "10") (pinfunction "O_10") (pintype "open_collector"))
      (node (ref "E17") (pin "12") (pinfunction "O_12") (pintype "open_collector"))
      (node (ref "R36") (pin "1") (pinfunction "1_1") (pintype "passive"))
      (node (ref "U$3") (pin "BH2") (pinfunction "1_BH2") (pintype "bidirectional"))
    )
    (net (code "228") (name "~{BMB08}") (class "Default")
      (node (ref "D26") (pin "A") (pinfunction "A_A") (pintype "passive"))
      (node (ref "E21") (pin "2") (pinfunction "O_2") (pintype "open_collector"))
      (node (ref "E21") (pin "4") (pinfunction "O_4") (pintype "open_collector"))
      (node (ref "R38") (pin "1") (pinfunction "1_1") (pintype "passive"))
      (node (ref "U$3") (pin "BM2") (pinfunction "1_BM2") (pintype "bidirectional"))
    )
    (net (code "229") (name "~{BRUN}") (class "Default")
      (node (ref "D183") (pin "A") (pinfunction "A_A") (pintype "passive"))
      (node (ref "D184") (pin "C") (pinfunction "C_C") (pintype "passive"))
      (node (ref "E4") (pin "13") (pinfunction "I_13") (pintype "input"))
      (node (ref "R41") (pin "1") (pinfunction "1_1") (pintype "passive"))
      (node (ref "U$3") (pin "CS2") (pinfunction "1_CS2") (pintype "bidirectional"))
    )
    (net (code "230") (name "~{IN00}") (class "Default")
      (node (ref "D153") (pin "A") (pinfunction "A_A") (pintype "passive"))
      (node (ref "D154") (pin "C") (pinfunction "C_C") (pintype "passive"))
      (node (ref "E48") (pin "5") (pinfunction "I_5") (pintype "input"))
      (node (ref "R85") (pin "1") (pinfunction "1_1") (pintype "passive"))
      (node (ref "U$3") (pin "CB1") (pinfunction "1_CB1") (pintype "bidirectional"))
    )
    (net (code "231") (name "~{IN01}") (class "Default")
      (node (ref "D155") (pin "A") (pinfunction "A_A") (pintype "passive"))
      (node (ref "D156") (pin "C") (pinfunction "C_C") (pintype "passive"))
      (node (ref "E48") (pin "1") (pinfunction "I_1") (pintype "input"))
      (node (ref "R86") (pin "1") (pinfunction "1_1") (pintype "passive"))
      (node (ref "U$3") (pin "CD1") (pinfunction "1_CD1") (pintype "bidirectional"))
    )
    (net (code "232") (name "~{IN02}") (class "Default")
      (node (ref "D157") (pin "A") (pinfunction "A_A") (pintype "passive"))
      (node (ref "D158") (pin "C") (pinfunction "C_C") (pintype "passive"))
      (node (ref "E48") (pin "13") (pinfunction "I_13") (pintype "input"))
      (node (ref "R87") (pin "1") (pinfunction "1_1") (pintype "passive"))
      (node (ref "U$3") (pin "CE1") (pinfunction "1_CE1") (pintype "bidirectional"))
    )
    (net (code "233") (name "~{IN03}") (class "Default")
      (node (ref "D159") (pin "A") (pinfunction "A_A") (pintype "passive"))
      (node (ref "D160") (pin "C") (pinfunction "C_C") (pintype "passive"))
      (node (ref "E49") (pin "5") (pinfunction "I_5") (pintype "input"))
      (node (ref "R88") (pin "1") (pinfunction "1_1") (pintype "passive"))
      (node (ref "U$3") (pin "CH1") (pinfunction "1_CH1") (pintype "bidirectional"))
    )
    (net (code "234") (name "~{IN04}") (class "Default")
      (node (ref "D161") (pin "A") (pinfunction "A_A") (pintype "passive"))
      (node (ref "D162") (pin "C") (pinfunction "C_C") (pintype "passive"))
      (node (ref "E49") (pin "3") (pinfunction "I_3") (pintype "input"))
      (node (ref "R89") (pin "1") (pinfunction "1_1") (pintype "passive"))
      (node (ref "U$3") (pin "CJ1") (pinfunction "1_CJ1") (pintype "bidirectional"))
    )
    (net (code "235") (name "~{IN05}") (class "Default")
      (node (ref "D163") (pin "A") (pinfunction "A_A") (pintype "passive"))
      (node (ref "D164") (pin "C") (pinfunction "C_C") (pintype "passive"))
      (node (ref "E49") (pin "13") (pinfunction "I_13") (pintype "input"))
      (node (ref "R90") (pin "1") (pinfunction "1_1") (pintype "passive"))
      (node (ref "U$3") (pin "CL1") (pinfunction "1_CL1") (pintype "bidirectional"))
    )
    (net (code "236") (name "~{IN06}") (class "Default")
      (node (ref "D165") (pin "A") (pinfunction "A_A") (pintype "passive"))
      (node (ref "D166") (pin "C") (pinfunction "C_C") (pintype "passive"))
      (node (ref "E49") (pin "9") (pinfunction "I_9") (pintype "input"))
      (node (ref "R91") (pin "1") (pinfunction "1_1") (pintype "passive"))
      (node (ref "U$3") (pin "CM1") (pinfunction "1_CM1") (pintype "bidirectional"))
    )
    (net (code "237") (name "~{IN07}") (class "Default")
      (node (ref "D167") (pin "A") (pinfunction "A_A") (pintype "passive"))
      (node (ref "D168") (pin "C") (pinfunction "C_C") (pintype "passive"))
      (node (ref "E4") (pin "3") (pinfunction "I_3") (pintype "input"))
      (node (ref "R92") (pin "1") (pinfunction "1_1") (pintype "passive"))
      (node (ref "U$3") (pin "CP1") (pinfunction "1_CP1") (pintype "bidirectional"))
    )
    (net (code "238") (name "~{IN08}") (class "Default")
      (node (ref "D169") (pin "A") (pinfunction "A_A") (pintype "passive"))
      (node (ref "D170") (pin "C") (pinfunction "C_C") (pintype "passive"))
      (node (ref "E4") (pin "11") (pinfunction "I_11") (pintype "input"))
      (node (ref "R93") (pin "1") (pinfunction "1_1") (pintype "passive"))
      (node (ref "U$3") (pin "CS1") (pinfunction "1_CS1") (pintype "bidirectional"))
    )
    (net (code "239") (name "~{IN09}") (class "Default")
      (node (ref "D171") (pin "A") (pinfunction "A_A") (pintype "passive"))
      (node (ref "D172") (pin "C") (pinfunction "C_C") (pintype "passive"))
      (node (ref "E48") (pin "3") (pinfunction "I_3") (pintype "input"))
      (node (ref "R94") (pin "1") (pinfunction "1_1") (pintype "passive"))
      (node (ref "U$3") (pin "CD2") (pinfunction "1_CD2") (pintype "bidirectional"))
    )
    (net (code "240") (name "~{IN10}") (class "Default")
      (node (ref "D173") (pin "A") (pinfunction "A_A") (pintype "passive"))
      (node (ref "D174") (pin "C") (pinfunction "C_C") (pintype "passive"))
      (node (ref "E48") (pin "9") (pinfunction "I_9") (pintype "input"))
      (node (ref "R95") (pin "1") (pinfunction "1_1") (pintype "passive"))
      (node (ref "U$3") (pin "CE2") (pinfunction "1_CE2") (pintype "bidirectional"))
    )
    (net (code "241") (name "~{IN11}") (class "Default")
      (node (ref "D175") (pin "A") (pinfunction "A_A") (pintype "passive"))
      (node (ref "D176") (pin "C") (pinfunction "C_C") (pintype "passive"))
      (node (ref "E48") (pin "11") (pinfunction "I_11") (pintype "input"))
      (node (ref "R96") (pin "1") (pinfunction "1_1") (pintype "passive"))
      (node (ref "U$3") (pin "CH2") (pinfunction "1_CH2") (pintype "bidirectional"))
    )
    (net (code "242") (name "~{INT_RQ}") (class "Default")
      (node (ref "D179") (pin "A") (pinfunction "A_A") (pintype "passive"))
      (node (ref "D180") (pin "C") (pinfunction "C_C") (pintype "passive"))
      (node (ref "E49") (pin "11") (pinfunction "I_11") (pintype "input"))
      (node (ref "R63") (pin "1") (pinfunction "1_1") (pintype "passive"))
      (node (ref "U$3") (pin "CM2") (pinfunction "1_CM2") (pintype "bidirectional"))
    )
    (net (code "243") (name "~{NBMB03}") (class "Default")
      (node (ref "NBMB00") (pin "16") (pinfunction "16_16") (pintype "passive"))
    )
    (net (code "244") (name "~{NBMB04}") (class "Default")
      (node (ref "NBMB00") (pin "24") (pinfunction "24_24") (pintype "passive"))
    )
    (net (code "245") (name "~{NBMB05}") (class "Default")
      (node (ref "NBMB00") (pin "30") (pinfunction "30_30") (pintype "passive"))
    )
    (net (code "246") (name "~{NBMB06}") (class "Default")
      (node (ref "NBMB06") (pin "6") (pinfunction "6_6") (pintype "passive"))
    )
    (net (code "247") (name "~{NBMB07}") (class "Default")
      (node (ref "NBMB06") (pin "12") (pinfunction "12_12") (pintype "passive"))
    )
    (net (code "248") (name "~{NBMB08}") (class "Default")
      (node (ref "NBMB06") (pin "20") (pinfunction "20_20") (pintype "passive"))
    )
    (net (code "249") (name "~{NINIT}") (class "Default")
      (node (ref "D108") (pin "C") (pinfunction "C_C") (pintype "passive"))
      (node (ref "D109") (pin "A") (pinfunction "A_A") (pintype "passive"))
      (node (ref "D110") (pin "C") (pinfunction "C_C") (pintype "passive"))
      (node (ref "NBAC09") (pin "34") (pinfunction "34_34") (pintype "passive"))
    )
    (net (code "250") (name "~{NIOP1}") (class "Default")
      (node (ref "D90") (pin "C") (pinfunction "C_C") (pintype "passive"))
      (node (ref "D91") (pin "A") (pinfunction "A_A") (pintype "passive"))
      (node (ref "D92") (pin "C") (pinfunction "C_C") (pintype "passive"))
      (node (ref "NBAC09") (pin "16") (pinfunction "16_16") (pintype "passive"))
    )
    (net (code "251") (name "~{NIOP2}") (class "Default")
      (node (ref "D84") (pin "C") (pinfunction "C_C") (pintype "passive"))
      (node (ref "D85") (pin "A") (pinfunction "A_A") (pintype "passive"))
      (node (ref "D86") (pin "C") (pinfunction "C_C") (pintype "passive"))
      (node (ref "NBAC09") (pin "20") (pinfunction "20_20") (pintype "passive"))
    )
    (net (code "252") (name "~{NIOP4}") (class "Default")
      (node (ref "D78") (pin "C") (pinfunction "C_C") (pintype "passive"))
      (node (ref "D79") (pin "A") (pinfunction "A_A") (pintype "passive"))
      (node (ref "D80") (pin "C") (pinfunction "C_C") (pintype "passive"))
      (node (ref "NBAC09") (pin "24") (pinfunction "24_24") (pintype "passive"))
    )
    (net (code "253") (name "~{NRUN}") (class "Default")
      (node (ref "D39") (pin "C") (pinfunction "C_C") (pintype "passive"))
      (node (ref "NACI09") (pin "28") (pinfunction "28_28") (pintype "passive"))
      (node (ref "Q7") (pin "3") (pinfunction "C_3") (pintype "passive"))
    )
    (net (code "254") (name "~{SKP_RQ}") (class "Default")
      (node (ref "D177") (pin "A") (pinfunction "A_A") (pintype "passive"))
      (node (ref "D178") (pin "C") (pinfunction "C_C") (pintype "passive"))
      (node (ref "E49") (pin "1") (pinfunction "I_1") (pintype "input"))
      (node (ref "R154") (pin "1") (pinfunction "1_1") (pintype "passive"))
      (node (ref "U$3") (pin "CK2") (pinfunction "1_CK2") (pintype "bidirectional"))
    )
  )
)
